# I2CRJ45X32.net
KiCad netlist of a schematic drawn in EAGLE
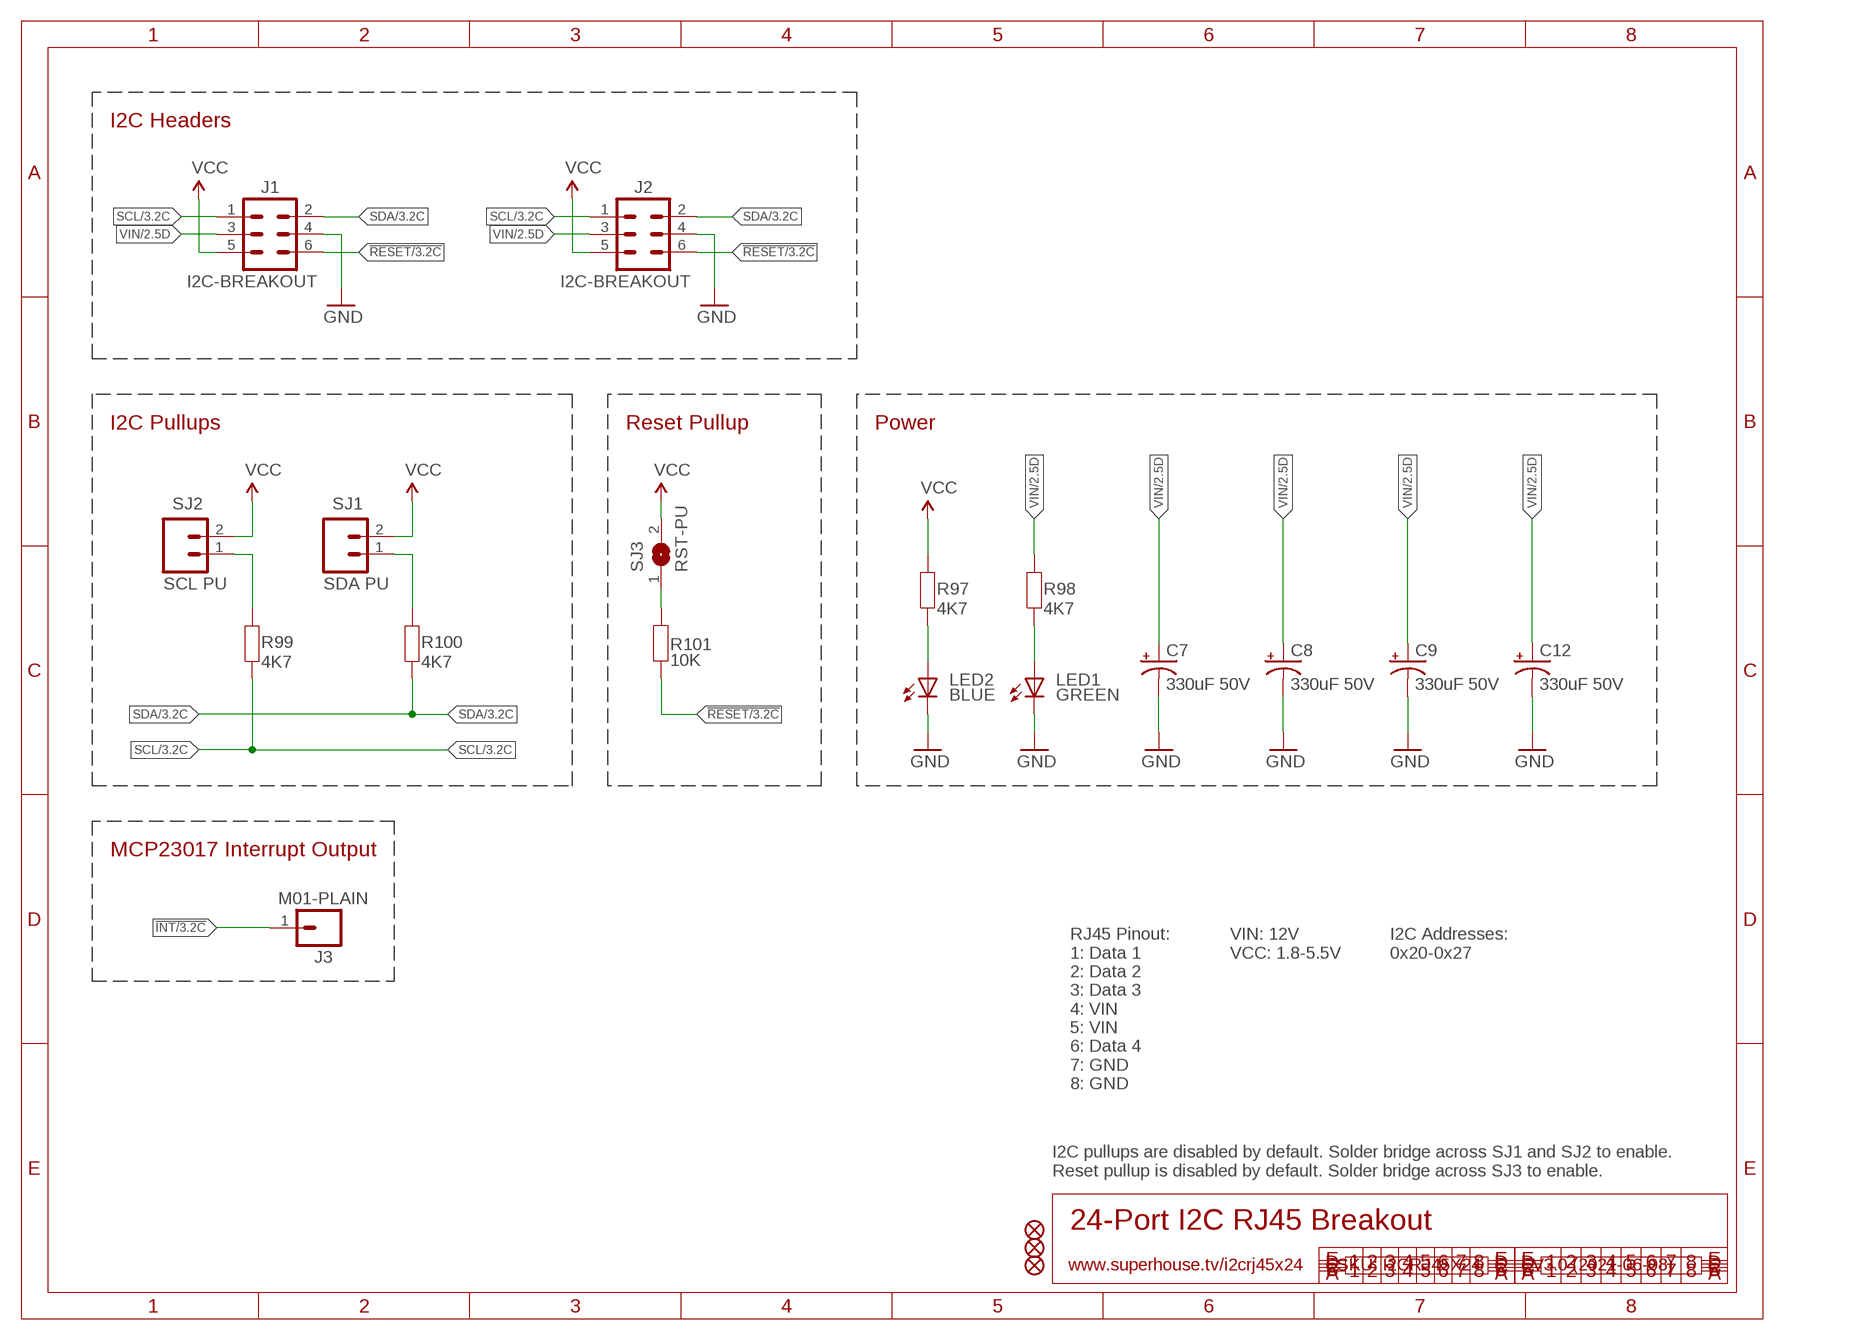
[diagram p0: schematic, sheet 1]
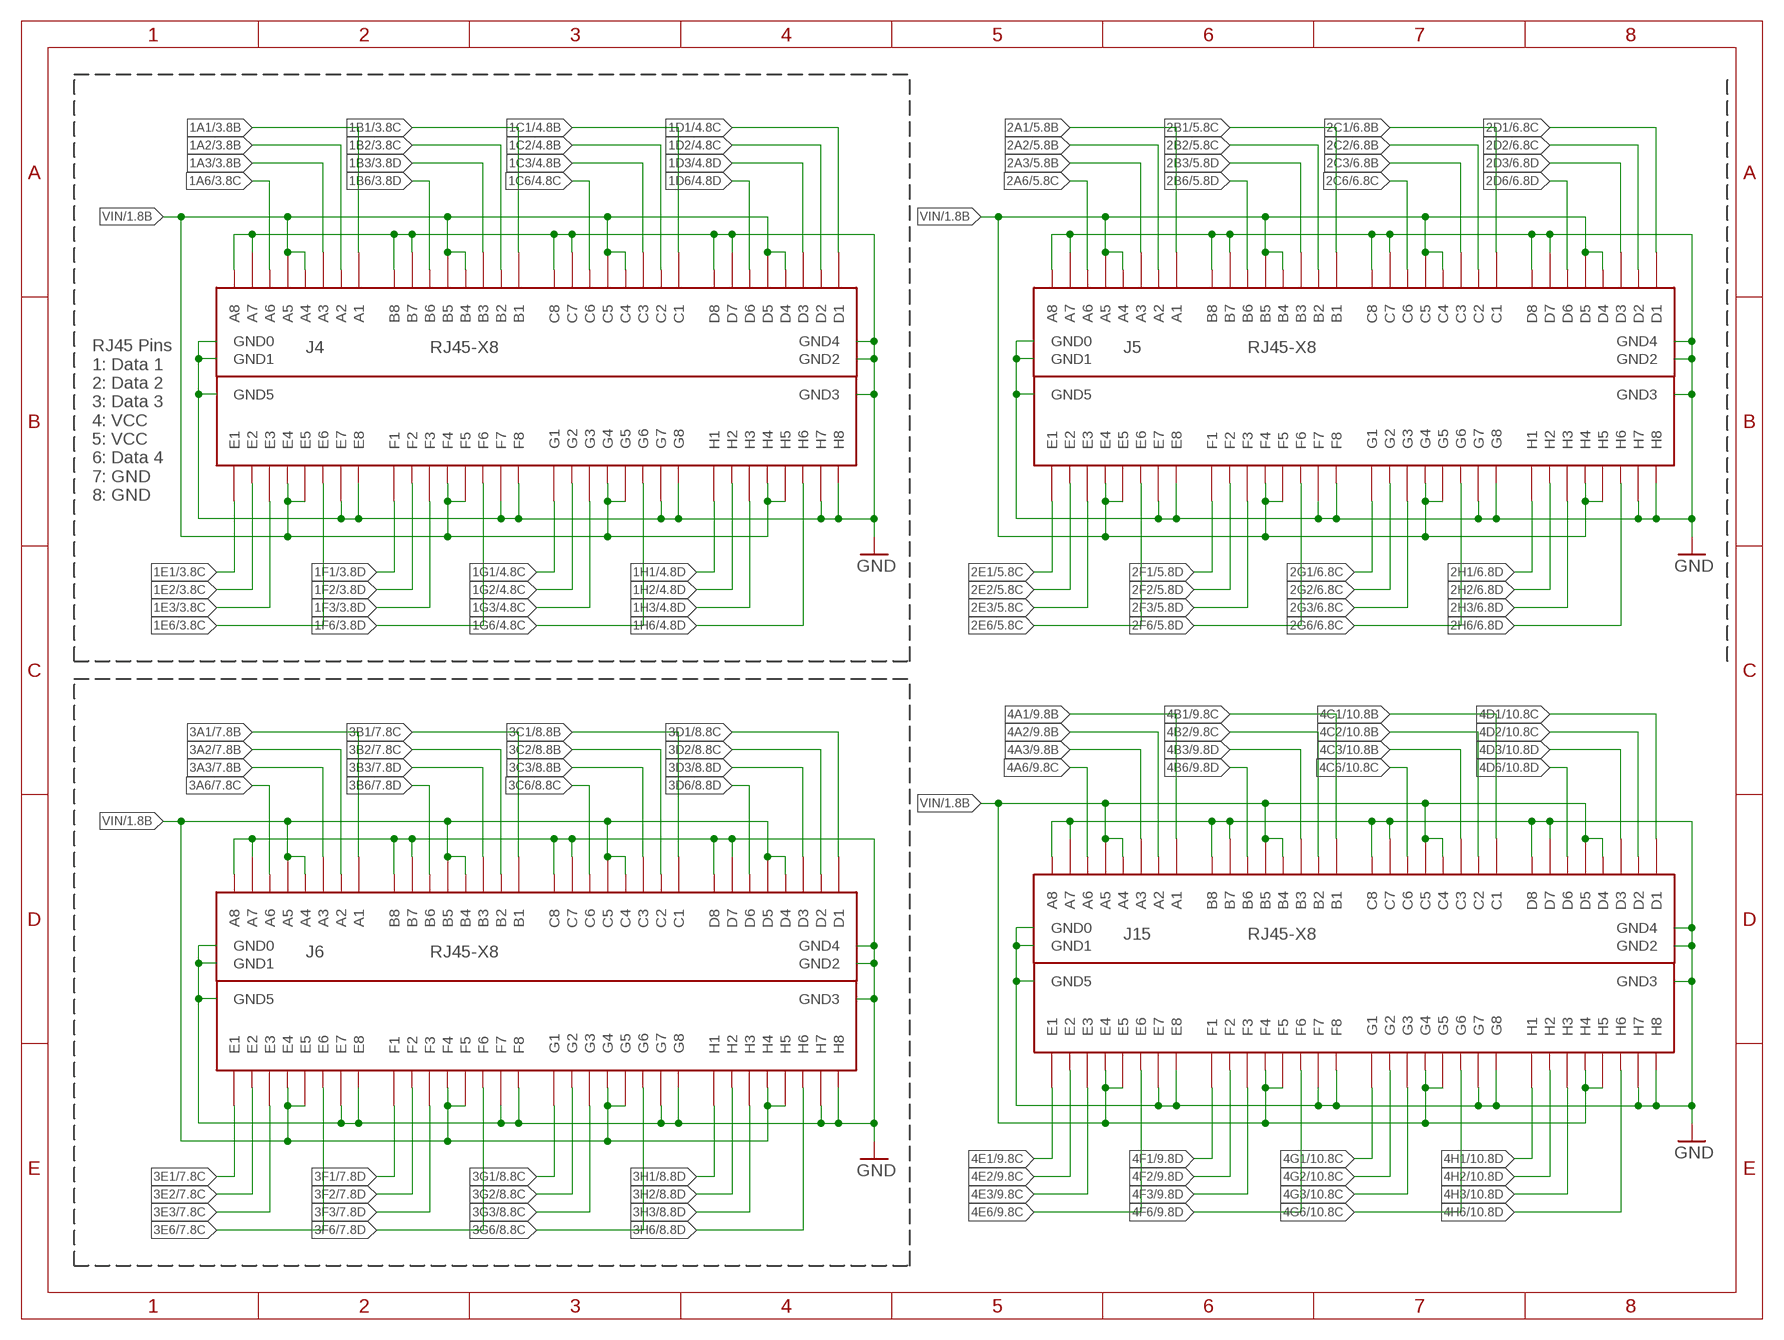
[diagram p1: schematic, sheet 2]
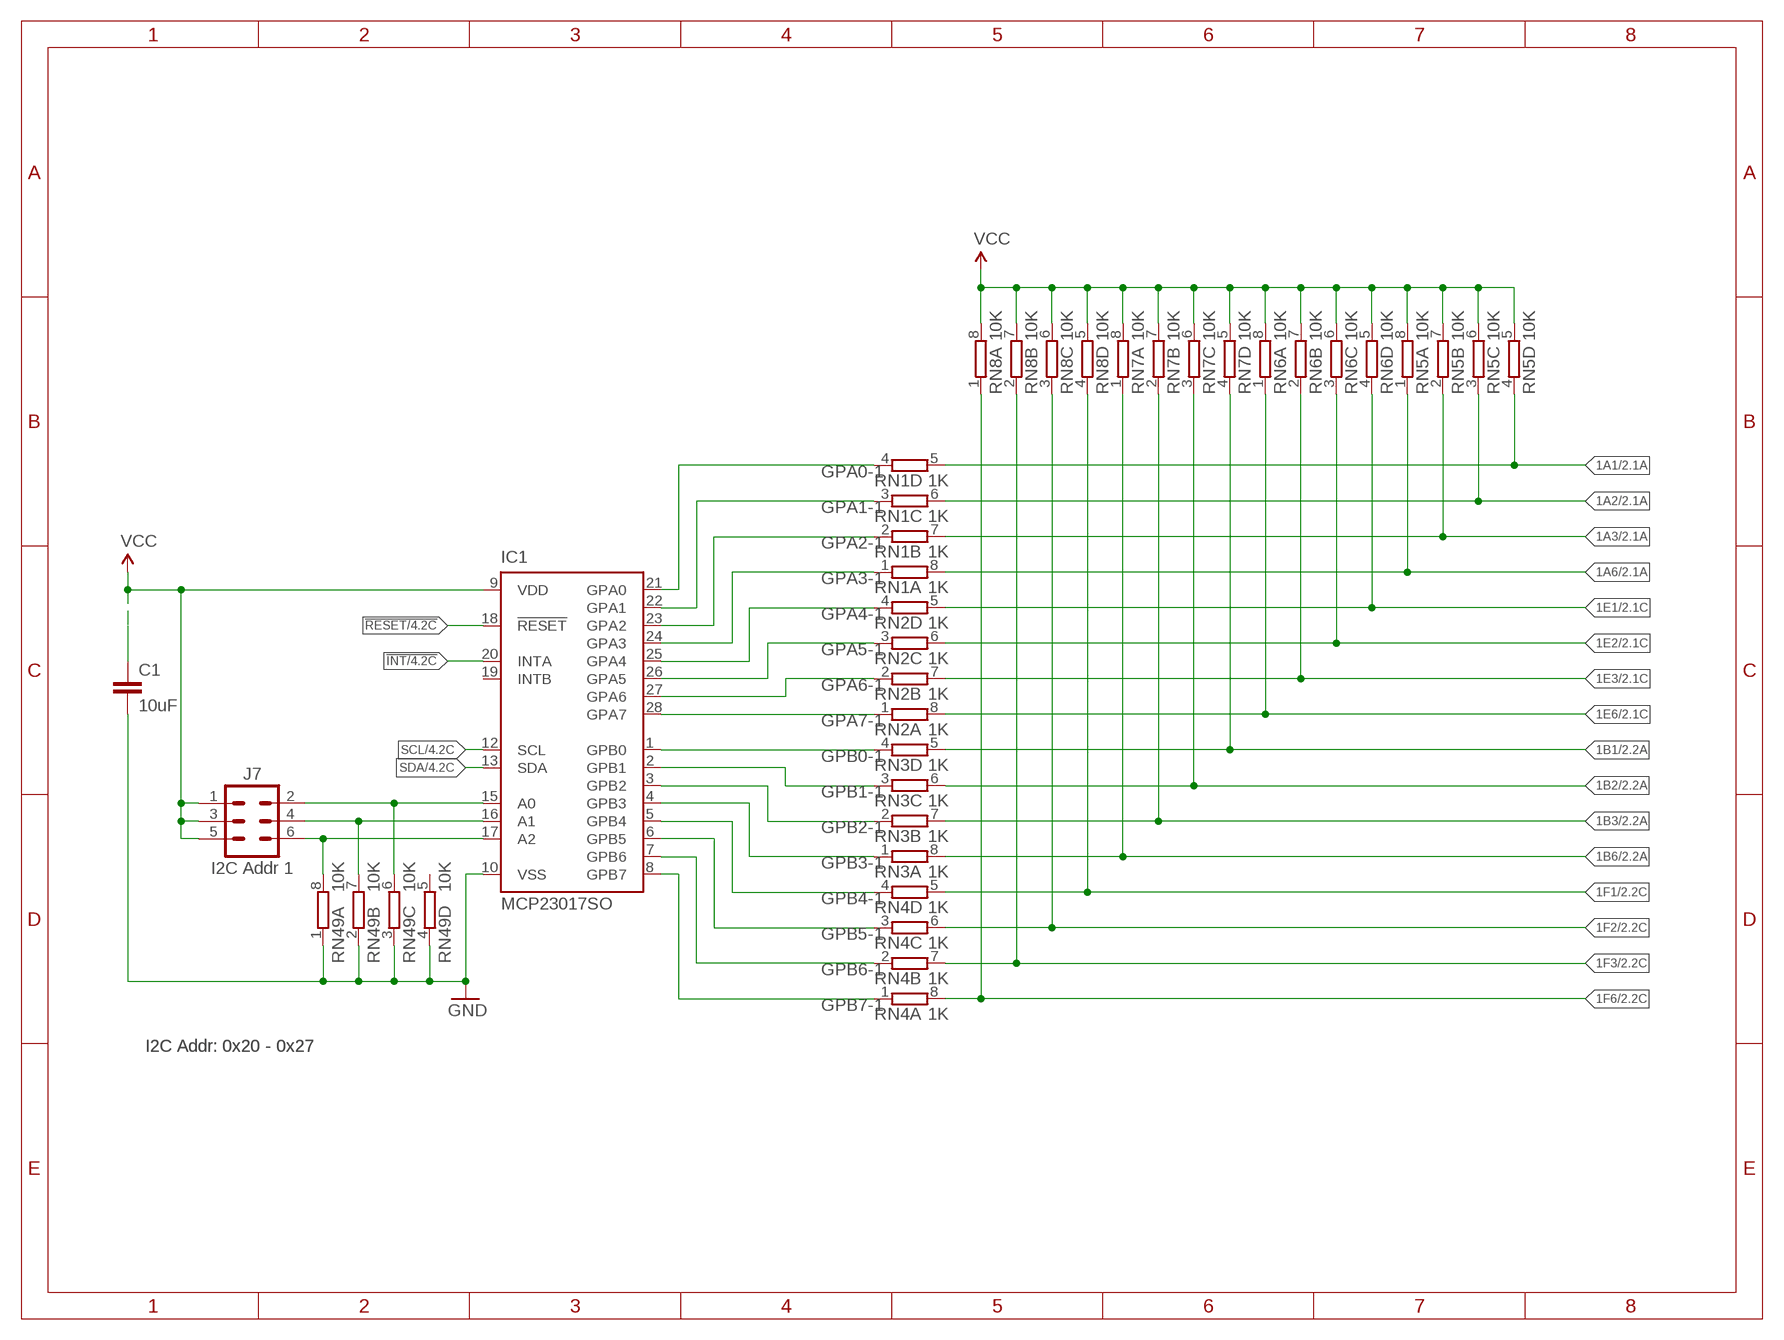
[diagram p2: schematic, sheet 3]
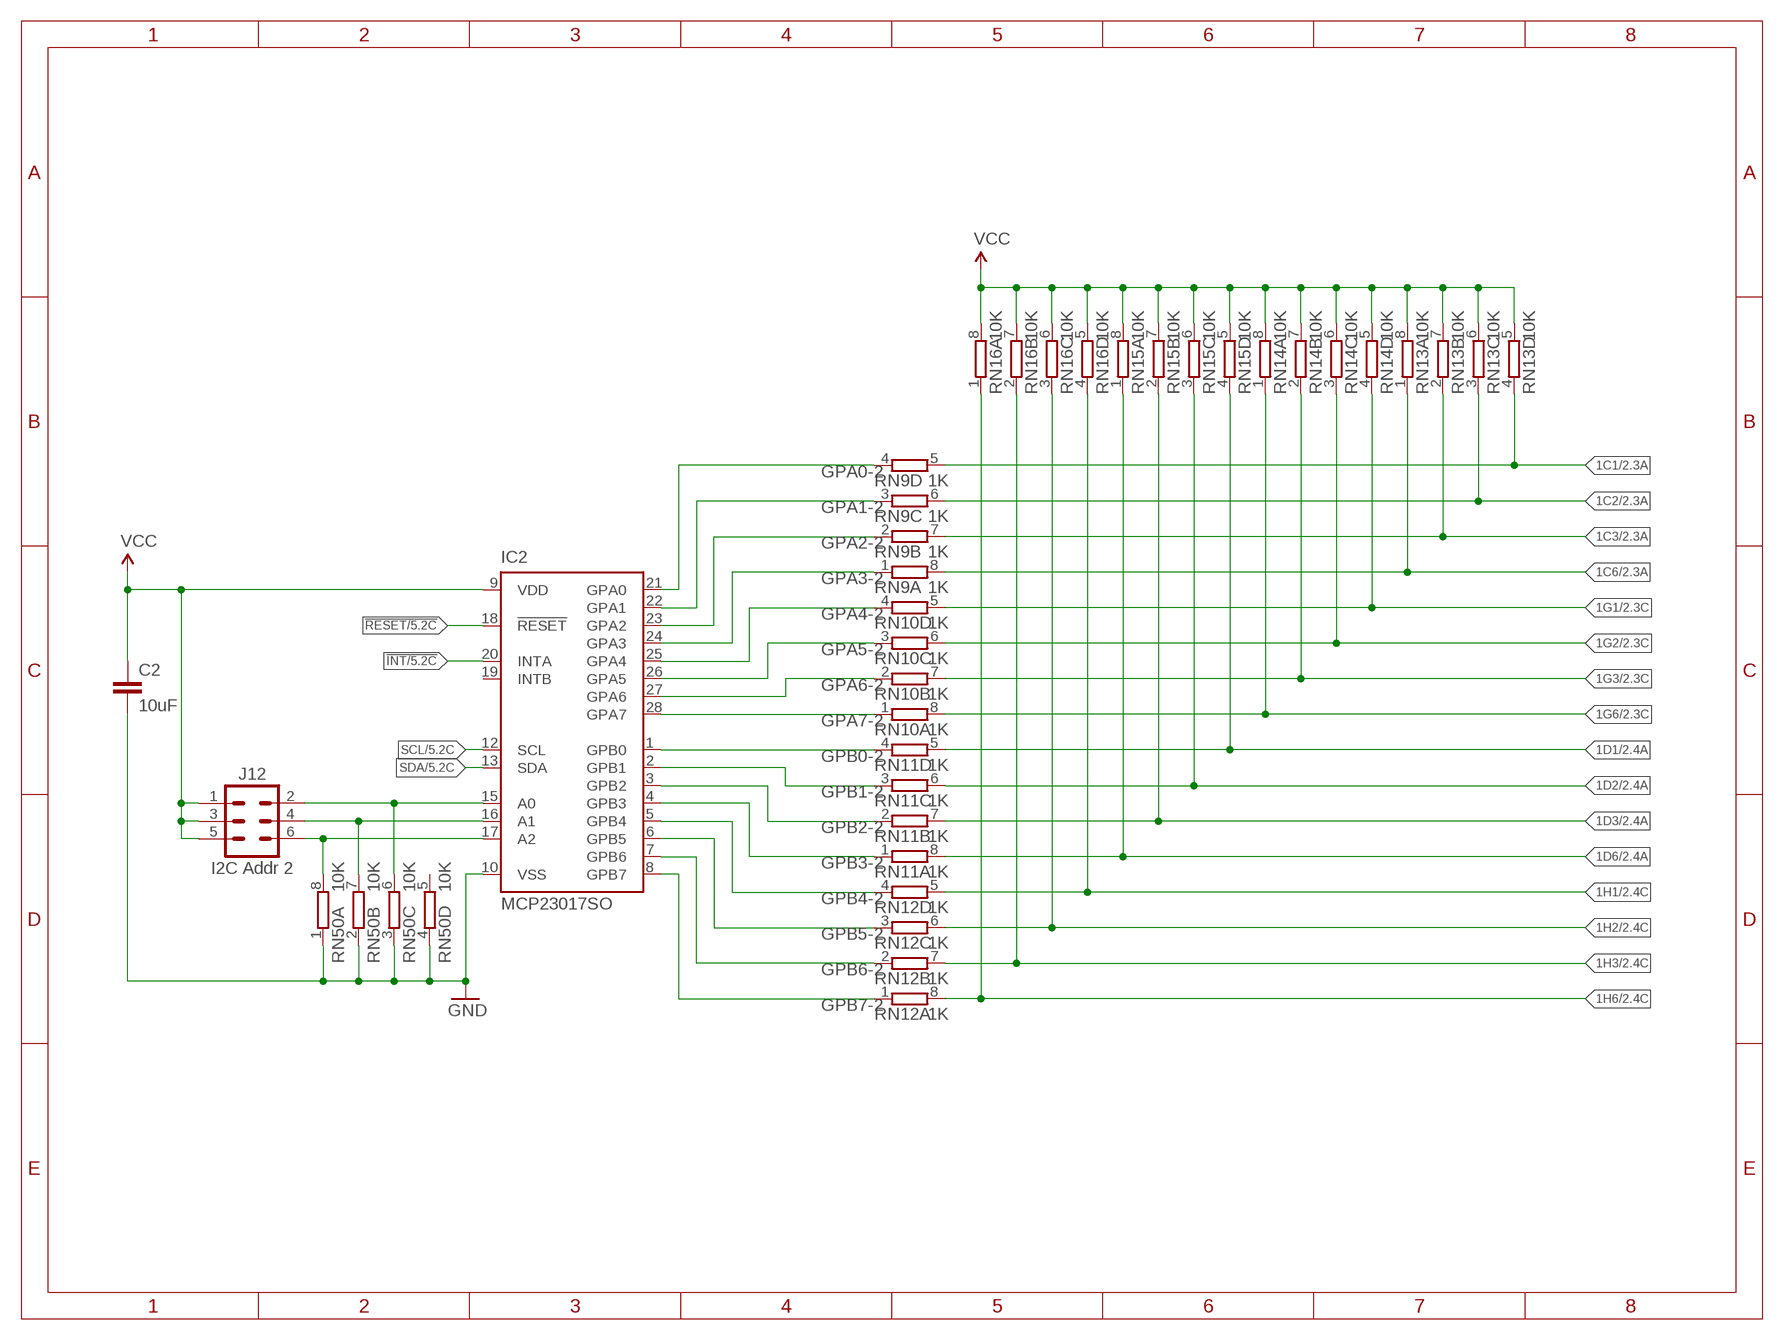
[diagram p3: schematic, sheet 4]
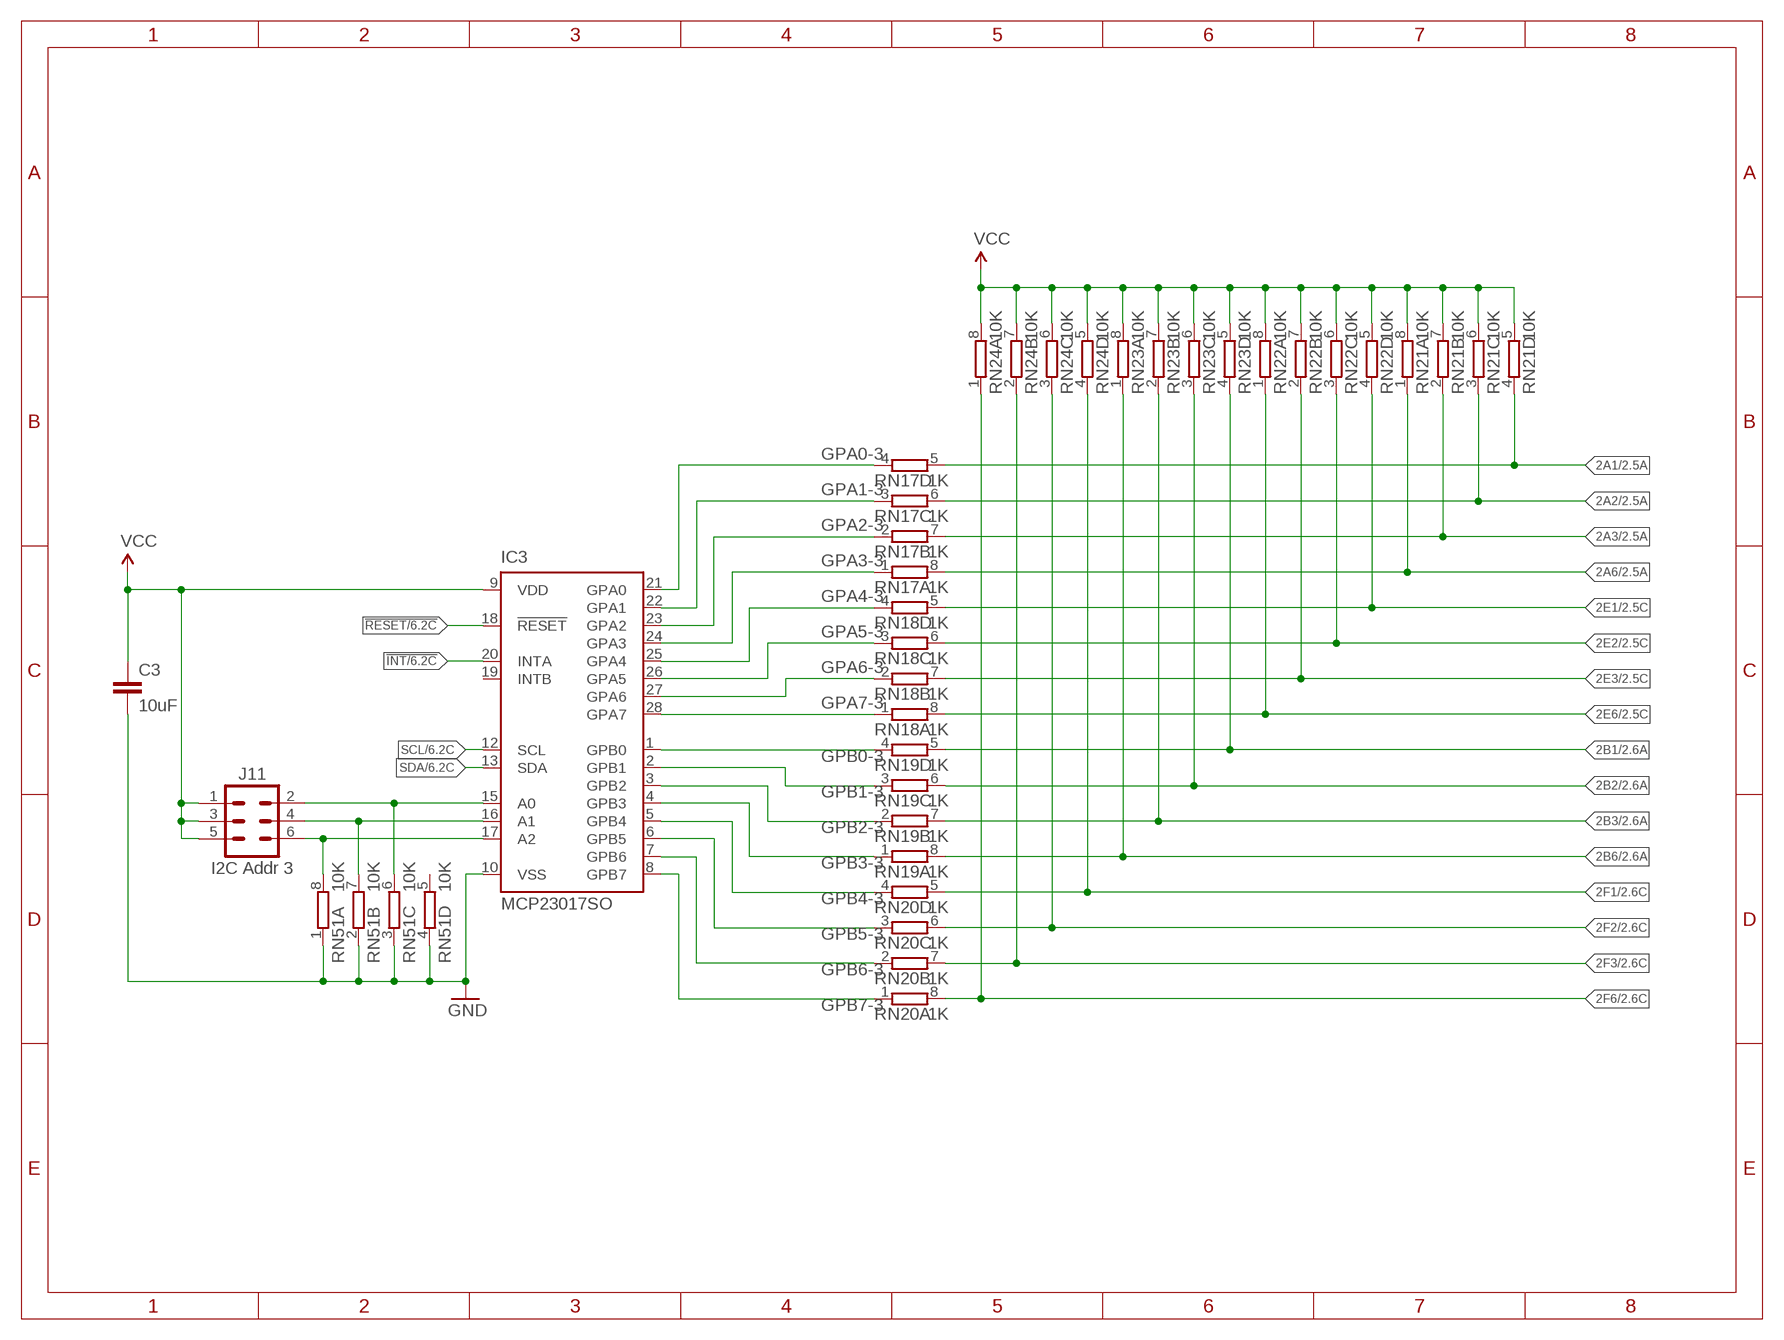
[diagram p4: schematic, sheet 5]
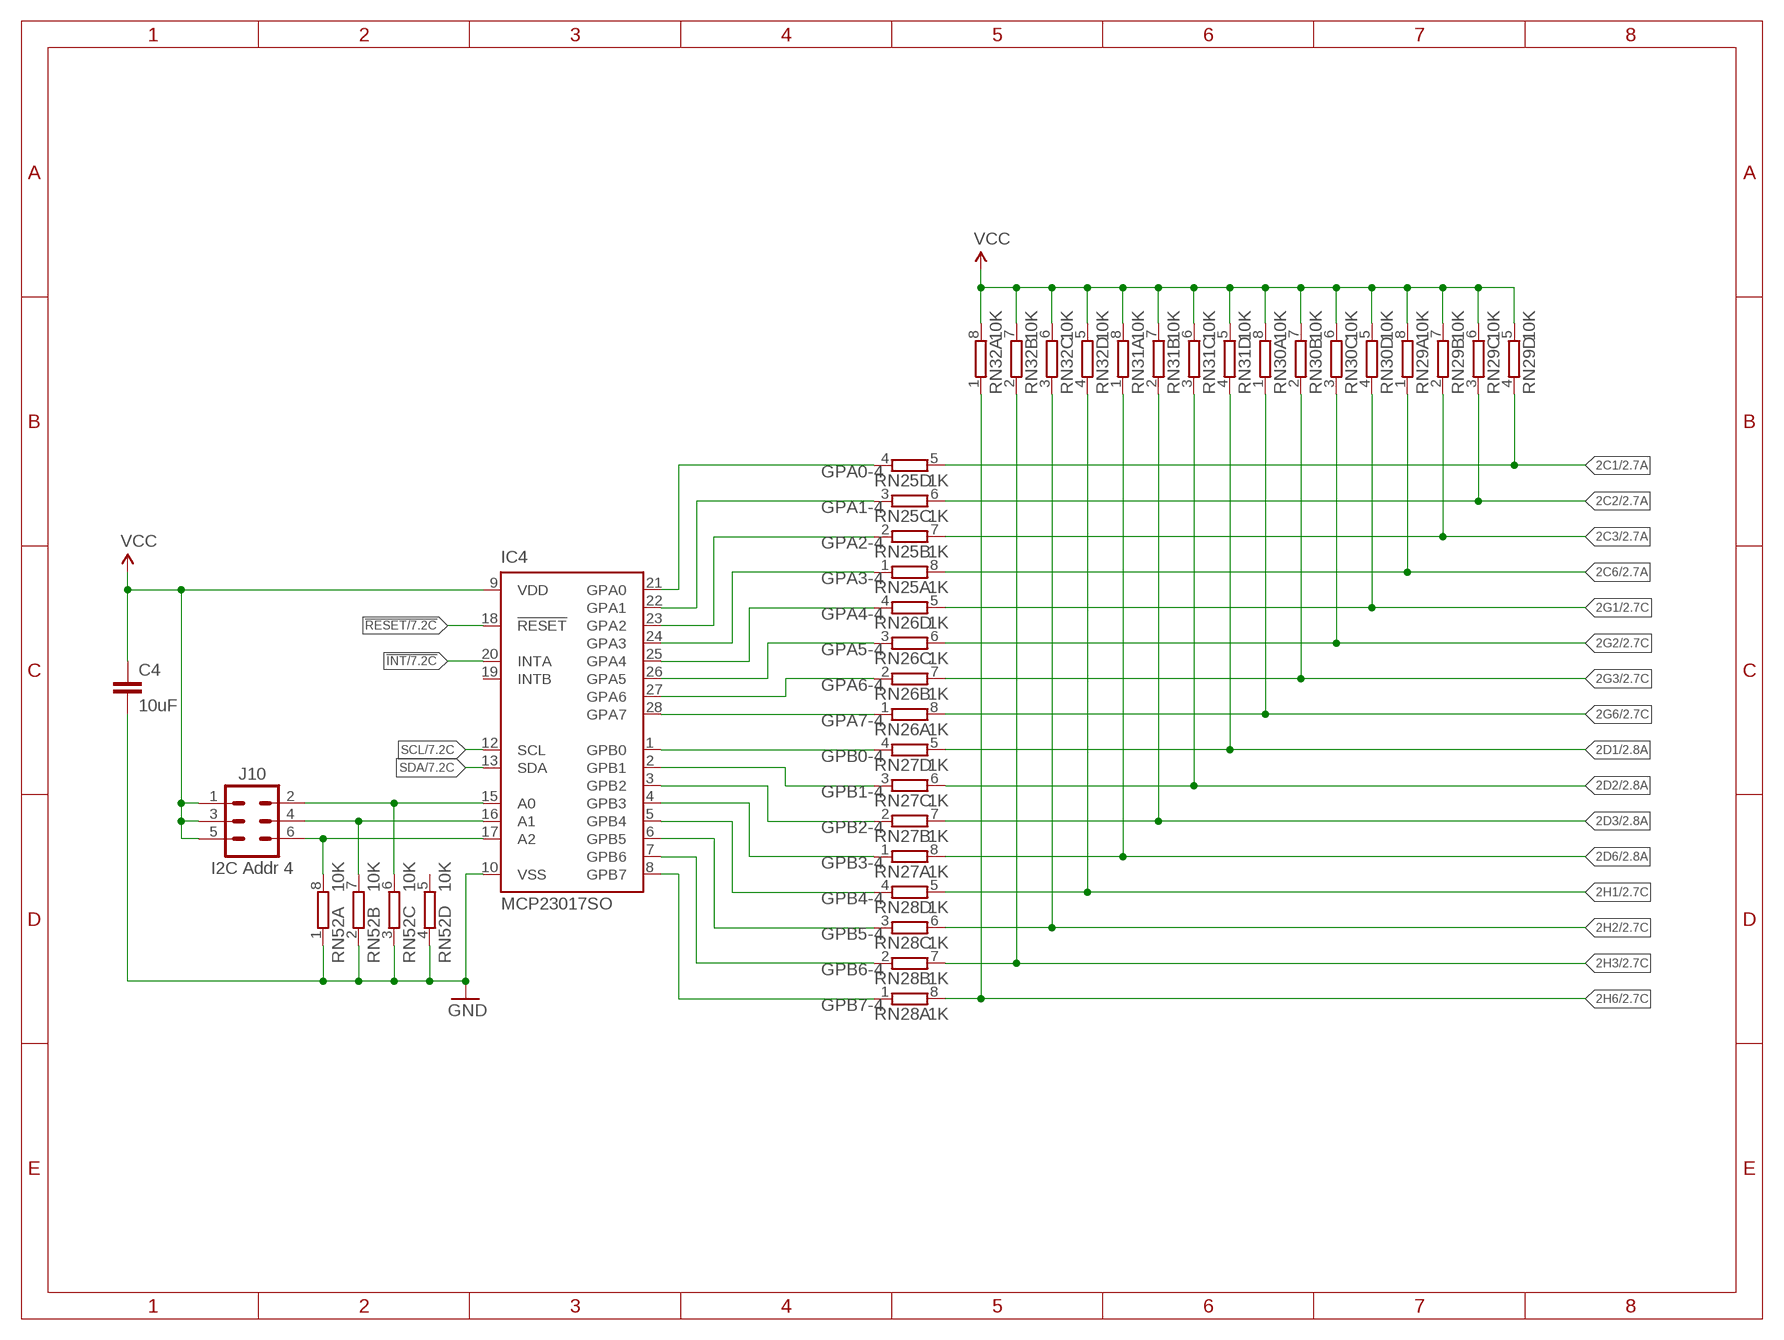
[diagram p5: schematic, sheet 6]
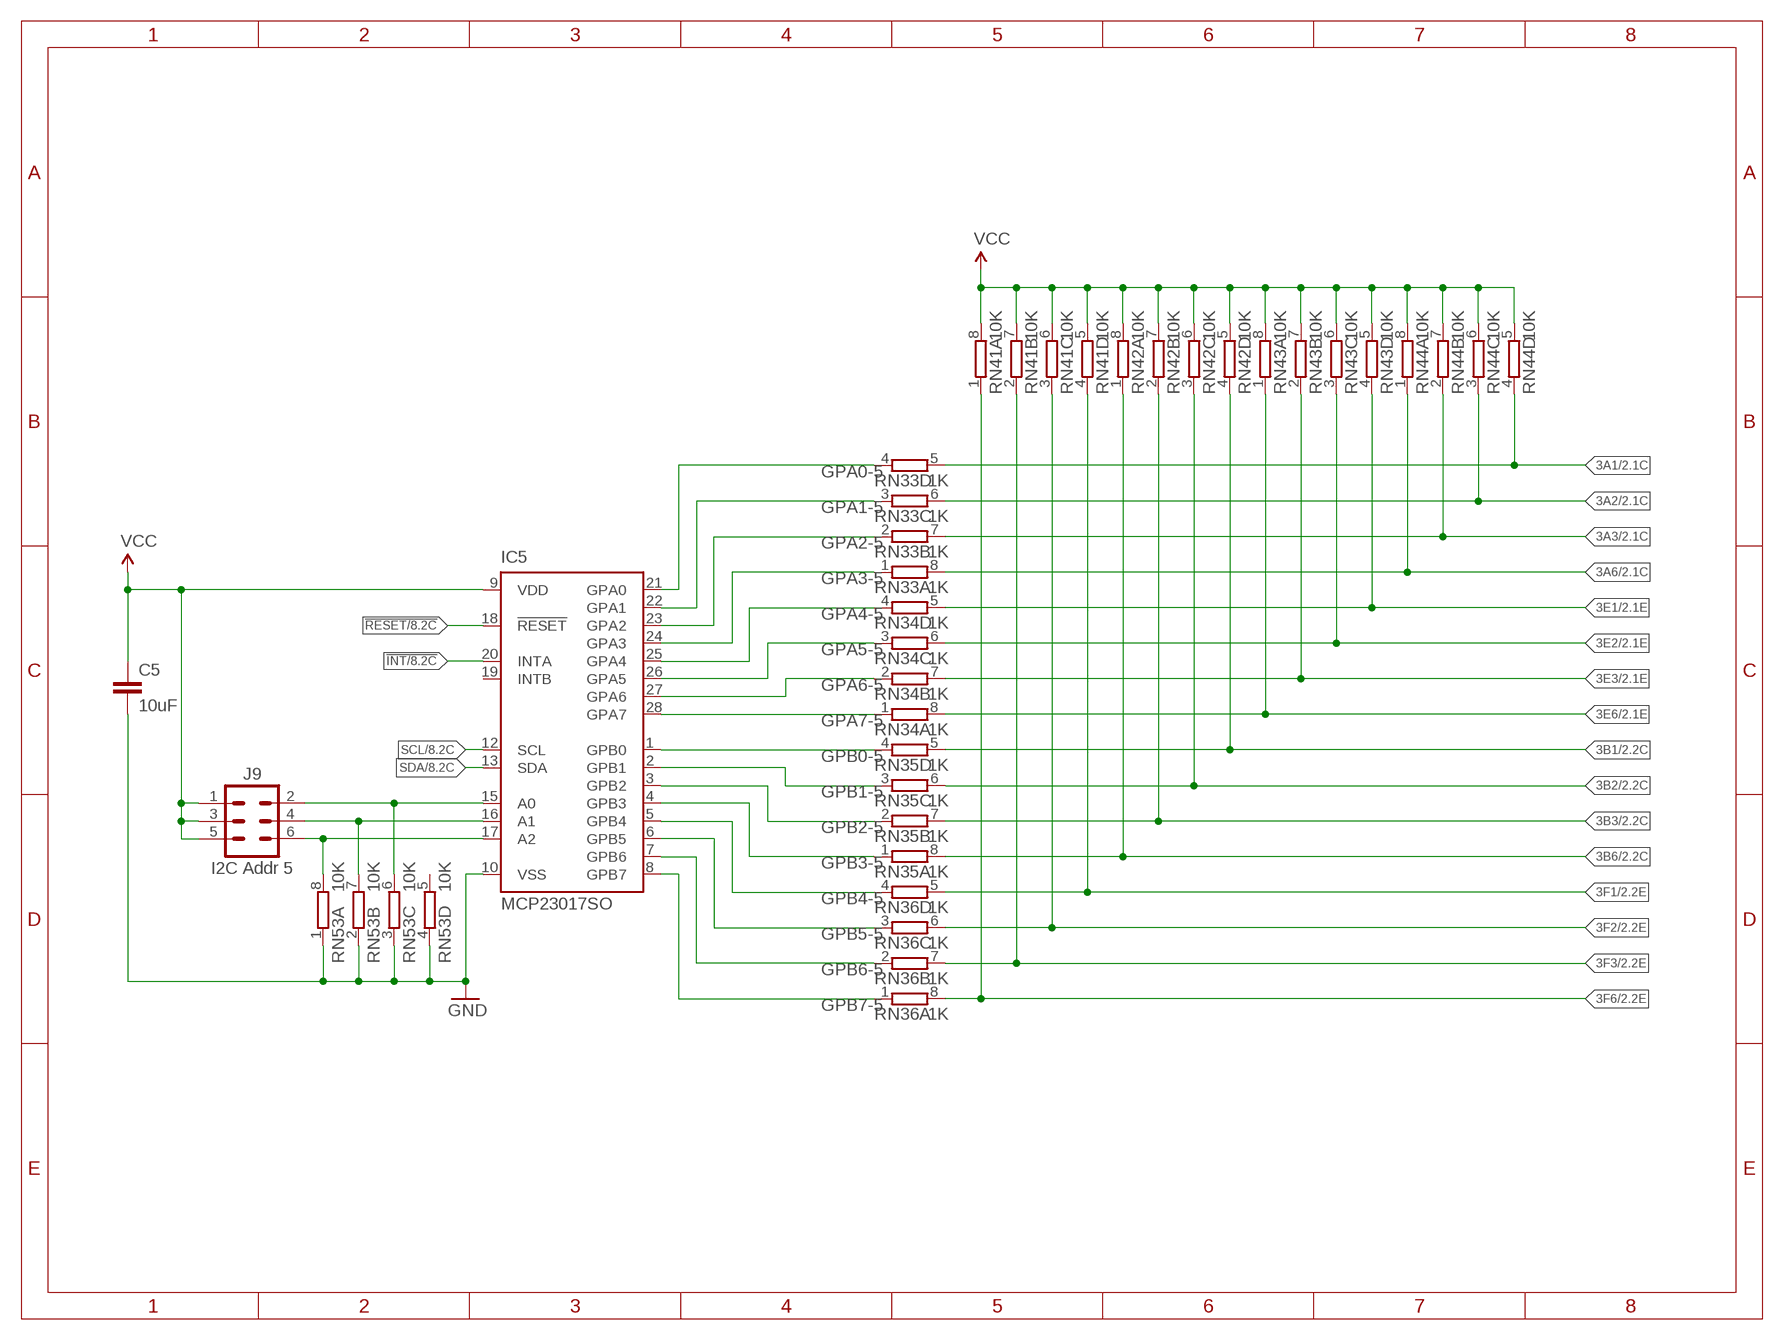
[diagram p6: schematic, sheet 7]
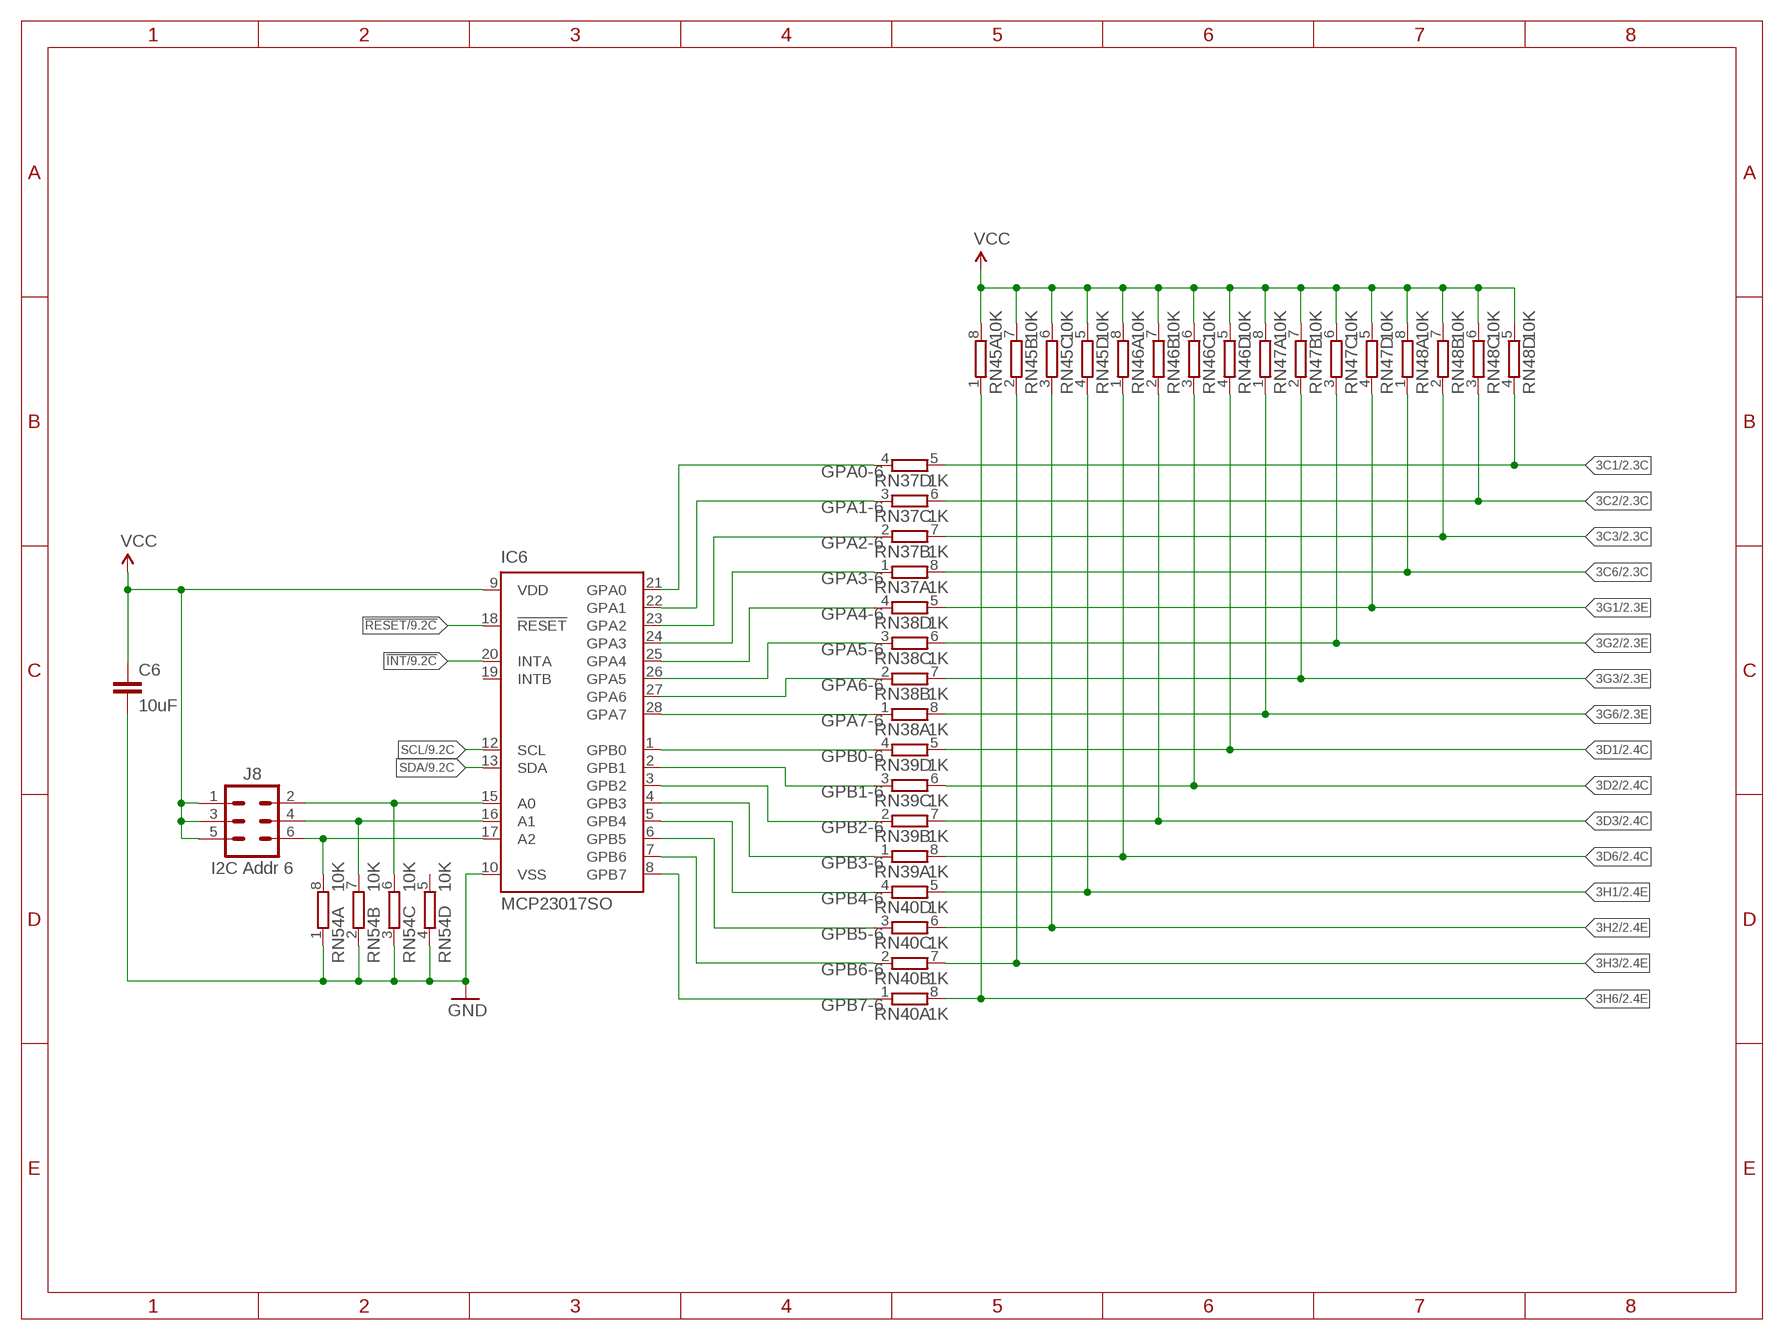
[diagram p7: schematic, sheet 8]
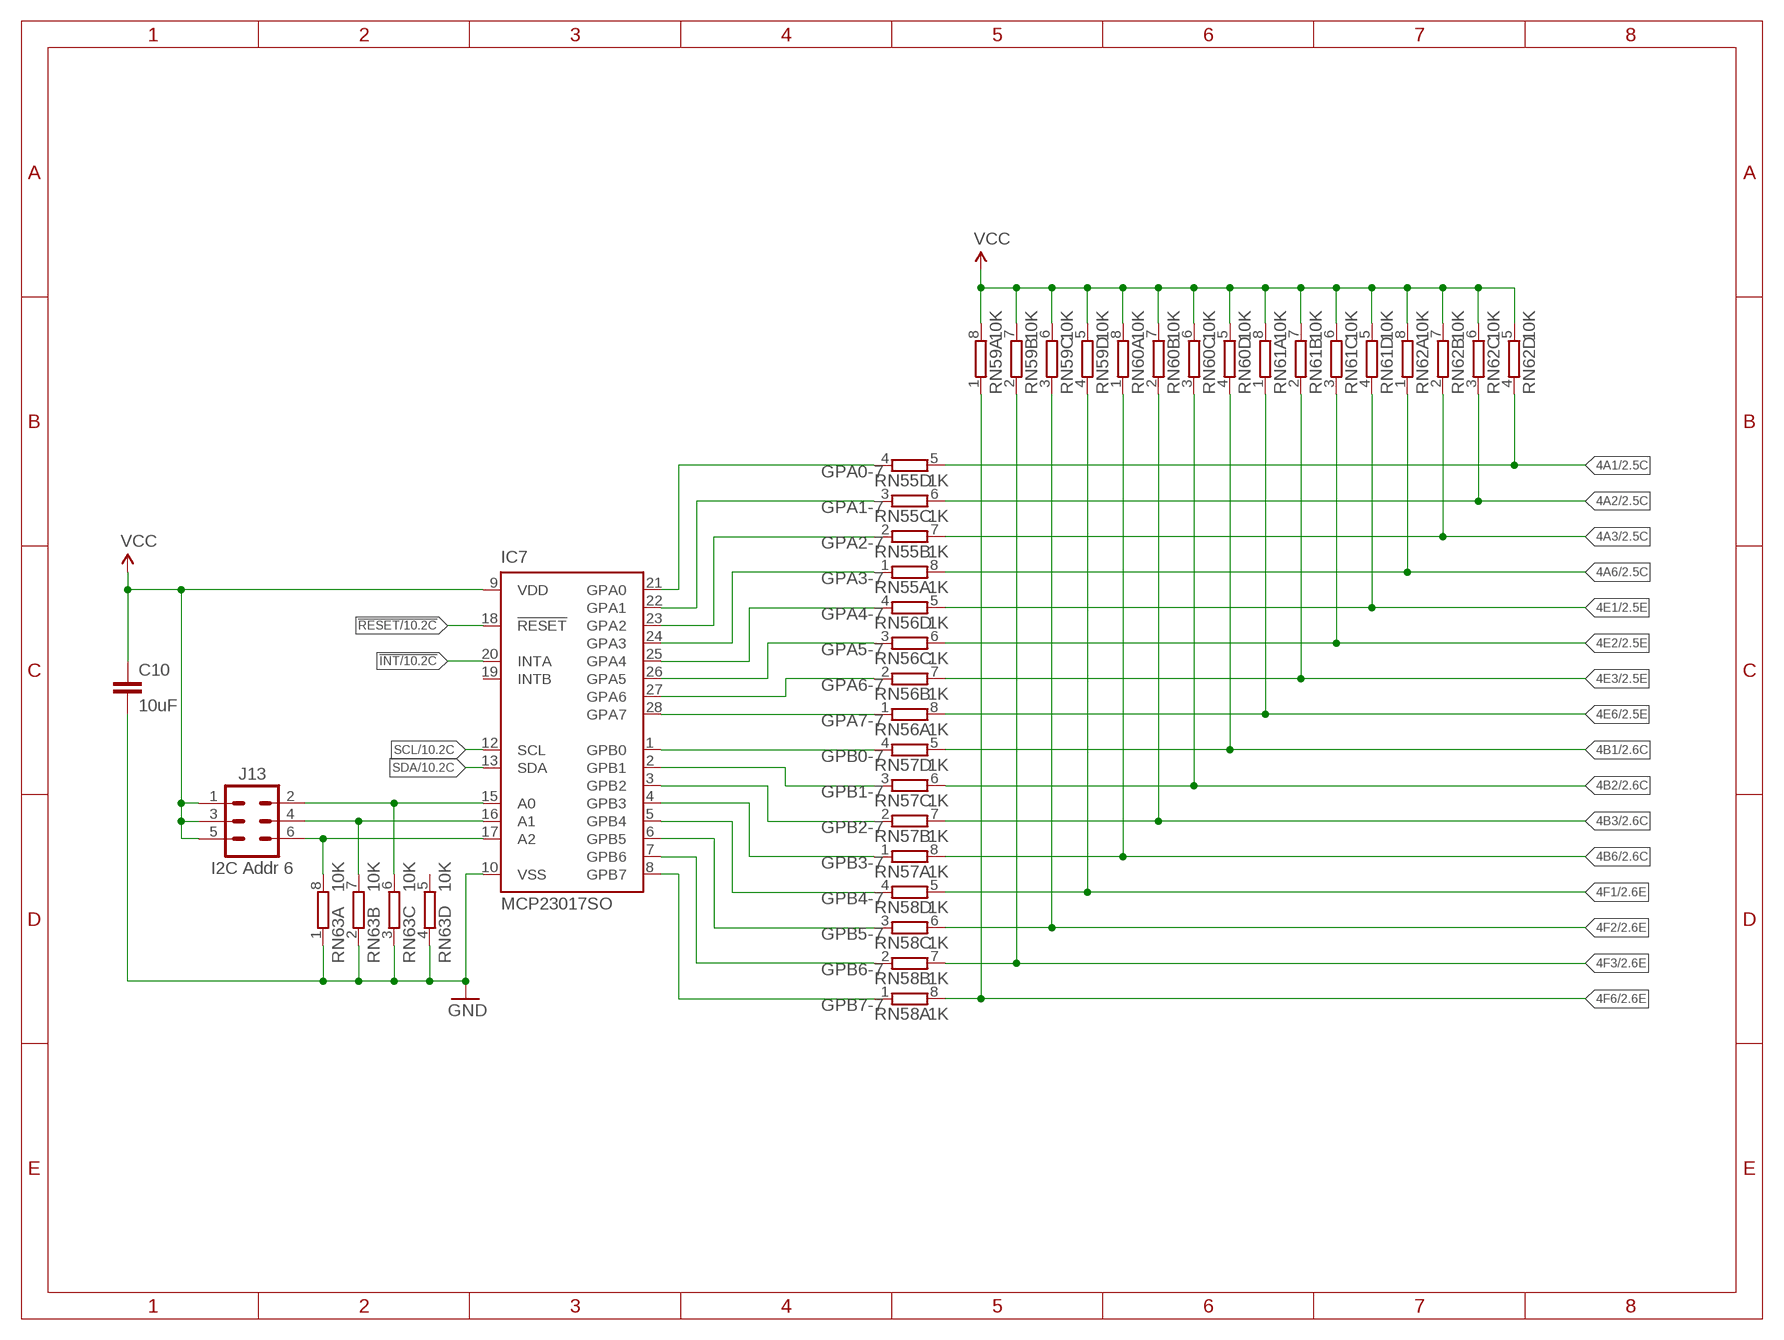
[diagram p8: schematic, sheet 9]
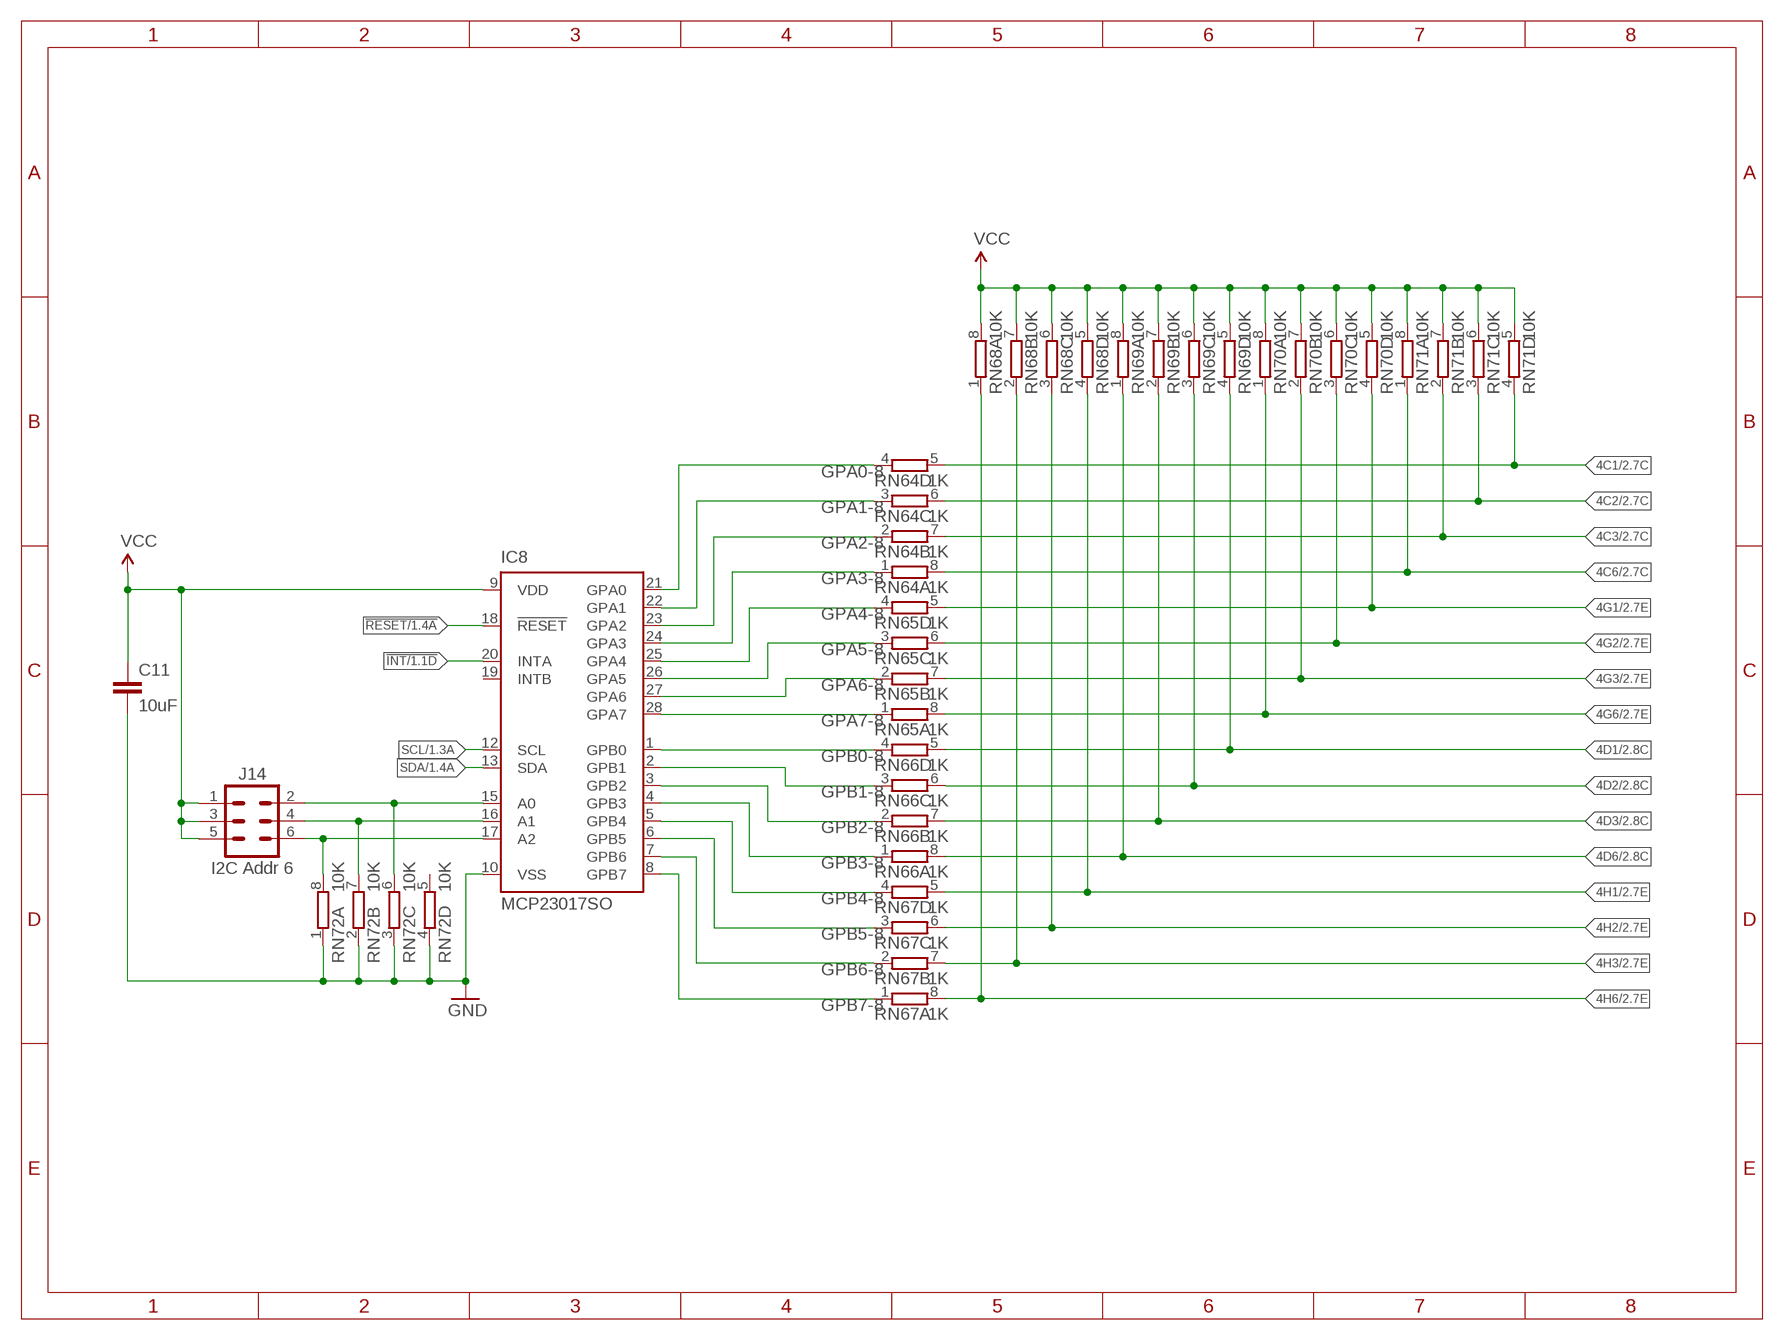
[diagram p9: schematic, sheet 10]

(export (version "E")
  (design (tool "Eeschema 10.0.6"))
  (components
    (comp (ref "J4")
      (value "RJ45-X8")
      (footprint "eagle-import:RJ45-2X4")
      (libsource (lib "eagle-import") (part "RJ45-X8"))
    )
    (comp (ref "J5")
      (value "RJ45-X8")
      (footprint "eagle-import:RJ45-2X4")
      (libsource (lib "eagle-import") (part "RJ45-X8"))
    )
    (comp (ref "J6")
      (value "RJ45-X8")
      (footprint "eagle-import:RJ45-2X4")
      (libsource (lib "eagle-import") (part "RJ45-X8"))
    )
    (comp (ref "J15")
      (value "RJ45-X8")
      (footprint "eagle-import:RJ45-2X4")
      (libsource (lib "eagle-import") (part "RJ45-X8"))
    )
    (comp (ref "C7")
      (value "330uF 50V")
      (footprint "eagle-import:PANASONIC_G")
      (libsource (lib "eagle-import") (part "CAP_POLG"))
    )
    (comp (ref "C8")
      (value "330uF 50V")
      (footprint "eagle-import:PANASONIC_G")
      (libsource (lib "eagle-import") (part "CAP_POLG"))
    )
    (comp (ref "C9")
      (value "330uF 50V")
      (footprint "eagle-import:PANASONIC_G")
      (libsource (lib "eagle-import") (part "CAP_POLG"))
    )
    (comp (ref "C12")
      (value "330uF 50V")
      (footprint "eagle-import:PANASONIC_G")
      (libsource (lib "eagle-import") (part "CAP_POLG"))
    )
    (comp (ref "FID1")
      (value "FIDUCIAL1X2.5")
      (footprint "eagle-import:FIDUCIAL-1X2.5")
      (libsource (lib "eagle-import") (part "FIDUCIAL1X2.5"))
    )
    (comp (ref "FID2")
      (value "FIDUCIAL1X2.5")
      (footprint "eagle-import:FIDUCIAL-1X2.5")
      (libsource (lib "eagle-import") (part "FIDUCIAL1X2.5"))
    )
    (comp (ref "FID3")
      (value "FIDUCIAL1X2.5")
      (footprint "eagle-import:FIDUCIAL-1X2.5")
      (libsource (lib "eagle-import") (part "FIDUCIAL1X2.5"))
    )
    (comp (ref "J1")
      (value "I2C-BREAKOUT")
      (footprint "eagle-import:2X3-2.54-SHROUDED")
      (libsource (lib "eagle-import") (part "M02X3-SHROUDED"))
    )
    (comp (ref "J2")
      (value "I2C-BREAKOUT")
      (footprint "eagle-import:2X3-2.54-SHROUDED")
      (libsource (lib "eagle-import") (part "M02X3-SHROUDED"))
    )
    (comp (ref "J3")
      (value "M01-PLAIN")
      (footprint "eagle-import:1X01")
      (libsource (lib "eagle-import") (part "M01-PLAIN"))
    )
    (comp (ref "LED1")
      (value "GREEN")
      (footprint "eagle-import:LED-0603")
      (libsource (lib "eagle-import") (part "LED0603"))
    )
    (comp (ref "LED2")
      (value "BLUE")
      (footprint "eagle-import:LED-0603")
      (libsource (lib "eagle-import") (part "LED0603"))
    )
    (comp (ref "R97")
      (value "4K7")
      (footprint "eagle-import:R0603")
      (libsource (lib "eagle-import") (part "RESISTOR0603"))
    )
    (comp (ref "R98")
      (value "4K7")
      (footprint "eagle-import:R0603")
      (libsource (lib "eagle-import") (part "RESISTOR0603"))
    )
    (comp (ref "R99")
      (value "4K7")
      (footprint "eagle-import:R0603")
      (libsource (lib "eagle-import") (part "RESISTOR0603"))
    )
    (comp (ref "R100")
      (value "4K7")
      (footprint "eagle-import:R0603")
      (libsource (lib "eagle-import") (part "RESISTOR0603"))
    )
    (comp (ref "R101")
      (value "10K")
      (footprint "eagle-import:R0603")
      (libsource (lib "eagle-import") (part "RESISTOR0603"))
    )
    (comp (ref "SJ1")
      (value "SDA PU")
      (footprint "eagle-import:1X02-P")
      (libsource (lib "eagle-import") (part "M02-PIN"))
    )
    (comp (ref "SJ2")
      (value "SCL PU")
      (footprint "eagle-import:1X02-P")
      (libsource (lib "eagle-import") (part "M02-PIN"))
    )
    (comp (ref "SJ3")
      (value "RST-PU")
      (footprint "eagle-import:SJ")
      (libsource (lib "eagle-import") (part "SJ-NORMAL"))
    )
    (comp (ref "C4")
      (value "10uF")
      (footprint "eagle-import:C0805")
      (libsource (lib "eagle-import") (part "CAP0805"))
    )
    (comp (ref "IC4")
      (value "MCP23017SO")
      (footprint "eagle-import:SO28W")
      (libsource (lib "eagle-import") (part "MCP23017SO"))
    )
    (comp (ref "J10")
      (value "I2C Addr 4")
      (footprint "eagle-import:2X03-P")
      (libsource (lib "eagle-import") (part "M02X3-PIN"))
    )
    (comp (ref "RN25")
      (value "1K")
      (footprint "eagle-import:CAY16")
      (libsource (lib "eagle-import") (part "4R-NCAY16"))
    )
    (comp (ref "RN26")
      (value "1K")
      (footprint "eagle-import:CAY16")
      (libsource (lib "eagle-import") (part "4R-NCAY16"))
    )
    (comp (ref "RN27")
      (value "1K")
      (footprint "eagle-import:CAY16")
      (libsource (lib "eagle-import") (part "4R-NCAY16"))
    )
    (comp (ref "RN28")
      (value "1K")
      (footprint "eagle-import:CAY16")
      (libsource (lib "eagle-import") (part "4R-NCAY16"))
    )
    (comp (ref "RN29")
      (value "10K")
      (footprint "eagle-import:CAY16")
      (libsource (lib "eagle-import") (part "4R-NCAY16"))
    )
    (comp (ref "RN30")
      (value "10K")
      (footprint "eagle-import:CAY16")
      (libsource (lib "eagle-import") (part "4R-NCAY16"))
    )
    (comp (ref "RN31")
      (value "10K")
      (footprint "eagle-import:CAY16")
      (libsource (lib "eagle-import") (part "4R-NCAY16"))
    )
    (comp (ref "RN32")
      (value "10K")
      (footprint "eagle-import:CAY16")
      (libsource (lib "eagle-import") (part "4R-NCAY16"))
    )
    (comp (ref "RN52")
      (value "10K")
      (footprint "eagle-import:CAY16")
      (libsource (lib "eagle-import") (part "4R-NCAY16"))
    )
    (comp (ref "C5")
      (value "10uF")
      (footprint "eagle-import:C0805")
      (libsource (lib "eagle-import") (part "CAP0805"))
    )
    (comp (ref "IC5")
      (value "MCP23017SO")
      (footprint "eagle-import:SO28W")
      (libsource (lib "eagle-import") (part "MCP23017SO"))
    )
    (comp (ref "J9")
      (value "I2C Addr 5")
      (footprint "eagle-import:2X03-P")
      (libsource (lib "eagle-import") (part "M02X3-PIN"))
    )
    (comp (ref "RN33")
      (value "1K")
      (footprint "eagle-import:CAY16")
      (libsource (lib "eagle-import") (part "4R-NCAY16"))
    )
    (comp (ref "RN34")
      (value "1K")
      (footprint "eagle-import:CAY16")
      (libsource (lib "eagle-import") (part "4R-NCAY16"))
    )
    (comp (ref "RN35")
      (value "1K")
      (footprint "eagle-import:CAY16")
      (libsource (lib "eagle-import") (part "4R-NCAY16"))
    )
    (comp (ref "RN36")
      (value "1K")
      (footprint "eagle-import:CAY16")
      (libsource (lib "eagle-import") (part "4R-NCAY16"))
    )
    (comp (ref "RN41")
      (value "10K")
      (footprint "eagle-import:CAY16")
      (libsource (lib "eagle-import") (part "4R-NCAY16"))
    )
    (comp (ref "RN42")
      (value "10K")
      (footprint "eagle-import:CAY16")
      (libsource (lib "eagle-import") (part "4R-NCAY16"))
    )
    (comp (ref "RN43")
      (value "10K")
      (footprint "eagle-import:CAY16")
      (libsource (lib "eagle-import") (part "4R-NCAY16"))
    )
    (comp (ref "RN44")
      (value "10K")
      (footprint "eagle-import:CAY16")
      (libsource (lib "eagle-import") (part "4R-NCAY16"))
    )
    (comp (ref "RN53")
      (value "10K")
      (footprint "eagle-import:CAY16")
      (libsource (lib "eagle-import") (part "4R-NCAY16"))
    )
    (comp (ref "C2")
      (value "10uF")
      (footprint "eagle-import:C0805")
      (libsource (lib "eagle-import") (part "CAP0805"))
    )
    (comp (ref "IC2")
      (value "MCP23017SO")
      (footprint "eagle-import:SO28W")
      (libsource (lib "eagle-import") (part "MCP23017SO"))
    )
    (comp (ref "J12")
      (value "I2C Addr 2")
      (footprint "eagle-import:2X03-P")
      (libsource (lib "eagle-import") (part "M02X3-PIN"))
    )
    (comp (ref "RN9")
      (value "1K")
      (footprint "eagle-import:CAY16")
      (libsource (lib "eagle-import") (part "4R-NCAY16"))
    )
    (comp (ref "RN10")
      (value "1K")
      (footprint "eagle-import:CAY16")
      (libsource (lib "eagle-import") (part "4R-NCAY16"))
    )
    (comp (ref "RN11")
      (value "1K")
      (footprint "eagle-import:CAY16")
      (libsource (lib "eagle-import") (part "4R-NCAY16"))
    )
    (comp (ref "RN12")
      (value "1K")
      (footprint "eagle-import:CAY16")
      (libsource (lib "eagle-import") (part "4R-NCAY16"))
    )
    (comp (ref "RN13")
      (value "10K")
      (footprint "eagle-import:CAY16")
      (libsource (lib "eagle-import") (part "4R-NCAY16"))
    )
    (comp (ref "RN14")
      (value "10K")
      (footprint "eagle-import:CAY16")
      (libsource (lib "eagle-import") (part "4R-NCAY16"))
    )
    (comp (ref "RN15")
      (value "10K")
      (footprint "eagle-import:CAY16")
      (libsource (lib "eagle-import") (part "4R-NCAY16"))
    )
    (comp (ref "RN16")
      (value "10K")
      (footprint "eagle-import:CAY16")
      (libsource (lib "eagle-import") (part "4R-NCAY16"))
    )
    (comp (ref "RN50")
      (value "10K")
      (footprint "eagle-import:CAY16")
      (libsource (lib "eagle-import") (part "4R-NCAY16"))
    )
    (comp (ref "C1")
      (value "10uF")
      (footprint "eagle-import:C0805")
      (libsource (lib "eagle-import") (part "CAP0805"))
    )
    (comp (ref "IC1")
      (value "MCP23017SO")
      (footprint "eagle-import:SO28W")
      (libsource (lib "eagle-import") (part "MCP23017SO"))
    )
    (comp (ref "J7")
      (value "I2C Addr 1")
      (footprint "eagle-import:2X03-P")
      (libsource (lib "eagle-import") (part "M02X3-PIN"))
    )
    (comp (ref "RN1")
      (value "1K")
      (footprint "eagle-import:CAY16")
      (libsource (lib "eagle-import") (part "4R-NCAY16"))
    )
    (comp (ref "RN2")
      (value "1K")
      (footprint "eagle-import:CAY16")
      (libsource (lib "eagle-import") (part "4R-NCAY16"))
    )
    (comp (ref "RN3")
      (value "1K")
      (footprint "eagle-import:CAY16")
      (libsource (lib "eagle-import") (part "4R-NCAY16"))
    )
    (comp (ref "RN4")
      (value "1K")
      (footprint "eagle-import:CAY16")
      (libsource (lib "eagle-import") (part "4R-NCAY16"))
    )
    (comp (ref "RN5")
      (value "10K")
      (footprint "eagle-import:CAY16")
      (libsource (lib "eagle-import") (part "4R-NCAY16"))
    )
    (comp (ref "RN6")
      (value "10K")
      (footprint "eagle-import:CAY16")
      (libsource (lib "eagle-import") (part "4R-NCAY16"))
    )
    (comp (ref "RN7")
      (value "10K")
      (footprint "eagle-import:CAY16")
      (libsource (lib "eagle-import") (part "4R-NCAY16"))
    )
    (comp (ref "RN8")
      (value "10K")
      (footprint "eagle-import:CAY16")
      (libsource (lib "eagle-import") (part "4R-NCAY16"))
    )
    (comp (ref "RN49")
      (value "10K")
      (footprint "eagle-import:CAY16")
      (libsource (lib "eagle-import") (part "4R-NCAY16"))
    )
    (comp (ref "C3")
      (value "10uF")
      (footprint "eagle-import:C0805")
      (libsource (lib "eagle-import") (part "CAP0805"))
    )
    (comp (ref "IC3")
      (value "MCP23017SO")
      (footprint "eagle-import:SO28W")
      (libsource (lib "eagle-import") (part "MCP23017SO"))
    )
    (comp (ref "J11")
      (value "I2C Addr 3")
      (footprint "eagle-import:2X03-P")
      (libsource (lib "eagle-import") (part "M02X3-PIN"))
    )
    (comp (ref "RN17")
      (value "1K")
      (footprint "eagle-import:CAY16")
      (libsource (lib "eagle-import") (part "4R-NCAY16"))
    )
    (comp (ref "RN18")
      (value "1K")
      (footprint "eagle-import:CAY16")
      (libsource (lib "eagle-import") (part "4R-NCAY16"))
    )
    (comp (ref "RN19")
      (value "1K")
      (footprint "eagle-import:CAY16")
      (libsource (lib "eagle-import") (part "4R-NCAY16"))
    )
    (comp (ref "RN20")
      (value "1K")
      (footprint "eagle-import:CAY16")
      (libsource (lib "eagle-import") (part "4R-NCAY16"))
    )
    (comp (ref "RN21")
      (value "10K")
      (footprint "eagle-import:CAY16")
      (libsource (lib "eagle-import") (part "4R-NCAY16"))
    )
    (comp (ref "RN22")
      (value "10K")
      (footprint "eagle-import:CAY16")
      (libsource (lib "eagle-import") (part "4R-NCAY16"))
    )
    (comp (ref "RN23")
      (value "10K")
      (footprint "eagle-import:CAY16")
      (libsource (lib "eagle-import") (part "4R-NCAY16"))
    )
    (comp (ref "RN24")
      (value "10K")
      (footprint "eagle-import:CAY16")
      (libsource (lib "eagle-import") (part "4R-NCAY16"))
    )
    (comp (ref "RN51")
      (value "10K")
      (footprint "eagle-import:CAY16")
      (libsource (lib "eagle-import") (part "4R-NCAY16"))
    )
    (comp (ref "C10")
      (value "10uF")
      (footprint "eagle-import:C0805")
      (libsource (lib "eagle-import") (part "CAP0805"))
    )
    (comp (ref "IC7")
      (value "MCP23017SO")
      (footprint "eagle-import:SO28W")
      (libsource (lib "eagle-import") (part "MCP23017SO"))
    )
    (comp (ref "J13")
      (value "I2C Addr 6")
      (footprint "eagle-import:2X03-P")
      (libsource (lib "eagle-import") (part "M02X3-PIN"))
    )
    (comp (ref "RN55")
      (value "1K")
      (footprint "eagle-import:CAY16")
      (libsource (lib "eagle-import") (part "4R-NCAY16"))
    )
    (comp (ref "RN56")
      (value "1K")
      (footprint "eagle-import:CAY16")
      (libsource (lib "eagle-import") (part "4R-NCAY16"))
    )
    (comp (ref "RN57")
      (value "1K")
      (footprint "eagle-import:CAY16")
      (libsource (lib "eagle-import") (part "4R-NCAY16"))
    )
    (comp (ref "RN58")
      (value "1K")
      (footprint "eagle-import:CAY16")
      (libsource (lib "eagle-import") (part "4R-NCAY16"))
    )
    (comp (ref "RN59")
      (value "10K")
      (footprint "eagle-import:CAY16")
      (libsource (lib "eagle-import") (part "4R-NCAY16"))
    )
    (comp (ref "RN60")
      (value "10K")
      (footprint "eagle-import:CAY16")
      (libsource (lib "eagle-import") (part "4R-NCAY16"))
    )
    (comp (ref "RN61")
      (value "10K")
      (footprint "eagle-import:CAY16")
      (libsource (lib "eagle-import") (part "4R-NCAY16"))
    )
    (comp (ref "RN62")
      (value "10K")
      (footprint "eagle-import:CAY16")
      (libsource (lib "eagle-import") (part "4R-NCAY16"))
    )
    (comp (ref "RN63")
      (value "10K")
      (footprint "eagle-import:CAY16")
      (libsource (lib "eagle-import") (part "4R-NCAY16"))
    )
    (comp (ref "C6")
      (value "10uF")
      (footprint "eagle-import:C0805")
      (libsource (lib "eagle-import") (part "CAP0805"))
    )
    (comp (ref "IC6")
      (value "MCP23017SO")
      (footprint "eagle-import:SO28W")
      (libsource (lib "eagle-import") (part "MCP23017SO"))
    )
    (comp (ref "J8")
      (value "I2C Addr 6")
      (footprint "eagle-import:2X03-P")
      (libsource (lib "eagle-import") (part "M02X3-PIN"))
    )
    (comp (ref "RN37")
      (value "1K")
      (footprint "eagle-import:CAY16")
      (libsource (lib "eagle-import") (part "4R-NCAY16"))
    )
    (comp (ref "RN38")
      (value "1K")
      (footprint "eagle-import:CAY16")
      (libsource (lib "eagle-import") (part "4R-NCAY16"))
    )
    (comp (ref "RN39")
      (value "1K")
      (footprint "eagle-import:CAY16")
      (libsource (lib "eagle-import") (part "4R-NCAY16"))
    )
    (comp (ref "RN40")
      (value "1K")
      (footprint "eagle-import:CAY16")
      (libsource (lib "eagle-import") (part "4R-NCAY16"))
    )
    (comp (ref "RN45")
      (value "10K")
      (footprint "eagle-import:CAY16")
      (libsource (lib "eagle-import") (part "4R-NCAY16"))
    )
    (comp (ref "RN46")
      (value "10K")
      (footprint "eagle-import:CAY16")
      (libsource (lib "eagle-import") (part "4R-NCAY16"))
    )
    (comp (ref "RN47")
      (value "10K")
      (footprint "eagle-import:CAY16")
      (libsource (lib "eagle-import") (part "4R-NCAY16"))
    )
    (comp (ref "RN48")
      (value "10K")
      (footprint "eagle-import:CAY16")
      (libsource (lib "eagle-import") (part "4R-NCAY16"))
    )
    (comp (ref "RN54")
      (value "10K")
      (footprint "eagle-import:CAY16")
      (libsource (lib "eagle-import") (part "4R-NCAY16"))
    )
    (comp (ref "C11")
      (value "10uF")
      (footprint "eagle-import:C0805")
      (libsource (lib "eagle-import") (part "CAP0805"))
    )
    (comp (ref "IC8")
      (value "MCP23017SO")
      (footprint "eagle-import:SO28W")
      (libsource (lib "eagle-import") (part "MCP23017SO"))
    )
    (comp (ref "J14")
      (value "I2C Addr 6")
      (footprint "eagle-import:2X03-P")
      (libsource (lib "eagle-import") (part "M02X3-PIN"))
    )
    (comp (ref "RN64")
      (value "1K")
      (footprint "eagle-import:CAY16")
      (libsource (lib "eagle-import") (part "4R-NCAY16"))
    )
    (comp (ref "RN65")
      (value "1K")
      (footprint "eagle-import:CAY16")
      (libsource (lib "eagle-import") (part "4R-NCAY16"))
    )
    (comp (ref "RN66")
      (value "1K")
      (footprint "eagle-import:CAY16")
      (libsource (lib "eagle-import") (part "4R-NCAY16"))
    )
    (comp (ref "RN67")
      (value "1K")
      (footprint "eagle-import:CAY16")
      (libsource (lib "eagle-import") (part "4R-NCAY16"))
    )
    (comp (ref "RN68")
      (value "10K")
      (footprint "eagle-import:CAY16")
      (libsource (lib "eagle-import") (part "4R-NCAY16"))
    )
    (comp (ref "RN69")
      (value "10K")
      (footprint "eagle-import:CAY16")
      (libsource (lib "eagle-import") (part "4R-NCAY16"))
    )
    (comp (ref "RN70")
      (value "10K")
      (footprint "eagle-import:CAY16")
      (libsource (lib "eagle-import") (part "4R-NCAY16"))
    )
    (comp (ref "RN71")
      (value "10K")
      (footprint "eagle-import:CAY16")
      (libsource (lib "eagle-import") (part "4R-NCAY16"))
    )
    (comp (ref "RN72")
      (value "10K")
      (footprint "eagle-import:CAY16")
      (libsource (lib "eagle-import") (part "4R-NCAY16"))
    )
  )
  (nets
    (net (code "1") (name "1A1") (class "Default")
      (node (ref "J4") (pin "A1") (pinfunction "A1_A1") (pintype "bidirectional"))
      (node (ref "RN1") (pin "5") (pinfunction "2_5") (pintype "passive"))
      (node (ref "RN5") (pin "4") (pinfunction "1_4") (pintype "passive"))
    )
    (net (code "2") (name "1A2") (class "Default")
      (node (ref "J4") (pin "A2") (pinfunction "A2_A2") (pintype "bidirectional"))
      (node (ref "RN1") (pin "6") (pinfunction "2_6") (pintype "passive"))
      (node (ref "RN5") (pin "3") (pinfunction "1_3") (pintype "passive"))
    )
    (net (code "3") (name "1A3") (class "Default")
      (node (ref "J4") (pin "A3") (pinfunction "A3_A3") (pintype "bidirectional"))
      (node (ref "RN1") (pin "7") (pinfunction "2_7") (pintype "passive"))
      (node (ref "RN5") (pin "2") (pinfunction "1_2") (pintype "passive"))
    )
    (net (code "4") (name "1A6") (class "Default")
      (node (ref "J4") (pin "A6") (pinfunction "A6_A6") (pintype "bidirectional"))
      (node (ref "RN1") (pin "8") (pinfunction "2_8") (pintype "passive"))
      (node (ref "RN5") (pin "1") (pinfunction "1_1") (pintype "passive"))
    )
    (net (code "5") (name "1B1") (class "Default")
      (node (ref "J4") (pin "B1") (pinfunction "B1_B1") (pintype "bidirectional"))
      (node (ref "RN3") (pin "5") (pinfunction "2_5") (pintype "passive"))
      (node (ref "RN7") (pin "4") (pinfunction "1_4") (pintype "passive"))
    )
    (net (code "6") (name "1B2") (class "Default")
      (node (ref "J4") (pin "B2") (pinfunction "B2_B2") (pintype "bidirectional"))
      (node (ref "RN3") (pin "6") (pinfunction "2_6") (pintype "passive"))
      (node (ref "RN7") (pin "3") (pinfunction "1_3") (pintype "passive"))
    )
    (net (code "7") (name "1B3") (class "Default")
      (node (ref "J4") (pin "B3") (pinfunction "B3_B3") (pintype "bidirectional"))
      (node (ref "RN3") (pin "7") (pinfunction "2_7") (pintype "passive"))
      (node (ref "RN7") (pin "2") (pinfunction "1_2") (pintype "passive"))
    )
    (net (code "8") (name "1B6") (class "Default")
      (node (ref "J4") (pin "B6") (pinfunction "B6_B6") (pintype "bidirectional"))
      (node (ref "RN3") (pin "8") (pinfunction "2_8") (pintype "passive"))
      (node (ref "RN7") (pin "1") (pinfunction "1_1") (pintype "passive"))
    )
    (net (code "9") (name "1C1") (class "Default")
      (node (ref "J4") (pin "C1") (pinfunction "C1_C1") (pintype "bidirectional"))
      (node (ref "RN13") (pin "4") (pinfunction "1_4") (pintype "passive"))
      (node (ref "RN9") (pin "5") (pinfunction "2_5") (pintype "passive"))
    )
    (net (code "10") (name "1C2") (class "Default")
      (node (ref "J4") (pin "C2") (pinfunction "C2_C2") (pintype "bidirectional"))
      (node (ref "RN13") (pin "3") (pinfunction "1_3") (pintype "passive"))
      (node (ref "RN9") (pin "6") (pinfunction "2_6") (pintype "passive"))
    )
    (net (code "11") (name "1C3") (class "Default")
      (node (ref "J4") (pin "C3") (pinfunction "C3_C3") (pintype "bidirectional"))
      (node (ref "RN13") (pin "2") (pinfunction "1_2") (pintype "passive"))
      (node (ref "RN9") (pin "7") (pinfunction "2_7") (pintype "passive"))
    )
    (net (code "12") (name "1C6") (class "Default")
      (node (ref "J4") (pin "C6") (pinfunction "C6_C6") (pintype "bidirectional"))
      (node (ref "RN13") (pin "1") (pinfunction "1_1") (pintype "passive"))
      (node (ref "RN9") (pin "8") (pinfunction "2_8") (pintype "passive"))
    )
    (net (code "13") (name "1D1") (class "Default")
      (node (ref "J4") (pin "D1") (pinfunction "D1_D1") (pintype "bidirectional"))
      (node (ref "RN11") (pin "5") (pinfunction "2_5") (pintype "passive"))
      (node (ref "RN15") (pin "4") (pinfunction "1_4") (pintype "passive"))
    )
    (net (code "14") (name "1D2") (class "Default")
      (node (ref "J4") (pin "D2") (pinfunction "D2_D2") (pintype "bidirectional"))
      (node (ref "RN11") (pin "6") (pinfunction "2_6") (pintype "passive"))
      (node (ref "RN15") (pin "3") (pinfunction "1_3") (pintype "passive"))
    )
    (net (code "15") (name "1D3") (class "Default")
      (node (ref "J4") (pin "D3") (pinfunction "D3_D3") (pintype "bidirectional"))
      (node (ref "RN11") (pin "7") (pinfunction "2_7") (pintype "passive"))
      (node (ref "RN15") (pin "2") (pinfunction "1_2") (pintype "passive"))
    )
    (net (code "16") (name "1D6") (class "Default")
      (node (ref "J4") (pin "D6") (pinfunction "D6_D6") (pintype "bidirectional"))
      (node (ref "RN11") (pin "8") (pinfunction "2_8") (pintype "passive"))
      (node (ref "RN15") (pin "1") (pinfunction "1_1") (pintype "passive"))
    )
    (net (code "17") (name "1E1") (class "Default")
      (node (ref "J4") (pin "E1") (pinfunction "E1_E1") (pintype "bidirectional"))
      (node (ref "RN2") (pin "5") (pinfunction "2_5") (pintype "passive"))
      (node (ref "RN6") (pin "4") (pinfunction "1_4") (pintype "passive"))
    )
    (net (code "18") (name "1E2") (class "Default")
      (node (ref "J4") (pin "E2") (pinfunction "E2_E2") (pintype "bidirectional"))
      (node (ref "RN2") (pin "6") (pinfunction "2_6") (pintype "passive"))
      (node (ref "RN6") (pin "3") (pinfunction "1_3") (pintype "passive"))
    )
    (net (code "19") (name "1E3") (class "Default")
      (node (ref "J4") (pin "E3") (pinfunction "E3_E3") (pintype "bidirectional"))
      (node (ref "RN2") (pin "7") (pinfunction "2_7") (pintype "passive"))
      (node (ref "RN6") (pin "2") (pinfunction "1_2") (pintype "passive"))
    )
    (net (code "20") (name "1E6") (class "Default")
      (node (ref "J4") (pin "E6") (pinfunction "E6_E6") (pintype "bidirectional"))
      (node (ref "RN2") (pin "8") (pinfunction "2_8") (pintype "passive"))
      (node (ref "RN6") (pin "1") (pinfunction "1_1") (pintype "passive"))
    )
    (net (code "21") (name "1F1") (class "Default")
      (node (ref "J4") (pin "F1") (pinfunction "F1_F1") (pintype "bidirectional"))
      (node (ref "RN4") (pin "5") (pinfunction "2_5") (pintype "passive"))
      (node (ref "RN8") (pin "4") (pinfunction "1_4") (pintype "passive"))
    )
    (net (code "22") (name "1F2") (class "Default")
      (node (ref "J4") (pin "F2") (pinfunction "F2_F2") (pintype "bidirectional"))
      (node (ref "RN4") (pin "6") (pinfunction "2_6") (pintype "passive"))
      (node (ref "RN8") (pin "3") (pinfunction "1_3") (pintype "passive"))
    )
    (net (code "23") (name "1F3") (class "Default")
      (node (ref "J4") (pin "F3") (pinfunction "F3_F3") (pintype "bidirectional"))
      (node (ref "RN4") (pin "7") (pinfunction "2_7") (pintype "passive"))
      (node (ref "RN8") (pin "2") (pinfunction "1_2") (pintype "passive"))
    )
    (net (code "24") (name "1F6") (class "Default")
      (node (ref "J4") (pin "F6") (pinfunction "F6_F6") (pintype "bidirectional"))
      (node (ref "RN4") (pin "8") (pinfunction "2_8") (pintype "passive"))
      (node (ref "RN8") (pin "1") (pinfunction "1_1") (pintype "passive"))
    )
    (net (code "25") (name "1G1") (class "Default")
      (node (ref "J4") (pin "G1") (pinfunction "G1_G1") (pintype "bidirectional"))
      (node (ref "RN10") (pin "5") (pinfunction "2_5") (pintype "passive"))
      (node (ref "RN14") (pin "4") (pinfunction "1_4") (pintype "passive"))
    )
    (net (code "26") (name "1G2") (class "Default")
      (node (ref "J4") (pin "G2") (pinfunction "G2_G2") (pintype "bidirectional"))
      (node (ref "RN10") (pin "6") (pinfunction "2_6") (pintype "passive"))
      (node (ref "RN14") (pin "3") (pinfunction "1_3") (pintype "passive"))
    )
    (net (code "27") (name "1G3") (class "Default")
      (node (ref "J4") (pin "G3") (pinfunction "G3_G3") (pintype "bidirectional"))
      (node (ref "RN10") (pin "7") (pinfunction "2_7") (pintype "passive"))
      (node (ref "RN14") (pin "2") (pinfunction "1_2") (pintype "passive"))
    )
    (net (code "28") (name "1G6") (class "Default")
      (node (ref "J4") (pin "G6") (pinfunction "G6_G6") (pintype "bidirectional"))
      (node (ref "RN10") (pin "8") (pinfunction "2_8") (pintype "passive"))
      (node (ref "RN14") (pin "1") (pinfunction "1_1") (pintype "passive"))
    )
    (net (code "29") (name "1H1") (class "Default")
      (node (ref "J4") (pin "H1") (pinfunction "H1_H1") (pintype "bidirectional"))
      (node (ref "RN12") (pin "5") (pinfunction "2_5") (pintype "passive"))
      (node (ref "RN16") (pin "4") (pinfunction "1_4") (pintype "passive"))
    )
    (net (code "30") (name "1H2") (class "Default")
      (node (ref "J4") (pin "H2") (pinfunction "H2_H2") (pintype "bidirectional"))
      (node (ref "RN12") (pin "6") (pinfunction "2_6") (pintype "passive"))
      (node (ref "RN16") (pin "3") (pinfunction "1_3") (pintype "passive"))
    )
    (net (code "31") (name "1H3") (class "Default")
      (node (ref "J4") (pin "H3") (pinfunction "H3_H3") (pintype "bidirectional"))
      (node (ref "RN12") (pin "7") (pinfunction "2_7") (pintype "passive"))
      (node (ref "RN16") (pin "2") (pinfunction "1_2") (pintype "passive"))
    )
    (net (code "32") (name "1H6") (class "Default")
      (node (ref "J4") (pin "H6") (pinfunction "H6_H6") (pintype "bidirectional"))
      (node (ref "RN12") (pin "8") (pinfunction "2_8") (pintype "passive"))
      (node (ref "RN16") (pin "1") (pinfunction "1_1") (pintype "passive"))
    )
    (net (code "33") (name "2A1") (class "Default")
      (node (ref "J5") (pin "A1") (pinfunction "A1_A1") (pintype "bidirectional"))
      (node (ref "RN17") (pin "5") (pinfunction "2_5") (pintype "passive"))
      (node (ref "RN21") (pin "4") (pinfunction "1_4") (pintype "passive"))
    )
    (net (code "34") (name "2A2") (class "Default")
      (node (ref "J5") (pin "A2") (pinfunction "A2_A2") (pintype "bidirectional"))
      (node (ref "RN17") (pin "6") (pinfunction "2_6") (pintype "passive"))
      (node (ref "RN21") (pin "3") (pinfunction "1_3") (pintype "passive"))
    )
    (net (code "35") (name "2A3") (class "Default")
      (node (ref "J5") (pin "A3") (pinfunction "A3_A3") (pintype "bidirectional"))
      (node (ref "RN17") (pin "7") (pinfunction "2_7") (pintype "passive"))
      (node (ref "RN21") (pin "2") (pinfunction "1_2") (pintype "passive"))
    )
    (net (code "36") (name "2A6") (class "Default")
      (node (ref "J5") (pin "A6") (pinfunction "A6_A6") (pintype "bidirectional"))
      (node (ref "RN17") (pin "8") (pinfunction "2_8") (pintype "passive"))
      (node (ref "RN21") (pin "1") (pinfunction "1_1") (pintype "passive"))
    )
    (net (code "37") (name "2B1") (class "Default")
      (node (ref "J5") (pin "B1") (pinfunction "B1_B1") (pintype "bidirectional"))
      (node (ref "RN19") (pin "5") (pinfunction "2_5") (pintype "passive"))
      (node (ref "RN23") (pin "4") (pinfunction "1_4") (pintype "passive"))
    )
    (net (code "38") (name "2B2") (class "Default")
      (node (ref "J5") (pin "B2") (pinfunction "B2_B2") (pintype "bidirectional"))
      (node (ref "RN19") (pin "6") (pinfunction "2_6") (pintype "passive"))
      (node (ref "RN23") (pin "3") (pinfunction "1_3") (pintype "passive"))
    )
    (net (code "39") (name "2B3") (class "Default")
      (node (ref "J5") (pin "B3") (pinfunction "B3_B3") (pintype "bidirectional"))
      (node (ref "RN19") (pin "7") (pinfunction "2_7") (pintype "passive"))
      (node (ref "RN23") (pin "2") (pinfunction "1_2") (pintype "passive"))
    )
    (net (code "40") (name "2B6") (class "Default")
      (node (ref "J5") (pin "B6") (pinfunction "B6_B6") (pintype "bidirectional"))
      (node (ref "RN19") (pin "8") (pinfunction "2_8") (pintype "passive"))
      (node (ref "RN23") (pin "1") (pinfunction "1_1") (pintype "passive"))
    )
    (net (code "41") (name "2C1") (class "Default")
      (node (ref "J5") (pin "C1") (pinfunction "C1_C1") (pintype "bidirectional"))
      (node (ref "RN25") (pin "5") (pinfunction "2_5") (pintype "passive"))
      (node (ref "RN29") (pin "4") (pinfunction "1_4") (pintype "passive"))
    )
    (net (code "42") (name "2C2") (class "Default")
      (node (ref "J5") (pin "C2") (pinfunction "C2_C2") (pintype "bidirectional"))
      (node (ref "RN25") (pin "6") (pinfunction "2_6") (pintype "passive"))
      (node (ref "RN29") (pin "3") (pinfunction "1_3") (pintype "passive"))
    )
    (net (code "43") (name "2C3") (class "Default")
      (node (ref "J5") (pin "C3") (pinfunction "C3_C3") (pintype "bidirectional"))
      (node (ref "RN25") (pin "7") (pinfunction "2_7") (pintype "passive"))
      (node (ref "RN29") (pin "2") (pinfunction "1_2") (pintype "passive"))
    )
    (net (code "44") (name "2C6") (class "Default")
      (node (ref "J5") (pin "C6") (pinfunction "C6_C6") (pintype "bidirectional"))
      (node (ref "RN25") (pin "8") (pinfunction "2_8") (pintype "passive"))
      (node (ref "RN29") (pin "1") (pinfunction "1_1") (pintype "passive"))
    )
    (net (code "45") (name "2D1") (class "Default")
      (node (ref "J5") (pin "D1") (pinfunction "D1_D1") (pintype "bidirectional"))
      (node (ref "RN27") (pin "5") (pinfunction "2_5") (pintype "passive"))
      (node (ref "RN31") (pin "4") (pinfunction "1_4") (pintype "passive"))
    )
    (net (code "46") (name "2D2") (class "Default")
      (node (ref "J5") (pin "D2") (pinfunction "D2_D2") (pintype "bidirectional"))
      (node (ref "RN27") (pin "6") (pinfunction "2_6") (pintype "passive"))
      (node (ref "RN31") (pin "3") (pinfunction "1_3") (pintype "passive"))
    )
    (net (code "47") (name "2D3") (class "Default")
      (node (ref "J5") (pin "D3") (pinfunction "D3_D3") (pintype "bidirectional"))
      (node (ref "RN27") (pin "7") (pinfunction "2_7") (pintype "passive"))
      (node (ref "RN31") (pin "2") (pinfunction "1_2") (pintype "passive"))
    )
    (net (code "48") (name "2D6") (class "Default")
      (node (ref "J5") (pin "D6") (pinfunction "D6_D6") (pintype "bidirectional"))
      (node (ref "RN27") (pin "8") (pinfunction "2_8") (pintype "passive"))
      (node (ref "RN31") (pin "1") (pinfunction "1_1") (pintype "passive"))
    )
    (net (code "49") (name "2E1") (class "Default")
      (node (ref "J5") (pin "E1") (pinfunction "E1_E1") (pintype "bidirectional"))
      (node (ref "RN18") (pin "5") (pinfunction "2_5") (pintype "passive"))
      (node (ref "RN22") (pin "4") (pinfunction "1_4") (pintype "passive"))
    )
    (net (code "50") (name "2E2") (class "Default")
      (node (ref "J5") (pin "E2") (pinfunction "E2_E2") (pintype "bidirectional"))
      (node (ref "RN18") (pin "6") (pinfunction "2_6") (pintype "passive"))
      (node (ref "RN22") (pin "3") (pinfunction "1_3") (pintype "passive"))
    )
    (net (code "51") (name "2E3") (class "Default")
      (node (ref "J5") (pin "E3") (pinfunction "E3_E3") (pintype "bidirectional"))
      (node (ref "RN18") (pin "7") (pinfunction "2_7") (pintype "passive"))
      (node (ref "RN22") (pin "2") (pinfunction "1_2") (pintype "passive"))
    )
    (net (code "52") (name "2E6") (class "Default")
      (node (ref "J5") (pin "E6") (pinfunction "E6_E6") (pintype "bidirectional"))
      (node (ref "RN18") (pin "8") (pinfunction "2_8") (pintype "passive"))
      (node (ref "RN22") (pin "1") (pinfunction "1_1") (pintype "passive"))
    )
    (net (code "53") (name "2F1") (class "Default")
      (node (ref "J5") (pin "F1") (pinfunction "F1_F1") (pintype "bidirectional"))
      (node (ref "RN20") (pin "5") (pinfunction "2_5") (pintype "passive"))
      (node (ref "RN24") (pin "4") (pinfunction "1_4") (pintype "passive"))
    )
    (net (code "54") (name "2F2") (class "Default")
      (node (ref "J5") (pin "F2") (pinfunction "F2_F2") (pintype "bidirectional"))
      (node (ref "RN20") (pin "6") (pinfunction "2_6") (pintype "passive"))
      (node (ref "RN24") (pin "3") (pinfunction "1_3") (pintype "passive"))
    )
    (net (code "55") (name "2F3") (class "Default")
      (node (ref "J5") (pin "F3") (pinfunction "F3_F3") (pintype "bidirectional"))
      (node (ref "RN20") (pin "7") (pinfunction "2_7") (pintype "passive"))
      (node (ref "RN24") (pin "2") (pinfunction "1_2") (pintype "passive"))
    )
    (net (code "56") (name "2F6") (class "Default")
      (node (ref "J5") (pin "F6") (pinfunction "F6_F6") (pintype "bidirectional"))
      (node (ref "RN20") (pin "8") (pinfunction "2_8") (pintype "passive"))
      (node (ref "RN24") (pin "1") (pinfunction "1_1") (pintype "passive"))
    )
    (net (code "57") (name "2G1") (class "Default")
      (node (ref "J5") (pin "G1") (pinfunction "G1_G1") (pintype "bidirectional"))
      (node (ref "RN26") (pin "5") (pinfunction "2_5") (pintype "passive"))
      (node (ref "RN30") (pin "4") (pinfunction "1_4") (pintype "passive"))
    )
    (net (code "58") (name "2G2") (class "Default")
      (node (ref "J5") (pin "G2") (pinfunction "G2_G2") (pintype "bidirectional"))
      (node (ref "RN26") (pin "6") (pinfunction "2_6") (pintype "passive"))
      (node (ref "RN30") (pin "3") (pinfunction "1_3") (pintype "passive"))
    )
    (net (code "59") (name "2G3") (class "Default")
      (node (ref "J5") (pin "G3") (pinfunction "G3_G3") (pintype "bidirectional"))
      (node (ref "RN26") (pin "7") (pinfunction "2_7") (pintype "passive"))
      (node (ref "RN30") (pin "2") (pinfunction "1_2") (pintype "passive"))
    )
    (net (code "60") (name "2G6") (class "Default")
      (node (ref "J5") (pin "G6") (pinfunction "G6_G6") (pintype "bidirectional"))
      (node (ref "RN26") (pin "8") (pinfunction "2_8") (pintype "passive"))
      (node (ref "RN30") (pin "1") (pinfunction "1_1") (pintype "passive"))
    )
    (net (code "61") (name "2H1") (class "Default")
      (node (ref "J5") (pin "H1") (pinfunction "H1_H1") (pintype "bidirectional"))
      (node (ref "RN28") (pin "5") (pinfunction "2_5") (pintype "passive"))
      (node (ref "RN32") (pin "4") (pinfunction "1_4") (pintype "passive"))
    )
    (net (code "62") (name "2H2") (class "Default")
      (node (ref "J5") (pin "H2") (pinfunction "H2_H2") (pintype "bidirectional"))
      (node (ref "RN28") (pin "6") (pinfunction "2_6") (pintype "passive"))
      (node (ref "RN32") (pin "3") (pinfunction "1_3") (pintype "passive"))
    )
    (net (code "63") (name "2H3") (class "Default")
      (node (ref "J5") (pin "H3") (pinfunction "H3_H3") (pintype "bidirectional"))
      (node (ref "RN28") (pin "7") (pinfunction "2_7") (pintype "passive"))
      (node (ref "RN32") (pin "2") (pinfunction "1_2") (pintype "passive"))
    )
    (net (code "64") (name "2H6") (class "Default")
      (node (ref "J5") (pin "H6") (pinfunction "H6_H6") (pintype "bidirectional"))
      (node (ref "RN28") (pin "8") (pinfunction "2_8") (pintype "passive"))
      (node (ref "RN32") (pin "1") (pinfunction "1_1") (pintype "passive"))
    )
    (net (code "65") (name "3A1") (class "Default")
      (node (ref "J6") (pin "A1") (pinfunction "A1_A1") (pintype "bidirectional"))
      (node (ref "RN33") (pin "5") (pinfunction "2_5") (pintype "passive"))
      (node (ref "RN44") (pin "4") (pinfunction "1_4") (pintype "passive"))
    )
    (net (code "66") (name "3A2") (class "Default")
      (node (ref "J6") (pin "A2") (pinfunction "A2_A2") (pintype "bidirectional"))
      (node (ref "RN33") (pin "6") (pinfunction "2_6") (pintype "passive"))
      (node (ref "RN44") (pin "3") (pinfunction "1_3") (pintype "passive"))
    )
    (net (code "67") (name "3A3") (class "Default")
      (node (ref "J6") (pin "A3") (pinfunction "A3_A3") (pintype "bidirectional"))
      (node (ref "RN33") (pin "7") (pinfunction "2_7") (pintype "passive"))
      (node (ref "RN44") (pin "2") (pinfunction "1_2") (pintype "passive"))
    )
    (net (code "68") (name "3A6") (class "Default")
      (node (ref "J6") (pin "A6") (pinfunction "A6_A6") (pintype "bidirectional"))
      (node (ref "RN33") (pin "8") (pinfunction "2_8") (pintype "passive"))
      (node (ref "RN44") (pin "1") (pinfunction "1_1") (pintype "passive"))
    )
    (net (code "69") (name "3B1") (class "Default")
      (node (ref "J6") (pin "B1") (pinfunction "B1_B1") (pintype "bidirectional"))
      (node (ref "RN35") (pin "5") (pinfunction "2_5") (pintype "passive"))
      (node (ref "RN42") (pin "4") (pinfunction "1_4") (pintype "passive"))
    )
    (net (code "70") (name "3B2") (class "Default")
      (node (ref "J6") (pin "B2") (pinfunction "B2_B2") (pintype "bidirectional"))
      (node (ref "RN35") (pin "6") (pinfunction "2_6") (pintype "passive"))
      (node (ref "RN42") (pin "3") (pinfunction "1_3") (pintype "passive"))
    )
    (net (code "71") (name "3B3") (class "Default")
      (node (ref "J6") (pin "B3") (pinfunction "B3_B3") (pintype "bidirectional"))
      (node (ref "RN35") (pin "7") (pinfunction "2_7") (pintype "passive"))
      (node (ref "RN42") (pin "2") (pinfunction "1_2") (pintype "passive"))
    )
    (net (code "72") (name "3B6") (class "Default")
      (node (ref "J6") (pin "B6") (pinfunction "B6_B6") (pintype "bidirectional"))
      (node (ref "RN35") (pin "8") (pinfunction "2_8") (pintype "passive"))
      (node (ref "RN42") (pin "1") (pinfunction "1_1") (pintype "passive"))
    )
    (net (code "73") (name "3C1") (class "Default")
      (node (ref "J6") (pin "C1") (pinfunction "C1_C1") (pintype "bidirectional"))
      (node (ref "RN37") (pin "5") (pinfunction "2_5") (pintype "passive"))
      (node (ref "RN48") (pin "4") (pinfunction "1_4") (pintype "passive"))
    )
    (net (code "74") (name "3C2") (class "Default")
      (node (ref "J6") (pin "C2") (pinfunction "C2_C2") (pintype "bidirectional"))
      (node (ref "RN37") (pin "6") (pinfunction "2_6") (pintype "passive"))
      (node (ref "RN48") (pin "3") (pinfunction "1_3") (pintype "passive"))
    )
    (net (code "75") (name "3C3") (class "Default")
      (node (ref "J6") (pin "C3") (pinfunction "C3_C3") (pintype "bidirectional"))
      (node (ref "RN37") (pin "7") (pinfunction "2_7") (pintype "passive"))
      (node (ref "RN48") (pin "2") (pinfunction "1_2") (pintype "passive"))
    )
    (net (code "76") (name "3C6") (class "Default")
      (node (ref "J6") (pin "C6") (pinfunction "C6_C6") (pintype "bidirectional"))
      (node (ref "RN37") (pin "8") (pinfunction "2_8") (pintype "passive"))
      (node (ref "RN48") (pin "1") (pinfunction "1_1") (pintype "passive"))
    )
    (net (code "77") (name "3D1") (class "Default")
      (node (ref "J6") (pin "D1") (pinfunction "D1_D1") (pintype "bidirectional"))
      (node (ref "RN39") (pin "5") (pinfunction "2_5") (pintype "passive"))
      (node (ref "RN46") (pin "4") (pinfunction "1_4") (pintype "passive"))
    )
    (net (code "78") (name "3D2") (class "Default")
      (node (ref "J6") (pin "D2") (pinfunction "D2_D2") (pintype "bidirectional"))
      (node (ref "RN39") (pin "6") (pinfunction "2_6") (pintype "passive"))
      (node (ref "RN46") (pin "3") (pinfunction "1_3") (pintype "passive"))
    )
    (net (code "79") (name "3D3") (class "Default")
      (node (ref "J6") (pin "D3") (pinfunction "D3_D3") (pintype "bidirectional"))
      (node (ref "RN39") (pin "7") (pinfunction "2_7") (pintype "passive"))
      (node (ref "RN46") (pin "2") (pinfunction "1_2") (pintype "passive"))
    )
    (net (code "80") (name "3D6") (class "Default")
      (node (ref "J6") (pin "D6") (pinfunction "D6_D6") (pintype "bidirectional"))
      (node (ref "RN39") (pin "8") (pinfunction "2_8") (pintype "passive"))
      (node (ref "RN46") (pin "1") (pinfunction "1_1") (pintype "passive"))
    )
    (net (code "81") (name "3E1") (class "Default")
      (node (ref "J6") (pin "E1") (pinfunction "E1_E1") (pintype "bidirectional"))
      (node (ref "RN34") (pin "5") (pinfunction "2_5") (pintype "passive"))
      (node (ref "RN43") (pin "4") (pinfunction "1_4") (pintype "passive"))
    )
    (net (code "82") (name "3E2") (class "Default")
      (node (ref "J6") (pin "E2") (pinfunction "E2_E2") (pintype "bidirectional"))
      (node (ref "RN34") (pin "6") (pinfunction "2_6") (pintype "passive"))
      (node (ref "RN43") (pin "3") (pinfunction "1_3") (pintype "passive"))
    )
    (net (code "83") (name "3E3") (class "Default")
      (node (ref "J6") (pin "E3") (pinfunction "E3_E3") (pintype "bidirectional"))
      (node (ref "RN34") (pin "7") (pinfunction "2_7") (pintype "passive"))
      (node (ref "RN43") (pin "2") (pinfunction "1_2") (pintype "passive"))
    )
    (net (code "84") (name "3E6") (class "Default")
      (node (ref "J6") (pin "E6") (pinfunction "E6_E6") (pintype "bidirectional"))
      (node (ref "RN34") (pin "8") (pinfunction "2_8") (pintype "passive"))
      (node (ref "RN43") (pin "1") (pinfunction "1_1") (pintype "passive"))
    )
    (net (code "85") (name "3F1") (class "Default")
      (node (ref "J6") (pin "F1") (pinfunction "F1_F1") (pintype "bidirectional"))
      (node (ref "RN36") (pin "5") (pinfunction "2_5") (pintype "passive"))
      (node (ref "RN41") (pin "4") (pinfunction "1_4") (pintype "passive"))
    )
    (net (code "86") (name "3F2") (class "Default")
      (node (ref "J6") (pin "F2") (pinfunction "F2_F2") (pintype "bidirectional"))
      (node (ref "RN36") (pin "6") (pinfunction "2_6") (pintype "passive"))
      (node (ref "RN41") (pin "3") (pinfunction "1_3") (pintype "passive"))
    )
    (net (code "87") (name "3F3") (class "Default")
      (node (ref "J6") (pin "F3") (pinfunction "F3_F3") (pintype "bidirectional"))
      (node (ref "RN36") (pin "7") (pinfunction "2_7") (pintype "passive"))
      (node (ref "RN41") (pin "2") (pinfunction "1_2") (pintype "passive"))
    )
    (net (code "88") (name "3F6") (class "Default")
      (node (ref "J6") (pin "F6") (pinfunction "F6_F6") (pintype "bidirectional"))
      (node (ref "RN36") (pin "8") (pinfunction "2_8") (pintype "passive"))
      (node (ref "RN41") (pin "1") (pinfunction "1_1") (pintype "passive"))
    )
    (net (code "89") (name "3G1") (class "Default")
      (node (ref "J6") (pin "G1") (pinfunction "G1_G1") (pintype "bidirectional"))
      (node (ref "RN38") (pin "5") (pinfunction "2_5") (pintype "passive"))
      (node (ref "RN47") (pin "4") (pinfunction "1_4") (pintype "passive"))
    )
    (net (code "90") (name "3G2") (class "Default")
      (node (ref "J6") (pin "G2") (pinfunction "G2_G2") (pintype "bidirectional"))
      (node (ref "RN38") (pin "6") (pinfunction "2_6") (pintype "passive"))
      (node (ref "RN47") (pin "3") (pinfunction "1_3") (pintype "passive"))
    )
    (net (code "91") (name "3G3") (class "Default")
      (node (ref "J6") (pin "G3") (pinfunction "G3_G3") (pintype "bidirectional"))
      (node (ref "RN38") (pin "7") (pinfunction "2_7") (pintype "passive"))
      (node (ref "RN47") (pin "2") (pinfunction "1_2") (pintype "passive"))
    )
    (net (code "92") (name "3G6") (class "Default")
      (node (ref "J6") (pin "G6") (pinfunction "G6_G6") (pintype "bidirectional"))
      (node (ref "RN38") (pin "8") (pinfunction "2_8") (pintype "passive"))
      (node (ref "RN47") (pin "1") (pinfunction "1_1") (pintype "passive"))
    )
    (net (code "93") (name "3H1") (class "Default")
      (node (ref "J6") (pin "H1") (pinfunction "H1_H1") (pintype "bidirectional"))
      (node (ref "RN40") (pin "5") (pinfunction "2_5") (pintype "passive"))
      (node (ref "RN45") (pin "4") (pinfunction "1_4") (pintype "passive"))
    )
    (net (code "94") (name "3H2") (class "Default")
      (node (ref "J6") (pin "H2") (pinfunction "H2_H2") (pintype "bidirectional"))
      (node (ref "RN40") (pin "6") (pinfunction "2_6") (pintype "passive"))
      (node (ref "RN45") (pin "3") (pinfunction "1_3") (pintype "passive"))
    )
    (net (code "95") (name "3H3") (class "Default")
      (node (ref "J6") (pin "H3") (pinfunction "H3_H3") (pintype "bidirectional"))
      (node (ref "RN40") (pin "7") (pinfunction "2_7") (pintype "passive"))
      (node (ref "RN45") (pin "2") (pinfunction "1_2") (pintype "passive"))
    )
    (net (code "96") (name "3H6") (class "Default")
      (node (ref "J6") (pin "H6") (pinfunction "H6_H6") (pintype "bidirectional"))
      (node (ref "RN40") (pin "8") (pinfunction "2_8") (pintype "passive"))
      (node (ref "RN45") (pin "1") (pinfunction "1_1") (pintype "passive"))
    )
    (net (code "97") (name "4A1") (class "Default")
      (node (ref "J15") (pin "A1") (pinfunction "A1_A1") (pintype "bidirectional"))
      (node (ref "RN55") (pin "5") (pinfunction "2_5") (pintype "passive"))
      (node (ref "RN62") (pin "4") (pinfunction "1_4") (pintype "passive"))
    )
    (net (code "98") (name "4A2") (class "Default")
      (node (ref "J15") (pin "A2") (pinfunction "A2_A2") (pintype "bidirectional"))
      (node (ref "RN55") (pin "6") (pinfunction "2_6") (pintype "passive"))
      (node (ref "RN62") (pin "3") (pinfunction "1_3") (pintype "passive"))
    )
    (net (code "99") (name "4A3") (class "Default")
      (node (ref "J15") (pin "A3") (pinfunction "A3_A3") (pintype "bidirectional"))
      (node (ref "RN55") (pin "7") (pinfunction "2_7") (pintype "passive"))
      (node (ref "RN62") (pin "2") (pinfunction "1_2") (pintype "passive"))
    )
    (net (code "100") (name "4A6") (class "Default")
      (node (ref "J15") (pin "A6") (pinfunction "A6_A6") (pintype "bidirectional"))
      (node (ref "RN55") (pin "8") (pinfunction "2_8") (pintype "passive"))
      (node (ref "RN62") (pin "1") (pinfunction "1_1") (pintype "passive"))
    )
    (net (code "101") (name "4B1") (class "Default")
      (node (ref "J15") (pin "B1") (pinfunction "B1_B1") (pintype "bidirectional"))
      (node (ref "RN57") (pin "5") (pinfunction "2_5") (pintype "passive"))
      (node (ref "RN60") (pin "4") (pinfunction "1_4") (pintype "passive"))
    )
    (net (code "102") (name "4B2") (class "Default")
      (node (ref "J15") (pin "B2") (pinfunction "B2_B2") (pintype "bidirectional"))
      (node (ref "RN57") (pin "6") (pinfunction "2_6") (pintype "passive"))
      (node (ref "RN60") (pin "3") (pinfunction "1_3") (pintype "passive"))
    )
    (net (code "103") (name "4B3") (class "Default")
      (node (ref "J15") (pin "B3") (pinfunction "B3_B3") (pintype "bidirectional"))
      (node (ref "RN57") (pin "7") (pinfunction "2_7") (pintype "passive"))
      (node (ref "RN60") (pin "2") (pinfunction "1_2") (pintype "passive"))
    )
    (net (code "104") (name "4B6") (class "Default")
      (node (ref "J15") (pin "B6") (pinfunction "B6_B6") (pintype "bidirectional"))
      (node (ref "RN57") (pin "8") (pinfunction "2_8") (pintype "passive"))
      (node (ref "RN60") (pin "1") (pinfunction "1_1") (pintype "passive"))
    )
    (net (code "105") (name "4C1") (class "Default")
      (node (ref "J15") (pin "C1") (pinfunction "C1_C1") (pintype "bidirectional"))
      (node (ref "RN64") (pin "5") (pinfunction "2_5") (pintype "passive"))
      (node (ref "RN71") (pin "4") (pinfunction "1_4") (pintype "passive"))
    )
    (net (code "106") (name "4C2") (class "Default")
      (node (ref "J15") (pin "C2") (pinfunction "C2_C2") (pintype "bidirectional"))
      (node (ref "RN64") (pin "6") (pinfunction "2_6") (pintype "passive"))
      (node (ref "RN71") (pin "3") (pinfunction "1_3") (pintype "passive"))
    )
    (net (code "107") (name "4C3") (class "Default")
      (node (ref "J15") (pin "C3") (pinfunction "C3_C3") (pintype "bidirectional"))
      (node (ref "RN64") (pin "7") (pinfunction "2_7") (pintype "passive"))
      (node (ref "RN71") (pin "2") (pinfunction "1_2") (pintype "passive"))
    )
    (net (code "108") (name "4C6") (class "Default")
      (node (ref "J15") (pin "C6") (pinfunction "C6_C6") (pintype "bidirectional"))
      (node (ref "RN64") (pin "8") (pinfunction "2_8") (pintype "passive"))
      (node (ref "RN71") (pin "1") (pinfunction "1_1") (pintype "passive"))
    )
    (net (code "109") (name "4D1") (class "Default")
      (node (ref "J15") (pin "D1") (pinfunction "D1_D1") (pintype "bidirectional"))
      (node (ref "RN66") (pin "5") (pinfunction "2_5") (pintype "passive"))
      (node (ref "RN69") (pin "4") (pinfunction "1_4") (pintype "passive"))
    )
    (net (code "110") (name "4D2") (class "Default")
      (node (ref "J15") (pin "D2") (pinfunction "D2_D2") (pintype "bidirectional"))
      (node (ref "RN66") (pin "6") (pinfunction "2_6") (pintype "passive"))
      (node (ref "RN69") (pin "3") (pinfunction "1_3") (pintype "passive"))
    )
    (net (code "111") (name "4D3") (class "Default")
      (node (ref "J15") (pin "D3") (pinfunction "D3_D3") (pintype "bidirectional"))
      (node (ref "RN66") (pin "7") (pinfunction "2_7") (pintype "passive"))
      (node (ref "RN69") (pin "2") (pinfunction "1_2") (pintype "passive"))
    )
    (net (code "112") (name "4D6") (class "Default")
      (node (ref "J15") (pin "D6") (pinfunction "D6_D6") (pintype "bidirectional"))
      (node (ref "RN66") (pin "8") (pinfunction "2_8") (pintype "passive"))
      (node (ref "RN69") (pin "1") (pinfunction "1_1") (pintype "passive"))
    )
    (net (code "113") (name "4E1") (class "Default")
      (node (ref "J15") (pin "E1") (pinfunction "E1_E1") (pintype "bidirectional"))
      (node (ref "RN56") (pin "5") (pinfunction "2_5") (pintype "passive"))
      (node (ref "RN61") (pin "4") (pinfunction "1_4") (pintype "passive"))
    )
    (net (code "114") (name "4E2") (class "Default")
      (node (ref "J15") (pin "E2") (pinfunction "E2_E2") (pintype "bidirectional"))
      (node (ref "RN56") (pin "6") (pinfunction "2_6") (pintype "passive"))
      (node (ref "RN61") (pin "3") (pinfunction "1_3") (pintype "passive"))
    )
    (net (code "115") (name "4E3") (class "Default")
      (node (ref "J15") (pin "E3") (pinfunction "E3_E3") (pintype "bidirectional"))
      (node (ref "RN56") (pin "7") (pinfunction "2_7") (pintype "passive"))
      (node (ref "RN61") (pin "2") (pinfunction "1_2") (pintype "passive"))
    )
    (net (code "116") (name "4E6") (class "Default")
      (node (ref "J15") (pin "E6") (pinfunction "E6_E6") (pintype "bidirectional"))
      (node (ref "RN56") (pin "8") (pinfunction "2_8") (pintype "passive"))
      (node (ref "RN61") (pin "1") (pinfunction "1_1") (pintype "passive"))
    )
    (net (code "117") (name "4F1") (class "Default")
      (node (ref "J15") (pin "F1") (pinfunction "F1_F1") (pintype "bidirectional"))
      (node (ref "RN58") (pin "5") (pinfunction "2_5") (pintype "passive"))
      (node (ref "RN59") (pin "4") (pinfunction "1_4") (pintype "passive"))
    )
    (net (code "118") (name "4F2") (class "Default")
      (node (ref "J15") (pin "F2") (pinfunction "F2_F2") (pintype "bidirectional"))
      (node (ref "RN58") (pin "6") (pinfunction "2_6") (pintype "passive"))
      (node (ref "RN59") (pin "3") (pinfunction "1_3") (pintype "passive"))
    )
    (net (code "119") (name "4F3") (class "Default")
      (node (ref "J15") (pin "F3") (pinfunction "F3_F3") (pintype "bidirectional"))
      (node (ref "RN58") (pin "7") (pinfunction "2_7") (pintype "passive"))
      (node (ref "RN59") (pin "2") (pinfunction "1_2") (pintype "passive"))
    )
    (net (code "120") (name "4F6") (class "Default")
      (node (ref "J15") (pin "F6") (pinfunction "F6_F6") (pintype "bidirectional"))
      (node (ref "RN58") (pin "8") (pinfunction "2_8") (pintype "passive"))
      (node (ref "RN59") (pin "1") (pinfunction "1_1") (pintype "passive"))
    )
    (net (code "121") (name "4G1") (class "Default")
      (node (ref "J15") (pin "G1") (pinfunction "G1_G1") (pintype "bidirectional"))
      (node (ref "RN65") (pin "5") (pinfunction "2_5") (pintype "passive"))
      (node (ref "RN70") (pin "4") (pinfunction "1_4") (pintype "passive"))
    )
    (net (code "122") (name "4G2") (class "Default")
      (node (ref "J15") (pin "G2") (pinfunction "G2_G2") (pintype "bidirectional"))
      (node (ref "RN65") (pin "6") (pinfunction "2_6") (pintype "passive"))
      (node (ref "RN70") (pin "3") (pinfunction "1_3") (pintype "passive"))
    )
    (net (code "123") (name "4G3") (class "Default")
      (node (ref "J15") (pin "G3") (pinfunction "G3_G3") (pintype "bidirectional"))
      (node (ref "RN65") (pin "7") (pinfunction "2_7") (pintype "passive"))
      (node (ref "RN70") (pin "2") (pinfunction "1_2") (pintype "passive"))
    )
    (net (code "124") (name "4G6") (class "Default")
      (node (ref "J15") (pin "G6") (pinfunction "G6_G6") (pintype "bidirectional"))
      (node (ref "RN65") (pin "8") (pinfunction "2_8") (pintype "passive"))
      (node (ref "RN70") (pin "1") (pinfunction "1_1") (pintype "passive"))
    )
    (net (code "125") (name "4H1") (class "Default")
      (node (ref "J15") (pin "H1") (pinfunction "H1_H1") (pintype "bidirectional"))
      (node (ref "RN67") (pin "5") (pinfunction "2_5") (pintype "passive"))
      (node (ref "RN68") (pin "4") (pinfunction "1_4") (pintype "passive"))
    )
    (net (code "126") (name "4H2") (class "Default")
      (node (ref "J15") (pin "H2") (pinfunction "H2_H2") (pintype "bidirectional"))
      (node (ref "RN67") (pin "6") (pinfunction "2_6") (pintype "passive"))
      (node (ref "RN68") (pin "3") (pinfunction "1_3") (pintype "passive"))
    )
    (net (code "127") (name "4H3") (class "Default")
      (node (ref "J15") (pin "H3") (pinfunction "H3_H3") (pintype "bidirectional"))
      (node (ref "RN67") (pin "7") (pinfunction "2_7") (pintype "passive"))
      (node (ref "RN68") (pin "2") (pinfunction "1_2") (pintype "passive"))
    )
    (net (code "128") (name "4H6") (class "Default")
      (node (ref "J15") (pin "H6") (pinfunction "H6_H6") (pintype "bidirectional"))
      (node (ref "RN67") (pin "8") (pinfunction "2_8") (pintype "passive"))
      (node (ref "RN68") (pin "1") (pinfunction "1_1") (pintype "passive"))
    )
    (net (code "129") (name "GND") (class "Default")
      (node (ref "C1") (pin "2") (pinfunction "2_2") (pintype "passive"))
      (node (ref "C10") (pin "2") (pinfunction "2_2") (pintype "passive"))
      (node (ref "C11") (pin "2") (pinfunction "2_2") (pintype "passive"))
      (node (ref "C12") (pin "-") (pinfunction "-_-") (pintype "passive"))
      (node (ref "C2") (pin "2") (pinfunction "2_2") (pintype "passive"))
      (node (ref "C3") (pin "2") (pinfunction "2_2") (pintype "passive"))
      (node (ref "C4") (pin "2") (pinfunction "2_2") (pintype "passive"))
      (node (ref "C5") (pin "2") (pinfunction "2_2") (pintype "passive"))
      (node (ref "C6") (pin "2") (pinfunction "2_2") (pintype "passive"))
      (node (ref "C7") (pin "-") (pinfunction "-_-") (pintype "passive"))
      (node (ref "C8") (pin "-") (pinfunction "-_-") (pintype "passive"))
      (node (ref "C9") (pin "-") (pinfunction "-_-") (pintype "passive"))
      (node (ref "IC1") (pin "10") (pinfunction "VSS_10") (pintype "power_in"))
      (node (ref "IC2") (pin "10") (pinfunction "VSS_10") (pintype "power_in"))
      (node (ref "IC3") (pin "10") (pinfunction "VSS_10") (pintype "power_in"))
      (node (ref "IC4") (pin "10") (pinfunction "VSS_10") (pintype "power_in"))
      (node (ref "IC5") (pin "10") (pinfunction "VSS_10") (pintype "power_in"))
      (node (ref "IC6") (pin "10") (pinfunction "VSS_10") (pintype "power_in"))
      (node (ref "IC7") (pin "10") (pinfunction "VSS_10") (pintype "power_in"))
      (node (ref "IC8") (pin "10") (pinfunction "VSS_10") (pintype "power_in"))
      (node (ref "J1") (pin "4") (pinfunction "4_4") (pintype "passive"))
      (node (ref "J15") (pin "A7") (pinfunction "A7_A7") (pintype "bidirectional"))
      (node (ref "J15") (pin "A8") (pinfunction "A8_A8") (pintype "bidirectional"))
      (node (ref "J15") (pin "B7") (pinfunction "B7_B7") (pintype "bidirectional"))
      (node (ref "J15") (pin "B8") (pinfunction "B8_B8") (pintype "bidirectional"))
      (node (ref "J15") (pin "C7") (pinfunction "C7_C7") (pintype "bidirectional"))
      (node (ref "J15") (pin "C8") (pinfunction "C8_C8") (pintype "bidirectional"))
      (node (ref "J15") (pin "D7") (pinfunction "D7_D7") (pintype "bidirectional"))
      (node (ref "J15") (pin "D8") (pinfunction "D8_D8") (pintype "bidirectional"))
      (node (ref "J15") (pin "E7") (pinfunction "E7_E7") (pintype "bidirectional"))
      (node (ref "J15") (pin "E8") (pinfunction "E8_E8") (pintype "bidirectional"))
      (node (ref "J15") (pin "F7") (pinfunction "F7_F7") (pintype "bidirectional"))
      (node (ref "J15") (pin "F8") (pinfunction "F8_F8") (pintype "bidirectional"))
      (node (ref "J15") (pin "G7") (pinfunction "G7_G7") (pintype "bidirectional"))
      (node (ref "J15") (pin "G8") (pinfunction "G8_G8") (pintype "bidirectional"))
      (node (ref "J15") (pin "GND0") (pinfunction "GND0_GND0") (pintype "power_in"))
      (node (ref "J15") (pin "GND1") (pinfunction "GND1_GND1") (pintype "power_in"))
      (node (ref "J15") (pin "GND2") (pinfunction "GND2_GND2") (pintype "power_in"))
      (node (ref "J15") (pin "GND3") (pinfunction "GND3_GND3") (pintype "power_in"))
      (node (ref "J15") (pin "GND4") (pinfunction "GND4_GND4") (pintype "power_in"))
      (node (ref "J15") (pin "GND5") (pinfunction "GND5_GND5") (pintype "power_in"))
      (node (ref "J15") (pin "H7") (pinfunction "H7_H7") (pintype "bidirectional"))
      (node (ref "J15") (pin "H8") (pinfunction "H8_H8") (pintype "bidirectional"))
      (node (ref "J2") (pin "4") (pinfunction "4_4") (pintype "passive"))
      (node (ref "J4") (pin "A7") (pinfunction "A7_A7") (pintype "bidirectional"))
      (node (ref "J4") (pin "A8") (pinfunction "A8_A8") (pintype "bidirectional"))
      (node (ref "J4") (pin "B7") (pinfunction "B7_B7") (pintype "bidirectional"))
      (node (ref "J4") (pin "B8") (pinfunction "B8_B8") (pintype "bidirectional"))
      (node (ref "J4") (pin "C7") (pinfunction "C7_C7") (pintype "bidirectional"))
      (node (ref "J4") (pin "C8") (pinfunction "C8_C8") (pintype "bidirectional"))
      (node (ref "J4") (pin "D7") (pinfunction "D7_D7") (pintype "bidirectional"))
      (node (ref "J4") (pin "D8") (pinfunction "D8_D8") (pintype "bidirectional"))
      (node (ref "J4") (pin "E7") (pinfunction "E7_E7") (pintype "bidirectional"))
      (node (ref "J4") (pin "E8") (pinfunction "E8_E8") (pintype "bidirectional"))
      (node (ref "J4") (pin "F7") (pinfunction "F7_F7") (pintype "bidirectional"))
      (node (ref "J4") (pin "F8") (pinfunction "F8_F8") (pintype "bidirectional"))
      (node (ref "J4") (pin "G7") (pinfunction "G7_G7") (pintype "bidirectional"))
      (node (ref "J4") (pin "G8") (pinfunction "G8_G8") (pintype "bidirectional"))
      (node (ref "J4") (pin "GND0") (pinfunction "GND0_GND0") (pintype "power_in"))
      (node (ref "J4") (pin "GND1") (pinfunction "GND1_GND1") (pintype "power_in"))
      (node (ref "J4") (pin "GND2") (pinfunction "GND2_GND2") (pintype "power_in"))
      (node (ref "J4") (pin "GND3") (pinfunction "GND3_GND3") (pintype "power_in"))
      (node (ref "J4") (pin "GND4") (pinfunction "GND4_GND4") (pintype "power_in"))
      (node (ref "J4") (pin "GND5") (pinfunction "GND5_GND5") (pintype "power_in"))
      (node (ref "J4") (pin "H7") (pinfunction "H7_H7") (pintype "bidirectional"))
      (node (ref "J4") (pin "H8") (pinfunction "H8_H8") (pintype "bidirectional"))
      (node (ref "J5") (pin "A7") (pinfunction "A7_A7") (pintype "bidirectional"))
      (node (ref "J5") (pin "A8") (pinfunction "A8_A8") (pintype "bidirectional"))
      (node (ref "J5") (pin "B7") (pinfunction "B7_B7") (pintype "bidirectional"))
      (node (ref "J5") (pin "B8") (pinfunction "B8_B8") (pintype "bidirectional"))
      (node (ref "J5") (pin "C7") (pinfunction "C7_C7") (pintype "bidirectional"))
      (node (ref "J5") (pin "C8") (pinfunction "C8_C8") (pintype "bidirectional"))
      (node (ref "J5") (pin "D7") (pinfunction "D7_D7") (pintype "bidirectional"))
      (node (ref "J5") (pin "D8") (pinfunction "D8_D8") (pintype "bidirectional"))
      (node (ref "J5") (pin "E7") (pinfunction "E7_E7") (pintype "bidirectional"))
      (node (ref "J5") (pin "E8") (pinfunction "E8_E8") (pintype "bidirectional"))
      (node (ref "J5") (pin "F7") (pinfunction "F7_F7") (pintype "bidirectional"))
      (node (ref "J5") (pin "F8") (pinfunction "F8_F8") (pintype "bidirectional"))
      (node (ref "J5") (pin "G7") (pinfunction "G7_G7") (pintype "bidirectional"))
      (node (ref "J5") (pin "G8") (pinfunction "G8_G8") (pintype "bidirectional"))
      (node (ref "J5") (pin "GND0") (pinfunction "GND0_GND0") (pintype "power_in"))
      (node (ref "J5") (pin "GND1") (pinfunction "GND1_GND1") (pintype "power_in"))
      (node (ref "J5") (pin "GND2") (pinfunction "GND2_GND2") (pintype "power_in"))
      (node (ref "J5") (pin "GND3") (pinfunction "GND3_GND3") (pintype "power_in"))
      (node (ref "J5") (pin "GND4") (pinfunction "GND4_GND4") (pintype "power_in"))
      (node (ref "J5") (pin "GND5") (pinfunction "GND5_GND5") (pintype "power_in"))
      (node (ref "J5") (pin "H7") (pinfunction "H7_H7") (pintype "bidirectional"))
      (node (ref "J5") (pin "H8") (pinfunction "H8_H8") (pintype "bidirectional"))
      (node (ref "J6") (pin "A7") (pinfunction "A7_A7") (pintype "bidirectional"))
      (node (ref "J6") (pin "A8") (pinfunction "A8_A8") (pintype "bidirectional"))
      (node (ref "J6") (pin "B7") (pinfunction "B7_B7") (pintype "bidirectional"))
      (node (ref "J6") (pin "B8") (pinfunction "B8_B8") (pintype "bidirectional"))
      (node (ref "J6") (pin "C7") (pinfunction "C7_C7") (pintype "bidirectional"))
      (node (ref "J6") (pin "C8") (pinfunction "C8_C8") (pintype "bidirectional"))
      (node (ref "J6") (pin "D7") (pinfunction "D7_D7") (pintype "bidirectional"))
      (node (ref "J6") (pin "D8") (pinfunction "D8_D8") (pintype "bidirectional"))
      (node (ref "J6") (pin "E7") (pinfunction "E7_E7") (pintype "bidirectional"))
      (node (ref "J6") (pin "E8") (pinfunction "E8_E8") (pintype "bidirectional"))
      (node (ref "J6") (pin "F7") (pinfunction "F7_F7") (pintype "bidirectional"))
      (node (ref "J6") (pin "F8") (pinfunction "F8_F8") (pintype "bidirectional"))
      (node (ref "J6") (pin "G7") (pinfunction "G7_G7") (pintype "bidirectional"))
      (node (ref "J6") (pin "G8") (pinfunction "G8_G8") (pintype "bidirectional"))
      (node (ref "J6") (pin "GND0") (pinfunction "GND0_GND0") (pintype "power_in"))
      (node (ref "J6") (pin "GND1") (pinfunction "GND1_GND1") (pintype "power_in"))
      (node (ref "J6") (pin "GND2") (pinfunction "GND2_GND2") (pintype "power_in"))
      (node (ref "J6") (pin "GND3") (pinfunction "GND3_GND3") (pintype "power_in"))
      (node (ref "J6") (pin "GND4") (pinfunction "GND4_GND4") (pintype "power_in"))
      (node (ref "J6") (pin "GND5") (pinfunction "GND5_GND5") (pintype "power_in"))
      (node (ref "J6") (pin "H7") (pinfunction "H7_H7") (pintype "bidirectional"))
      (node (ref "J6") (pin "H8") (pinfunction "H8_H8") (pintype "bidirectional"))
      (node (ref "LED1") (pin "C") (pinfunction "C_C") (pintype "passive"))
      (node (ref "LED2") (pin "C") (pinfunction "C_C") (pintype "passive"))
      (node (ref "RN49") (pin "1") (pinfunction "1_1") (pintype "passive"))
      (node (ref "RN49") (pin "2") (pinfunction "1_2") (pintype "passive"))
      (node (ref "RN49") (pin "3") (pinfunction "1_3") (pintype "passive"))
      (node (ref "RN49") (pin "4") (pinfunction "1_4") (pintype "passive"))
      (node (ref "RN50") (pin "1") (pinfunction "1_1") (pintype "passive"))
      (node (ref "RN50") (pin "2") (pinfunction "1_2") (pintype "passive"))
      (node (ref "RN50") (pin "3") (pinfunction "1_3") (pintype "passive"))
      (node (ref "RN50") (pin "4") (pinfunction "1_4") (pintype "passive"))
      (node (ref "RN51") (pin "1") (pinfunction "1_1") (pintype "passive"))
      (node (ref "RN51") (pin "2") (pinfunction "1_2") (pintype "passive"))
      (node (ref "RN51") (pin "3") (pinfunction "1_3") (pintype "passive"))
      (node (ref "RN51") (pin "4") (pinfunction "1_4") (pintype "passive"))
      (node (ref "RN52") (pin "1") (pinfunction "1_1") (pintype "passive"))
      (node (ref "RN52") (pin "2") (pinfunction "1_2") (pintype "passive"))
      (node (ref "RN52") (pin "3") (pinfunction "1_3") (pintype "passive"))
      (node (ref "RN52") (pin "4") (pinfunction "1_4") (pintype "passive"))
      (node (ref "RN53") (pin "1") (pinfunction "1_1") (pintype "passive"))
      (node (ref "RN53") (pin "2") (pinfunction "1_2") (pintype "passive"))
      (node (ref "RN53") (pin "3") (pinfunction "1_3") (pintype "passive"))
      (node (ref "RN53") (pin "4") (pinfunction "1_4") (pintype "passive"))
      (node (ref "RN54") (pin "1") (pinfunction "1_1") (pintype "passive"))
      (node (ref "RN54") (pin "2") (pinfunction "1_2") (pintype "passive"))
      (node (ref "RN54") (pin "3") (pinfunction "1_3") (pintype "passive"))
      (node (ref "RN54") (pin "4") (pinfunction "1_4") (pintype "passive"))
      (node (ref "RN63") (pin "1") (pinfunction "1_1") (pintype "passive"))
      (node (ref "RN63") (pin "2") (pinfunction "1_2") (pintype "passive"))
      (node (ref "RN63") (pin "3") (pinfunction "1_3") (pintype "passive"))
      (node (ref "RN63") (pin "4") (pinfunction "1_4") (pintype "passive"))
      (node (ref "RN72") (pin "1") (pinfunction "1_1") (pintype "passive"))
      (node (ref "RN72") (pin "2") (pinfunction "1_2") (pintype "passive"))
      (node (ref "RN72") (pin "3") (pinfunction "1_3") (pintype "passive"))
      (node (ref "RN72") (pin "4") (pinfunction "1_4") (pintype "passive"))
    )
    (net (code "130") (name "GPA0-1") (class "Default")
      (node (ref "IC1") (pin "21") (pinfunction "GPA0_21") (pintype "bidirectional"))
      (node (ref "RN1") (pin "4") (pinfunction "1_4") (pintype "passive"))
    )
    (net (code "131") (name "GPA0-2") (class "Default")
      (node (ref "IC2") (pin "21") (pinfunction "GPA0_21") (pintype "bidirectional"))
      (node (ref "RN9") (pin "4") (pinfunction "1_4") (pintype "passive"))
    )
    (net (code "132") (name "GPA0-3") (class "Default")
      (node (ref "IC3") (pin "21") (pinfunction "GPA0_21") (pintype "bidirectional"))
      (node (ref "RN17") (pin "4") (pinfunction "1_4") (pintype "passive"))
    )
    (net (code "133") (name "GPA0-4") (class "Default")
      (node (ref "IC4") (pin "21") (pinfunction "GPA0_21") (pintype "bidirectional"))
      (node (ref "RN25") (pin "4") (pinfunction "1_4") (pintype "passive"))
    )
    (net (code "134") (name "GPA0-5") (class "Default")
      (node (ref "IC5") (pin "21") (pinfunction "GPA0_21") (pintype "bidirectional"))
      (node (ref "RN33") (pin "4") (pinfunction "1_4") (pintype "passive"))
    )
    (net (code "135") (name "GPA0-6") (class "Default")
      (node (ref "IC6") (pin "21") (pinfunction "GPA0_21") (pintype "bidirectional"))
      (node (ref "RN37") (pin "4") (pinfunction "1_4") (pintype "passive"))
    )
    (net (code "136") (name "GPA0-7") (class "Default")
      (node (ref "IC7") (pin "21") (pinfunction "GPA0_21") (pintype "bidirectional"))
      (node (ref "RN55") (pin "4") (pinfunction "1_4") (pintype "passive"))
    )
    (net (code "137") (name "GPA0-8") (class "Default")
      (node (ref "IC8") (pin "21") (pinfunction "GPA0_21") (pintype "bidirectional"))
      (node (ref "RN64") (pin "4") (pinfunction "1_4") (pintype "passive"))
    )
    (net (code "138") (name "GPA1-1") (class "Default")
      (node (ref "IC1") (pin "22") (pinfunction "GPA1_22") (pintype "bidirectional"))
      (node (ref "RN1") (pin "3") (pinfunction "1_3") (pintype "passive"))
    )
    (net (code "139") (name "GPA1-2") (class "Default")
      (node (ref "IC2") (pin "22") (pinfunction "GPA1_22") (pintype "bidirectional"))
      (node (ref "RN9") (pin "3") (pinfunction "1_3") (pintype "passive"))
    )
    (net (code "140") (name "GPA1-3") (class "Default")
      (node (ref "IC3") (pin "22") (pinfunction "GPA1_22") (pintype "bidirectional"))
      (node (ref "RN17") (pin "3") (pinfunction "1_3") (pintype "passive"))
    )
    (net (code "141") (name "GPA1-4") (class "Default")
      (node (ref "IC4") (pin "22") (pinfunction "GPA1_22") (pintype "bidirectional"))
      (node (ref "RN25") (pin "3") (pinfunction "1_3") (pintype "passive"))
    )
    (net (code "142") (name "GPA1-5") (class "Default")
      (node (ref "IC5") (pin "22") (pinfunction "GPA1_22") (pintype "bidirectional"))
      (node (ref "RN33") (pin "3") (pinfunction "1_3") (pintype "passive"))
    )
    (net (code "143") (name "GPA1-6") (class "Default")
      (node (ref "IC6") (pin "22") (pinfunction "GPA1_22") (pintype "bidirectional"))
      (node (ref "RN37") (pin "3") (pinfunction "1_3") (pintype "passive"))
    )
    (net (code "144") (name "GPA1-7") (class "Default")
      (node (ref "IC7") (pin "22") (pinfunction "GPA1_22") (pintype "bidirectional"))
      (node (ref "RN55") (pin "3") (pinfunction "1_3") (pintype "passive"))
    )
    (net (code "145") (name "GPA1-8") (class "Default")
      (node (ref "IC8") (pin "22") (pinfunction "GPA1_22") (pintype "bidirectional"))
      (node (ref "RN64") (pin "3") (pinfunction "1_3") (pintype "passive"))
    )
    (net (code "146") (name "GPA2-1") (class "Default")
      (node (ref "IC1") (pin "23") (pinfunction "GPA2_23") (pintype "bidirectional"))
      (node (ref "RN1") (pin "2") (pinfunction "1_2") (pintype "passive"))
    )
    (net (code "147") (name "GPA2-2") (class "Default")
      (node (ref "IC2") (pin "23") (pinfunction "GPA2_23") (pintype "bidirectional"))
      (node (ref "RN9") (pin "2") (pinfunction "1_2") (pintype "passive"))
    )
    (net (code "148") (name "GPA2-3") (class "Default")
      (node (ref "IC3") (pin "23") (pinfunction "GPA2_23") (pintype "bidirectional"))
      (node (ref "RN17") (pin "2") (pinfunction "1_2") (pintype "passive"))
    )
    (net (code "149") (name "GPA2-4") (class "Default")
      (node (ref "IC4") (pin "23") (pinfunction "GPA2_23") (pintype "bidirectional"))
      (node (ref "RN25") (pin "2") (pinfunction "1_2") (pintype "passive"))
    )
    (net (code "150") (name "GPA2-5") (class "Default")
      (node (ref "IC5") (pin "23") (pinfunction "GPA2_23") (pintype "bidirectional"))
      (node (ref "RN33") (pin "2") (pinfunction "1_2") (pintype "passive"))
    )
    (net (code "151") (name "GPA2-6") (class "Default")
      (node (ref "IC6") (pin "23") (pinfunction "GPA2_23") (pintype "bidirectional"))
      (node (ref "RN37") (pin "2") (pinfunction "1_2") (pintype "passive"))
    )
    (net (code "152") (name "GPA2-7") (class "Default")
      (node (ref "IC7") (pin "23") (pinfunction "GPA2_23") (pintype "bidirectional"))
      (node (ref "RN55") (pin "2") (pinfunction "1_2") (pintype "passive"))
    )
    (net (code "153") (name "GPA2-8") (class "Default")
      (node (ref "IC8") (pin "23") (pinfunction "GPA2_23") (pintype "bidirectional"))
      (node (ref "RN64") (pin "2") (pinfunction "1_2") (pintype "passive"))
    )
    (net (code "154") (name "GPA3-1") (class "Default")
      (node (ref "IC1") (pin "24") (pinfunction "GPA3_24") (pintype "bidirectional"))
      (node (ref "RN1") (pin "1") (pinfunction "1_1") (pintype "passive"))
    )
    (net (code "155") (name "GPA3-2") (class "Default")
      (node (ref "IC2") (pin "24") (pinfunction "GPA3_24") (pintype "bidirectional"))
      (node (ref "RN9") (pin "1") (pinfunction "1_1") (pintype "passive"))
    )
    (net (code "156") (name "GPA3-3") (class "Default")
      (node (ref "IC3") (pin "24") (pinfunction "GPA3_24") (pintype "bidirectional"))
      (node (ref "RN17") (pin "1") (pinfunction "1_1") (pintype "passive"))
    )
    (net (code "157") (name "GPA3-4") (class "Default")
      (node (ref "IC4") (pin "24") (pinfunction "GPA3_24") (pintype "bidirectional"))
      (node (ref "RN25") (pin "1") (pinfunction "1_1") (pintype "passive"))
    )
    (net (code "158") (name "GPA3-5") (class "Default")
      (node (ref "IC5") (pin "24") (pinfunction "GPA3_24") (pintype "bidirectional"))
      (node (ref "RN33") (pin "1") (pinfunction "1_1") (pintype "passive"))
    )
    (net (code "159") (name "GPA3-6") (class "Default")
      (node (ref "IC6") (pin "24") (pinfunction "GPA3_24") (pintype "bidirectional"))
      (node (ref "RN37") (pin "1") (pinfunction "1_1") (pintype "passive"))
    )
    (net (code "160") (name "GPA3-7") (class "Default")
      (node (ref "IC7") (pin "24") (pinfunction "GPA3_24") (pintype "bidirectional"))
      (node (ref "RN55") (pin "1") (pinfunction "1_1") (pintype "passive"))
    )
    (net (code "161") (name "GPA3-8") (class "Default")
      (node (ref "IC8") (pin "24") (pinfunction "GPA3_24") (pintype "bidirectional"))
      (node (ref "RN64") (pin "1") (pinfunction "1_1") (pintype "passive"))
    )
    (net (code "162") (name "GPA4-1") (class "Default")
      (node (ref "IC1") (pin "25") (pinfunction "GPA4_25") (pintype "bidirectional"))
      (node (ref "RN2") (pin "4") (pinfunction "1_4") (pintype "passive"))
    )
    (net (code "163") (name "GPA4-2") (class "Default")
      (node (ref "IC2") (pin "25") (pinfunction "GPA4_25") (pintype "bidirectional"))
      (node (ref "RN10") (pin "4") (pinfunction "1_4") (pintype "passive"))
    )
    (net (code "164") (name "GPA4-3") (class "Default")
      (node (ref "IC3") (pin "25") (pinfunction "GPA4_25") (pintype "bidirectional"))
      (node (ref "RN18") (pin "4") (pinfunction "1_4") (pintype "passive"))
    )
    (net (code "165") (name "GPA4-4") (class "Default")
      (node (ref "IC4") (pin "25") (pinfunction "GPA4_25") (pintype "bidirectional"))
      (node (ref "RN26") (pin "4") (pinfunction "1_4") (pintype "passive"))
    )
    (net (code "166") (name "GPA4-5") (class "Default")
      (node (ref "IC5") (pin "25") (pinfunction "GPA4_25") (pintype "bidirectional"))
      (node (ref "RN34") (pin "4") (pinfunction "1_4") (pintype "passive"))
    )
    (net (code "167") (name "GPA4-6") (class "Default")
      (node (ref "IC6") (pin "25") (pinfunction "GPA4_25") (pintype "bidirectional"))
      (node (ref "RN38") (pin "4") (pinfunction "1_4") (pintype "passive"))
    )
    (net (code "168") (name "GPA4-7") (class "Default")
      (node (ref "IC7") (pin "25") (pinfunction "GPA4_25") (pintype "bidirectional"))
      (node (ref "RN56") (pin "4") (pinfunction "1_4") (pintype "passive"))
    )
    (net (code "169") (name "GPA4-8") (class "Default")
      (node (ref "IC8") (pin "25") (pinfunction "GPA4_25") (pintype "bidirectional"))
      (node (ref "RN65") (pin "4") (pinfunction "1_4") (pintype "passive"))
    )
    (net (code "170") (name "GPA5-1") (class "Default")
      (node (ref "IC1") (pin "26") (pinfunction "GPA5_26") (pintype "bidirectional"))
      (node (ref "RN2") (pin "3") (pinfunction "1_3") (pintype "passive"))
    )
    (net (code "171") (name "GPA5-2") (class "Default")
      (node (ref "IC2") (pin "26") (pinfunction "GPA5_26") (pintype "bidirectional"))
      (node (ref "RN10") (pin "3") (pinfunction "1_3") (pintype "passive"))
    )
    (net (code "172") (name "GPA5-3") (class "Default")
      (node (ref "IC3") (pin "26") (pinfunction "GPA5_26") (pintype "bidirectional"))
      (node (ref "RN18") (pin "3") (pinfunction "1_3") (pintype "passive"))
    )
    (net (code "173") (name "GPA5-4") (class "Default")
      (node (ref "IC4") (pin "26") (pinfunction "GPA5_26") (pintype "bidirectional"))
      (node (ref "RN26") (pin "3") (pinfunction "1_3") (pintype "passive"))
    )
    (net (code "174") (name "GPA5-5") (class "Default")
      (node (ref "IC5") (pin "26") (pinfunction "GPA5_26") (pintype "bidirectional"))
      (node (ref "RN34") (pin "3") (pinfunction "1_3") (pintype "passive"))
    )
    (net (code "175") (name "GPA5-6") (class "Default")
      (node (ref "IC6") (pin "26") (pinfunction "GPA5_26") (pintype "bidirectional"))
      (node (ref "RN38") (pin "3") (pinfunction "1_3") (pintype "passive"))
    )
    (net (code "176") (name "GPA5-7") (class "Default")
      (node (ref "IC7") (pin "26") (pinfunction "GPA5_26") (pintype "bidirectional"))
      (node (ref "RN56") (pin "3") (pinfunction "1_3") (pintype "passive"))
    )
    (net (code "177") (name "GPA5-8") (class "Default")
      (node (ref "IC8") (pin "26") (pinfunction "GPA5_26") (pintype "bidirectional"))
      (node (ref "RN65") (pin "3") (pinfunction "1_3") (pintype "passive"))
    )
    (net (code "178") (name "GPA6-1") (class "Default")
      (node (ref "IC1") (pin "27") (pinfunction "GPA6_27") (pintype "bidirectional"))
      (node (ref "RN2") (pin "2") (pinfunction "1_2") (pintype "passive"))
    )
    (net (code "179") (name "GPA6-2") (class "Default")
      (node (ref "IC2") (pin "27") (pinfunction "GPA6_27") (pintype "bidirectional"))
      (node (ref "RN10") (pin "2") (pinfunction "1_2") (pintype "passive"))
    )
    (net (code "180") (name "GPA6-3") (class "Default")
      (node (ref "IC3") (pin "27") (pinfunction "GPA6_27") (pintype "bidirectional"))
      (node (ref "RN18") (pin "2") (pinfunction "1_2") (pintype "passive"))
    )
    (net (code "181") (name "GPA6-4") (class "Default")
      (node (ref "IC4") (pin "27") (pinfunction "GPA6_27") (pintype "bidirectional"))
      (node (ref "RN26") (pin "2") (pinfunction "1_2") (pintype "passive"))
    )
    (net (code "182") (name "GPA6-5") (class "Default")
      (node (ref "IC5") (pin "27") (pinfunction "GPA6_27") (pintype "bidirectional"))
      (node (ref "RN34") (pin "2") (pinfunction "1_2") (pintype "passive"))
    )
    (net (code "183") (name "GPA6-6") (class "Default")
      (node (ref "IC6") (pin "27") (pinfunction "GPA6_27") (pintype "bidirectional"))
      (node (ref "RN38") (pin "2") (pinfunction "1_2") (pintype "passive"))
    )
    (net (code "184") (name "GPA6-7") (class "Default")
      (node (ref "IC7") (pin "27") (pinfunction "GPA6_27") (pintype "bidirectional"))
      (node (ref "RN56") (pin "2") (pinfunction "1_2") (pintype "passive"))
    )
    (net (code "185") (name "GPA6-8") (class "Default")
      (node (ref "IC8") (pin "27") (pinfunction "GPA6_27") (pintype "bidirectional"))
      (node (ref "RN65") (pin "2") (pinfunction "1_2") (pintype "passive"))
    )
    (net (code "186") (name "GPA7-1") (class "Default")
      (node (ref "IC1") (pin "28") (pinfunction "GPA7_28") (pintype "bidirectional"))
      (node (ref "RN2") (pin "1") (pinfunction "1_1") (pintype "passive"))
    )
    (net (code "187") (name "GPA7-2") (class "Default")
      (node (ref "IC2") (pin "28") (pinfunction "GPA7_28") (pintype "bidirectional"))
      (node (ref "RN10") (pin "1") (pinfunction "1_1") (pintype "passive"))
    )
    (net (code "188") (name "GPA7-3") (class "Default")
      (node (ref "IC3") (pin "28") (pinfunction "GPA7_28") (pintype "bidirectional"))
      (node (ref "RN18") (pin "1") (pinfunction "1_1") (pintype "passive"))
    )
    (net (code "189") (name "GPA7-4") (class "Default")
      (node (ref "IC4") (pin "28") (pinfunction "GPA7_28") (pintype "bidirectional"))
      (node (ref "RN26") (pin "1") (pinfunction "1_1") (pintype "passive"))
    )
    (net (code "190") (name "GPA7-5") (class "Default")
      (node (ref "IC5") (pin "28") (pinfunction "GPA7_28") (pintype "bidirectional"))
      (node (ref "RN34") (pin "1") (pinfunction "1_1") (pintype "passive"))
    )
    (net (code "191") (name "GPA7-6") (class "Default")
      (node (ref "IC6") (pin "28") (pinfunction "GPA7_28") (pintype "bidirectional"))
      (node (ref "RN38") (pin "1") (pinfunction "1_1") (pintype "passive"))
    )
    (net (code "192") (name "GPA7-7") (class "Default")
      (node (ref "IC7") (pin "28") (pinfunction "GPA7_28") (pintype "bidirectional"))
      (node (ref "RN56") (pin "1") (pinfunction "1_1") (pintype "passive"))
    )
    (net (code "193") (name "GPA7-8") (class "Default")
      (node (ref "IC8") (pin "28") (pinfunction "GPA7_28") (pintype "bidirectional"))
      (node (ref "RN65") (pin "1") (pinfunction "1_1") (pintype "passive"))
    )
    (net (code "194") (name "GPB0-1") (class "Default")
      (node (ref "IC1") (pin "1") (pinfunction "GPB0_1") (pintype "bidirectional"))
      (node (ref "RN3") (pin "4") (pinfunction "1_4") (pintype "passive"))
    )
    (net (code "195") (name "GPB0-2") (class "Default")
      (node (ref "IC2") (pin "1") (pinfunction "GPB0_1") (pintype "bidirectional"))
      (node (ref "RN11") (pin "4") (pinfunction "1_4") (pintype "passive"))
    )
    (net (code "196") (name "GPB0-3") (class "Default")
      (node (ref "IC3") (pin "1") (pinfunction "GPB0_1") (pintype "bidirectional"))
      (node (ref "RN19") (pin "4") (pinfunction "1_4") (pintype "passive"))
    )
    (net (code "197") (name "GPB0-4") (class "Default")
      (node (ref "IC4") (pin "1") (pinfunction "GPB0_1") (pintype "bidirectional"))
      (node (ref "RN27") (pin "4") (pinfunction "1_4") (pintype "passive"))
    )
    (net (code "198") (name "GPB0-5") (class "Default")
      (node (ref "IC5") (pin "1") (pinfunction "GPB0_1") (pintype "bidirectional"))
      (node (ref "RN35") (pin "4") (pinfunction "1_4") (pintype "passive"))
    )
    (net (code "199") (name "GPB0-6") (class "Default")
      (node (ref "IC6") (pin "1") (pinfunction "GPB0_1") (pintype "bidirectional"))
      (node (ref "RN39") (pin "4") (pinfunction "1_4") (pintype "passive"))
    )
    (net (code "200") (name "GPB0-7") (class "Default")
      (node (ref "IC7") (pin "1") (pinfunction "GPB0_1") (pintype "bidirectional"))
      (node (ref "RN57") (pin "4") (pinfunction "1_4") (pintype "passive"))
    )
    (net (code "201") (name "GPB0-8") (class "Default")
      (node (ref "IC8") (pin "1") (pinfunction "GPB0_1") (pintype "bidirectional"))
      (node (ref "RN66") (pin "4") (pinfunction "1_4") (pintype "passive"))
    )
    (net (code "202") (name "GPB1-1") (class "Default")
      (node (ref "IC1") (pin "2") (pinfunction "GPB1_2") (pintype "bidirectional"))
      (node (ref "RN3") (pin "3") (pinfunction "1_3") (pintype "passive"))
    )
    (net (code "203") (name "GPB1-2") (class "Default")
      (node (ref "IC2") (pin "2") (pinfunction "GPB1_2") (pintype "bidirectional"))
      (node (ref "RN11") (pin "3") (pinfunction "1_3") (pintype "passive"))
    )
    (net (code "204") (name "GPB1-3") (class "Default")
      (node (ref "IC3") (pin "2") (pinfunction "GPB1_2") (pintype "bidirectional"))
      (node (ref "RN19") (pin "3") (pinfunction "1_3") (pintype "passive"))
    )
    (net (code "205") (name "GPB1-4") (class "Default")
      (node (ref "IC4") (pin "2") (pinfunction "GPB1_2") (pintype "bidirectional"))
      (node (ref "RN27") (pin "3") (pinfunction "1_3") (pintype "passive"))
    )
    (net (code "206") (name "GPB1-5") (class "Default")
      (node (ref "IC5") (pin "2") (pinfunction "GPB1_2") (pintype "bidirectional"))
      (node (ref "RN35") (pin "3") (pinfunction "1_3") (pintype "passive"))
    )
    (net (code "207") (name "GPB1-6") (class "Default")
      (node (ref "IC6") (pin "2") (pinfunction "GPB1_2") (pintype "bidirectional"))
      (node (ref "RN39") (pin "3") (pinfunction "1_3") (pintype "passive"))
    )
    (net (code "208") (name "GPB1-7") (class "Default")
      (node (ref "IC7") (pin "2") (pinfunction "GPB1_2") (pintype "bidirectional"))
      (node (ref "RN57") (pin "3") (pinfunction "1_3") (pintype "passive"))
    )
    (net (code "209") (name "GPB1-8") (class "Default")
      (node (ref "IC8") (pin "2") (pinfunction "GPB1_2") (pintype "bidirectional"))
      (node (ref "RN66") (pin "3") (pinfunction "1_3") (pintype "passive"))
    )
    (net (code "210") (name "GPB2-1") (class "Default")
      (node (ref "IC1") (pin "3") (pinfunction "GPB2_3") (pintype "bidirectional"))
      (node (ref "RN3") (pin "2") (pinfunction "1_2") (pintype "passive"))
    )
    (net (code "211") (name "GPB2-2") (class "Default")
      (node (ref "IC2") (pin "3") (pinfunction "GPB2_3") (pintype "bidirectional"))
      (node (ref "RN11") (pin "2") (pinfunction "1_2") (pintype "passive"))
    )
    (net (code "212") (name "GPB2-3") (class "Default")
      (node (ref "IC3") (pin "3") (pinfunction "GPB2_3") (pintype "bidirectional"))
      (node (ref "RN19") (pin "2") (pinfunction "1_2") (pintype "passive"))
    )
    (net (code "213") (name "GPB2-4") (class "Default")
      (node (ref "IC4") (pin "3") (pinfunction "GPB2_3") (pintype "bidirectional"))
      (node (ref "RN27") (pin "2") (pinfunction "1_2") (pintype "passive"))
    )
    (net (code "214") (name "GPB2-5") (class "Default")
      (node (ref "IC5") (pin "3") (pinfunction "GPB2_3") (pintype "bidirectional"))
      (node (ref "RN35") (pin "2") (pinfunction "1_2") (pintype "passive"))
    )
    (net (code "215") (name "GPB2-6") (class "Default")
      (node (ref "IC6") (pin "3") (pinfunction "GPB2_3") (pintype "bidirectional"))
      (node (ref "RN39") (pin "2") (pinfunction "1_2") (pintype "passive"))
    )
    (net (code "216") (name "GPB2-7") (class "Default")
      (node (ref "IC7") (pin "3") (pinfunction "GPB2_3") (pintype "bidirectional"))
      (node (ref "RN57") (pin "2") (pinfunction "1_2") (pintype "passive"))
    )
    (net (code "217") (name "GPB2-8") (class "Default")
      (node (ref "IC8") (pin "3") (pinfunction "GPB2_3") (pintype "bidirectional"))
      (node (ref "RN66") (pin "2") (pinfunction "1_2") (pintype "passive"))
    )
    (net (code "218") (name "GPB3-1") (class "Default")
      (node (ref "IC1") (pin "4") (pinfunction "GPB3_4") (pintype "bidirectional"))
      (node (ref "RN3") (pin "1") (pinfunction "1_1") (pintype "passive"))
    )
    (net (code "219") (name "GPB3-2") (class "Default")
      (node (ref "IC2") (pin "4") (pinfunction "GPB3_4") (pintype "bidirectional"))
      (node (ref "RN11") (pin "1") (pinfunction "1_1") (pintype "passive"))
    )
    (net (code "220") (name "GPB3-3") (class "Default")
      (node (ref "IC3") (pin "4") (pinfunction "GPB3_4") (pintype "bidirectional"))
      (node (ref "RN19") (pin "1") (pinfunction "1_1") (pintype "passive"))
    )
    (net (code "221") (name "GPB3-4") (class "Default")
      (node (ref "IC4") (pin "4") (pinfunction "GPB3_4") (pintype "bidirectional"))
      (node (ref "RN27") (pin "1") (pinfunction "1_1") (pintype "passive"))
    )
    (net (code "222") (name "GPB3-5") (class "Default")
      (node (ref "IC5") (pin "4") (pinfunction "GPB3_4") (pintype "bidirectional"))
      (node (ref "RN35") (pin "1") (pinfunction "1_1") (pintype "passive"))
    )
    (net (code "223") (name "GPB3-6") (class "Default")
      (node (ref "IC6") (pin "4") (pinfunction "GPB3_4") (pintype "bidirectional"))
      (node (ref "RN39") (pin "1") (pinfunction "1_1") (pintype "passive"))
    )
    (net (code "224") (name "GPB3-7") (class "Default")
      (node (ref "IC7") (pin "4") (pinfunction "GPB3_4") (pintype "bidirectional"))
      (node (ref "RN57") (pin "1") (pinfunction "1_1") (pintype "passive"))
    )
    (net (code "225") (name "GPB3-8") (class "Default")
      (node (ref "IC8") (pin "4") (pinfunction "GPB3_4") (pintype "bidirectional"))
      (node (ref "RN66") (pin "1") (pinfunction "1_1") (pintype "passive"))
    )
    (net (code "226") (name "GPB4-1") (class "Default")
      (node (ref "IC1") (pin "5") (pinfunction "GPB4_5") (pintype "bidirectional"))
      (node (ref "RN4") (pin "4") (pinfunction "1_4") (pintype "passive"))
    )
    (net (code "227") (name "GPB4-2") (class "Default")
      (node (ref "IC2") (pin "5") (pinfunction "GPB4_5") (pintype "bidirectional"))
      (node (ref "RN12") (pin "4") (pinfunction "1_4") (pintype "passive"))
    )
    (net (code "228") (name "GPB4-3") (class "Default")
      (node (ref "IC3") (pin "5") (pinfunction "GPB4_5") (pintype "bidirectional"))
      (node (ref "RN20") (pin "4") (pinfunction "1_4") (pintype "passive"))
    )
    (net (code "229") (name "GPB4-4") (class "Default")
      (node (ref "IC4") (pin "5") (pinfunction "GPB4_5") (pintype "bidirectional"))
      (node (ref "RN28") (pin "4") (pinfunction "1_4") (pintype "passive"))
    )
    (net (code "230") (name "GPB4-5") (class "Default")
      (node (ref "IC5") (pin "5") (pinfunction "GPB4_5") (pintype "bidirectional"))
      (node (ref "RN36") (pin "4") (pinfunction "1_4") (pintype "passive"))
    )
    (net (code "231") (name "GPB4-6") (class "Default")
      (node (ref "IC6") (pin "5") (pinfunction "GPB4_5") (pintype "bidirectional"))
      (node (ref "RN40") (pin "4") (pinfunction "1_4") (pintype "passive"))
    )
    (net (code "232") (name "GPB4-7") (class "Default")
      (node (ref "IC7") (pin "5") (pinfunction "GPB4_5") (pintype "bidirectional"))
      (node (ref "RN58") (pin "4") (pinfunction "1_4") (pintype "passive"))
    )
    (net (code "233") (name "GPB4-8") (class "Default")
      (node (ref "IC8") (pin "5") (pinfunction "GPB4_5") (pintype "bidirectional"))
      (node (ref "RN67") (pin "4") (pinfunction "1_4") (pintype "passive"))
    )
    (net (code "234") (name "GPB5-1") (class "Default")
      (node (ref "IC1") (pin "6") (pinfunction "GPB5_6") (pintype "bidirectional"))
      (node (ref "RN4") (pin "3") (pinfunction "1_3") (pintype "passive"))
    )
    (net (code "235") (name "GPB5-2") (class "Default")
      (node (ref "IC2") (pin "6") (pinfunction "GPB5_6") (pintype "bidirectional"))
      (node (ref "RN12") (pin "3") (pinfunction "1_3") (pintype "passive"))
    )
    (net (code "236") (name "GPB5-3") (class "Default")
      (node (ref "IC3") (pin "6") (pinfunction "GPB5_6") (pintype "bidirectional"))
      (node (ref "RN20") (pin "3") (pinfunction "1_3") (pintype "passive"))
    )
    (net (code "237") (name "GPB5-4") (class "Default")
      (node (ref "IC4") (pin "6") (pinfunction "GPB5_6") (pintype "bidirectional"))
      (node (ref "RN28") (pin "3") (pinfunction "1_3") (pintype "passive"))
    )
    (net (code "238") (name "GPB5-5") (class "Default")
      (node (ref "IC5") (pin "6") (pinfunction "GPB5_6") (pintype "bidirectional"))
      (node (ref "RN36") (pin "3") (pinfunction "1_3") (pintype "passive"))
    )
    (net (code "239") (name "GPB5-6") (class "Default")
      (node (ref "IC6") (pin "6") (pinfunction "GPB5_6") (pintype "bidirectional"))
      (node (ref "RN40") (pin "3") (pinfunction "1_3") (pintype "passive"))
    )
    (net (code "240") (name "GPB5-7") (class "Default")
      (node (ref "IC7") (pin "6") (pinfunction "GPB5_6") (pintype "bidirectional"))
      (node (ref "RN58") (pin "3") (pinfunction "1_3") (pintype "passive"))
    )
    (net (code "241") (name "GPB5-8") (class "Default")
      (node (ref "IC8") (pin "6") (pinfunction "GPB5_6") (pintype "bidirectional"))
      (node (ref "RN67") (pin "3") (pinfunction "1_3") (pintype "passive"))
    )
    (net (code "242") (name "GPB6-1") (class "Default")
      (node (ref "IC1") (pin "7") (pinfunction "GPB6_7") (pintype "bidirectional"))
      (node (ref "RN4") (pin "2") (pinfunction "1_2") (pintype "passive"))
    )
    (net (code "243") (name "GPB6-2") (class "Default")
      (node (ref "IC2") (pin "7") (pinfunction "GPB6_7") (pintype "bidirectional"))
      (node (ref "RN12") (pin "2") (pinfunction "1_2") (pintype "passive"))
    )
    (net (code "244") (name "GPB6-3") (class "Default")
      (node (ref "IC3") (pin "7") (pinfunction "GPB6_7") (pintype "bidirectional"))
      (node (ref "RN20") (pin "2") (pinfunction "1_2") (pintype "passive"))
    )
    (net (code "245") (name "GPB6-4") (class "Default")
      (node (ref "IC4") (pin "7") (pinfunction "GPB6_7") (pintype "bidirectional"))
      (node (ref "RN28") (pin "2") (pinfunction "1_2") (pintype "passive"))
    )
    (net (code "246") (name "GPB6-5") (class "Default")
      (node (ref "IC5") (pin "7") (pinfunction "GPB6_7") (pintype "bidirectional"))
      (node (ref "RN36") (pin "2") (pinfunction "1_2") (pintype "passive"))
    )
    (net (code "247") (name "GPB6-6") (class "Default")
      (node (ref "IC6") (pin "7") (pinfunction "GPB6_7") (pintype "bidirectional"))
      (node (ref "RN40") (pin "2") (pinfunction "1_2") (pintype "passive"))
    )
    (net (code "248") (name "GPB6-7") (class "Default")
      (node (ref "IC7") (pin "7") (pinfunction "GPB6_7") (pintype "bidirectional"))
      (node (ref "RN58") (pin "2") (pinfunction "1_2") (pintype "passive"))
    )
    (net (code "249") (name "GPB6-8") (class "Default")
      (node (ref "IC8") (pin "7") (pinfunction "GPB6_7") (pintype "bidirectional"))
      (node (ref "RN67") (pin "2") (pinfunction "1_2") (pintype "passive"))
    )
    (net (code "250") (name "GPB7-1") (class "Default")
      (node (ref "IC1") (pin "8") (pinfunction "GPB7_8") (pintype "bidirectional"))
      (node (ref "RN4") (pin "1") (pinfunction "1_1") (pintype "passive"))
    )
    (net (code "251") (name "GPB7-2") (class "Default")
      (node (ref "IC2") (pin "8") (pinfunction "GPB7_8") (pintype "bidirectional"))
      (node (ref "RN12") (pin "1") (pinfunction "1_1") (pintype "passive"))
    )
    (net (code "252") (name "GPB7-3") (class "Default")
      (node (ref "IC3") (pin "8") (pinfunction "GPB7_8") (pintype "bidirectional"))
      (node (ref "RN20") (pin "1") (pinfunction "1_1") (pintype "passive"))
    )
    (net (code "253") (name "GPB7-4") (class "Default")
      (node (ref "IC4") (pin "8") (pinfunction "GPB7_8") (pintype "bidirectional"))
      (node (ref "RN28") (pin "1") (pinfunction "1_1") (pintype "passive"))
    )
    (net (code "254") (name "GPB7-5") (class "Default")
      (node (ref "IC5") (pin "8") (pinfunction "GPB7_8") (pintype "bidirectional"))
      (node (ref "RN36") (pin "1") (pinfunction "1_1") (pintype "passive"))
    )
    (net (code "255") (name "GPB7-6") (class "Default")
      (node (ref "IC6") (pin "8") (pinfunction "GPB7_8") (pintype "bidirectional"))
      (node (ref "RN40") (pin "1") (pinfunction "1_1") (pintype "passive"))
    )
    (net (code "256") (name "GPB7-7") (class "Default")
      (node (ref "IC7") (pin "8") (pinfunction "GPB7_8") (pintype "bidirectional"))
      (node (ref "RN58") (pin "1") (pinfunction "1_1") (pintype "passive"))
    )
    (net (code "257") (name "GPB7-8") (class "Default")
      (node (ref "IC8") (pin "8") (pinfunction "GPB7_8") (pintype "bidirectional"))
      (node (ref "RN67") (pin "1") (pinfunction "1_1") (pintype "passive"))
    )
    (net (code "258") (name "Net-(IC1-A0)") (class "Default")
      (node (ref "IC1") (pin "15") (pinfunction "A0_15") (pintype "input"))
      (node (ref "J7") (pin "2") (pinfunction "2_2") (pintype "passive"))
      (node (ref "RN49") (pin "6") (pinfunction "2_6") (pintype "passive"))
    )
    (net (code "259") (name "Net-(IC1-A1)") (class "Default")
      (node (ref "IC1") (pin "16") (pinfunction "A1_16") (pintype "input"))
      (node (ref "J7") (pin "4") (pinfunction "4_4") (pintype "passive"))
      (node (ref "RN49") (pin "7") (pinfunction "2_7") (pintype "passive"))
    )
    (net (code "260") (name "Net-(IC1-A2)") (class "Default")
      (node (ref "IC1") (pin "17") (pinfunction "A2_17") (pintype "input"))
      (node (ref "J7") (pin "6") (pinfunction "6_6") (pintype "passive"))
      (node (ref "RN49") (pin "8") (pinfunction "2_8") (pintype "passive"))
    )
    (net (code "261") (name "Net-(IC2-A0)") (class "Default")
      (node (ref "IC2") (pin "15") (pinfunction "A0_15") (pintype "input"))
      (node (ref "J12") (pin "2") (pinfunction "2_2") (pintype "passive"))
      (node (ref "RN50") (pin "6") (pinfunction "2_6") (pintype "passive"))
    )
    (net (code "262") (name "Net-(IC2-A1)") (class "Default")
      (node (ref "IC2") (pin "16") (pinfunction "A1_16") (pintype "input"))
      (node (ref "J12") (pin "4") (pinfunction "4_4") (pintype "passive"))
      (node (ref "RN50") (pin "7") (pinfunction "2_7") (pintype "passive"))
    )
    (net (code "263") (name "Net-(IC2-A2)") (class "Default")
      (node (ref "IC2") (pin "17") (pinfunction "A2_17") (pintype "input"))
      (node (ref "J12") (pin "6") (pinfunction "6_6") (pintype "passive"))
      (node (ref "RN50") (pin "8") (pinfunction "2_8") (pintype "passive"))
    )
    (net (code "264") (name "Net-(IC3-A0)") (class "Default")
      (node (ref "IC3") (pin "15") (pinfunction "A0_15") (pintype "input"))
      (node (ref "J11") (pin "2") (pinfunction "2_2") (pintype "passive"))
      (node (ref "RN51") (pin "6") (pinfunction "2_6") (pintype "passive"))
    )
    (net (code "265") (name "Net-(IC3-A1)") (class "Default")
      (node (ref "IC3") (pin "16") (pinfunction "A1_16") (pintype "input"))
      (node (ref "J11") (pin "4") (pinfunction "4_4") (pintype "passive"))
      (node (ref "RN51") (pin "7") (pinfunction "2_7") (pintype "passive"))
    )
    (net (code "266") (name "Net-(IC3-A2)") (class "Default")
      (node (ref "IC3") (pin "17") (pinfunction "A2_17") (pintype "input"))
      (node (ref "J11") (pin "6") (pinfunction "6_6") (pintype "passive"))
      (node (ref "RN51") (pin "8") (pinfunction "2_8") (pintype "passive"))
    )
    (net (code "267") (name "Net-(IC4-A0)") (class "Default")
      (node (ref "IC4") (pin "15") (pinfunction "A0_15") (pintype "input"))
      (node (ref "J10") (pin "2") (pinfunction "2_2") (pintype "passive"))
      (node (ref "RN52") (pin "6") (pinfunction "2_6") (pintype "passive"))
    )
    (net (code "268") (name "Net-(IC4-A1)") (class "Default")
      (node (ref "IC4") (pin "16") (pinfunction "A1_16") (pintype "input"))
      (node (ref "J10") (pin "4") (pinfunction "4_4") (pintype "passive"))
      (node (ref "RN52") (pin "7") (pinfunction "2_7") (pintype "passive"))
    )
    (net (code "269") (name "Net-(IC4-A2)") (class "Default")
      (node (ref "IC4") (pin "17") (pinfunction "A2_17") (pintype "input"))
      (node (ref "J10") (pin "6") (pinfunction "6_6") (pintype "passive"))
      (node (ref "RN52") (pin "8") (pinfunction "2_8") (pintype "passive"))
    )
    (net (code "270") (name "Net-(IC5-A0)") (class "Default")
      (node (ref "IC5") (pin "15") (pinfunction "A0_15") (pintype "input"))
      (node (ref "J9") (pin "2") (pinfunction "2_2") (pintype "passive"))
      (node (ref "RN53") (pin "6") (pinfunction "2_6") (pintype "passive"))
    )
    (net (code "271") (name "Net-(IC5-A1)") (class "Default")
      (node (ref "IC5") (pin "16") (pinfunction "A1_16") (pintype "input"))
      (node (ref "J9") (pin "4") (pinfunction "4_4") (pintype "passive"))
      (node (ref "RN53") (pin "7") (pinfunction "2_7") (pintype "passive"))
    )
    (net (code "272") (name "Net-(IC5-A2)") (class "Default")
      (node (ref "IC5") (pin "17") (pinfunction "A2_17") (pintype "input"))
      (node (ref "J9") (pin "6") (pinfunction "6_6") (pintype "passive"))
      (node (ref "RN53") (pin "8") (pinfunction "2_8") (pintype "passive"))
    )
    (net (code "273") (name "Net-(IC6-A0)") (class "Default")
      (node (ref "IC6") (pin "15") (pinfunction "A0_15") (pintype "input"))
      (node (ref "J8") (pin "2") (pinfunction "2_2") (pintype "passive"))
      (node (ref "RN54") (pin "6") (pinfunction "2_6") (pintype "passive"))
    )
    (net (code "274") (name "Net-(IC6-A1)") (class "Default")
      (node (ref "IC6") (pin "16") (pinfunction "A1_16") (pintype "input"))
      (node (ref "J8") (pin "4") (pinfunction "4_4") (pintype "passive"))
      (node (ref "RN54") (pin "7") (pinfunction "2_7") (pintype "passive"))
    )
    (net (code "275") (name "Net-(IC6-A2)") (class "Default")
      (node (ref "IC6") (pin "17") (pinfunction "A2_17") (pintype "input"))
      (node (ref "J8") (pin "6") (pinfunction "6_6") (pintype "passive"))
      (node (ref "RN54") (pin "8") (pinfunction "2_8") (pintype "passive"))
    )
    (net (code "276") (name "Net-(IC7-A0)") (class "Default")
      (node (ref "IC7") (pin "15") (pinfunction "A0_15") (pintype "input"))
      (node (ref "J13") (pin "2") (pinfunction "2_2") (pintype "passive"))
      (node (ref "RN63") (pin "6") (pinfunction "2_6") (pintype "passive"))
    )
    (net (code "277") (name "Net-(IC7-A1)") (class "Default")
      (node (ref "IC7") (pin "16") (pinfunction "A1_16") (pintype "input"))
      (node (ref "J13") (pin "4") (pinfunction "4_4") (pintype "passive"))
      (node (ref "RN63") (pin "7") (pinfunction "2_7") (pintype "passive"))
    )
    (net (code "278") (name "Net-(IC7-A2)") (class "Default")
      (node (ref "IC7") (pin "17") (pinfunction "A2_17") (pintype "input"))
      (node (ref "J13") (pin "6") (pinfunction "6_6") (pintype "passive"))
      (node (ref "RN63") (pin "8") (pinfunction "2_8") (pintype "passive"))
    )
    (net (code "279") (name "Net-(IC8-A0)") (class "Default")
      (node (ref "IC8") (pin "15") (pinfunction "A0_15") (pintype "input"))
      (node (ref "J14") (pin "2") (pinfunction "2_2") (pintype "passive"))
      (node (ref "RN72") (pin "6") (pinfunction "2_6") (pintype "passive"))
    )
    (net (code "280") (name "Net-(IC8-A1)") (class "Default")
      (node (ref "IC8") (pin "16") (pinfunction "A1_16") (pintype "input"))
      (node (ref "J14") (pin "4") (pinfunction "4_4") (pintype "passive"))
      (node (ref "RN72") (pin "7") (pinfunction "2_7") (pintype "passive"))
    )
    (net (code "281") (name "Net-(IC8-A2)") (class "Default")
      (node (ref "IC8") (pin "17") (pinfunction "A2_17") (pintype "input"))
      (node (ref "J14") (pin "6") (pinfunction "6_6") (pintype "passive"))
      (node (ref "RN72") (pin "8") (pinfunction "2_8") (pintype "passive"))
    )
    (net (code "282") (name "Net-(LED1-PadA)") (class "Default")
      (node (ref "LED1") (pin "A") (pinfunction "A_A") (pintype "passive"))
      (node (ref "R98") (pin "1") (pinfunction "1_1") (pintype "passive"))
    )
    (net (code "283") (name "Net-(LED2-PadA)") (class "Default")
      (node (ref "LED2") (pin "A") (pinfunction "A_A") (pintype "passive"))
      (node (ref "R97") (pin "1") (pinfunction "1_1") (pintype "passive"))
    )
    (net (code "284") (name "Net-(R99-Pad2)") (class "Default")
      (node (ref "R99") (pin "2") (pinfunction "2_2") (pintype "passive"))
      (node (ref "SJ2") (pin "1") (pinfunction "1_1") (pintype "passive"))
    )
    (net (code "285") (name "Net-(R100-Pad2)") (class "Default")
      (node (ref "R100") (pin "2") (pinfunction "2_2") (pintype "passive"))
      (node (ref "SJ1") (pin "1") (pinfunction "1_1") (pintype "passive"))
    )
    (net (code "286") (name "Net-(R101-Pad2)") (class "Default")
      (node (ref "R101") (pin "2") (pinfunction "2_2") (pintype "passive"))
      (node (ref "SJ3") (pin "1") (pinfunction "1_1") (pintype "passive"))
    )
    (net (code "287") (name "SCL") (class "Default")
      (node (ref "IC1") (pin "12") (pinfunction "SCL_12") (pintype "input"))
      (node (ref "IC2") (pin "12") (pinfunction "SCL_12") (pintype "input"))
      (node (ref "IC3") (pin "12") (pinfunction "SCL_12") (pintype "input"))
      (node (ref "IC4") (pin "12") (pinfunction "SCL_12") (pintype "input"))
      (node (ref "IC5") (pin "12") (pinfunction "SCL_12") (pintype "input"))
      (node (ref "IC6") (pin "12") (pinfunction "SCL_12") (pintype "input"))
      (node (ref "IC7") (pin "12") (pinfunction "SCL_12") (pintype "input"))
      (node (ref "IC8") (pin "12") (pinfunction "SCL_12") (pintype "input"))
      (node (ref "J1") (pin "1") (pinfunction "1_1") (pintype "passive"))
      (node (ref "J2") (pin "1") (pinfunction "1_1") (pintype "passive"))
      (node (ref "R99") (pin "1") (pinfunction "1_1") (pintype "passive"))
    )
    (net (code "288") (name "SDA") (class "Default")
      (node (ref "IC1") (pin "13") (pinfunction "SDA_13") (pintype "bidirectional"))
      (node (ref "IC2") (pin "13") (pinfunction "SDA_13") (pintype "bidirectional"))
      (node (ref "IC3") (pin "13") (pinfunction "SDA_13") (pintype "bidirectional"))
      (node (ref "IC4") (pin "13") (pinfunction "SDA_13") (pintype "bidirectional"))
      (node (ref "IC5") (pin "13") (pinfunction "SDA_13") (pintype "bidirectional"))
      (node (ref "IC6") (pin "13") (pinfunction "SDA_13") (pintype "bidirectional"))
      (node (ref "IC7") (pin "13") (pinfunction "SDA_13") (pintype "bidirectional"))
      (node (ref "IC8") (pin "13") (pinfunction "SDA_13") (pintype "bidirectional"))
      (node (ref "J1") (pin "2") (pinfunction "2_2") (pintype "passive"))
      (node (ref "J2") (pin "2") (pinfunction "2_2") (pintype "passive"))
      (node (ref "R100") (pin "1") (pinfunction "1_1") (pintype "passive"))
    )
    (net (code "289") (name "VCC") (class "Default")
      (node (ref "C1") (pin "1") (pinfunction "1_1") (pintype "passive"))
      (node (ref "C10") (pin "1") (pinfunction "1_1") (pintype "passive"))
      (node (ref "C11") (pin "1") (pinfunction "1_1") (pintype "passive"))
      (node (ref "C2") (pin "1") (pinfunction "1_1") (pintype "passive"))
      (node (ref "C3") (pin "1") (pinfunction "1_1") (pintype "passive"))
      (node (ref "C4") (pin "1") (pinfunction "1_1") (pintype "passive"))
      (node (ref "C5") (pin "1") (pinfunction "1_1") (pintype "passive"))
      (node (ref "C6") (pin "1") (pinfunction "1_1") (pintype "passive"))
      (node (ref "IC1") (pin "9") (pinfunction "VDD_9") (pintype "power_in"))
      (node (ref "IC2") (pin "9") (pinfunction "VDD_9") (pintype "power_in"))
      (node (ref "IC3") (pin "9") (pinfunction "VDD_9") (pintype "power_in"))
      (node (ref "IC4") (pin "9") (pinfunction "VDD_9") (pintype "power_in"))
      (node (ref "IC5") (pin "9") (pinfunction "VDD_9") (pintype "power_in"))
      (node (ref "IC6") (pin "9") (pinfunction "VDD_9") (pintype "power_in"))
      (node (ref "IC7") (pin "9") (pinfunction "VDD_9") (pintype "power_in"))
      (node (ref "IC8") (pin "9") (pinfunction "VDD_9") (pintype "power_in"))
      (node (ref "J1") (pin "5") (pinfunction "5_5") (pintype "passive"))
      (node (ref "J10") (pin "1") (pinfunction "1_1") (pintype "passive"))
      (node (ref "J10") (pin "3") (pinfunction "3_3") (pintype "passive"))
      (node (ref "J10") (pin "5") (pinfunction "5_5") (pintype "passive"))
      (node (ref "J11") (pin "1") (pinfunction "1_1") (pintype "passive"))
      (node (ref "J11") (pin "3") (pinfunction "3_3") (pintype "passive"))
      (node (ref "J11") (pin "5") (pinfunction "5_5") (pintype "passive"))
      (node (ref "J12") (pin "1") (pinfunction "1_1") (pintype "passive"))
      (node (ref "J12") (pin "3") (pinfunction "3_3") (pintype "passive"))
      (node (ref "J12") (pin "5") (pinfunction "5_5") (pintype "passive"))
      (node (ref "J13") (pin "1") (pinfunction "1_1") (pintype "passive"))
      (node (ref "J13") (pin "3") (pinfunction "3_3") (pintype "passive"))
      (node (ref "J13") (pin "5") (pinfunction "5_5") (pintype "passive"))
      (node (ref "J14") (pin "1") (pinfunction "1_1") (pintype "passive"))
      (node (ref "J14") (pin "3") (pinfunction "3_3") (pintype "passive"))
      (node (ref "J14") (pin "5") (pinfunction "5_5") (pintype "passive"))
      (node (ref "J2") (pin "5") (pinfunction "5_5") (pintype "passive"))
      (node (ref "J7") (pin "1") (pinfunction "1_1") (pintype "passive"))
      (node (ref "J7") (pin "3") (pinfunction "3_3") (pintype "passive"))
      (node (ref "J7") (pin "5") (pinfunction "5_5") (pintype "passive"))
      (node (ref "J8") (pin "1") (pinfunction "1_1") (pintype "passive"))
      (node (ref "J8") (pin "3") (pinfunction "3_3") (pintype "passive"))
      (node (ref "J8") (pin "5") (pinfunction "5_5") (pintype "passive"))
      (node (ref "J9") (pin "1") (pinfunction "1_1") (pintype "passive"))
      (node (ref "J9") (pin "3") (pinfunction "3_3") (pintype "passive"))
      (node (ref "J9") (pin "5") (pinfunction "5_5") (pintype "passive"))
      (node (ref "R97") (pin "2") (pinfunction "2_2") (pintype "passive"))
      (node (ref "RN13") (pin "5") (pinfunction "2_5") (pintype "passive"))
      (node (ref "RN13") (pin "6") (pinfunction "2_6") (pintype "passive"))
      (node (ref "RN13") (pin "7") (pinfunction "2_7") (pintype "passive"))
      (node (ref "RN13") (pin "8") (pinfunction "2_8") (pintype "passive"))
      (node (ref "RN14") (pin "5") (pinfunction "2_5") (pintype "passive"))
      (node (ref "RN14") (pin "6") (pinfunction "2_6") (pintype "passive"))
      (node (ref "RN14") (pin "7") (pinfunction "2_7") (pintype "passive"))
      (node (ref "RN14") (pin "8") (pinfunction "2_8") (pintype "passive"))
      (node (ref "RN15") (pin "5") (pinfunction "2_5") (pintype "passive"))
      (node (ref "RN15") (pin "6") (pinfunction "2_6") (pintype "passive"))
      (node (ref "RN15") (pin "7") (pinfunction "2_7") (pintype "passive"))
      (node (ref "RN15") (pin "8") (pinfunction "2_8") (pintype "passive"))
      (node (ref "RN16") (pin "5") (pinfunction "2_5") (pintype "passive"))
      (node (ref "RN16") (pin "6") (pinfunction "2_6") (pintype "passive"))
      (node (ref "RN16") (pin "7") (pinfunction "2_7") (pintype "passive"))
      (node (ref "RN16") (pin "8") (pinfunction "2_8") (pintype "passive"))
      (node (ref "RN21") (pin "5") (pinfunction "2_5") (pintype "passive"))
      (node (ref "RN21") (pin "6") (pinfunction "2_6") (pintype "passive"))
      (node (ref "RN21") (pin "7") (pinfunction "2_7") (pintype "passive"))
      (node (ref "RN21") (pin "8") (pinfunction "2_8") (pintype "passive"))
      (node (ref "RN22") (pin "5") (pinfunction "2_5") (pintype "passive"))
      (node (ref "RN22") (pin "6") (pinfunction "2_6") (pintype "passive"))
      (node (ref "RN22") (pin "7") (pinfunction "2_7") (pintype "passive"))
      (node (ref "RN22") (pin "8") (pinfunction "2_8") (pintype "passive"))
      (node (ref "RN23") (pin "5") (pinfunction "2_5") (pintype "passive"))
      (node (ref "RN23") (pin "6") (pinfunction "2_6") (pintype "passive"))
      (node (ref "RN23") (pin "7") (pinfunction "2_7") (pintype "passive"))
      (node (ref "RN23") (pin "8") (pinfunction "2_8") (pintype "passive"))
      (node (ref "RN24") (pin "5") (pinfunction "2_5") (pintype "passive"))
      (node (ref "RN24") (pin "6") (pinfunction "2_6") (pintype "passive"))
      (node (ref "RN24") (pin "7") (pinfunction "2_7") (pintype "passive"))
      (node (ref "RN24") (pin "8") (pinfunction "2_8") (pintype "passive"))
      (node (ref "RN29") (pin "5") (pinfunction "2_5") (pintype "passive"))
      (node (ref "RN29") (pin "6") (pinfunction "2_6") (pintype "passive"))
      (node (ref "RN29") (pin "7") (pinfunction "2_7") (pintype "passive"))
      (node (ref "RN29") (pin "8") (pinfunction "2_8") (pintype "passive"))
      (node (ref "RN30") (pin "5") (pinfunction "2_5") (pintype "passive"))
      (node (ref "RN30") (pin "6") (pinfunction "2_6") (pintype "passive"))
      (node (ref "RN30") (pin "7") (pinfunction "2_7") (pintype "passive"))
      (node (ref "RN30") (pin "8") (pinfunction "2_8") (pintype "passive"))
      (node (ref "RN31") (pin "5") (pinfunction "2_5") (pintype "passive"))
      (node (ref "RN31") (pin "6") (pinfunction "2_6") (pintype "passive"))
      (node (ref "RN31") (pin "7") (pinfunction "2_7") (pintype "passive"))
      (node (ref "RN31") (pin "8") (pinfunction "2_8") (pintype "passive"))
      (node (ref "RN32") (pin "5") (pinfunction "2_5") (pintype "passive"))
      (node (ref "RN32") (pin "6") (pinfunction "2_6") (pintype "passive"))
      (node (ref "RN32") (pin "7") (pinfunction "2_7") (pintype "passive"))
      (node (ref "RN32") (pin "8") (pinfunction "2_8") (pintype "passive"))
      (node (ref "RN41") (pin "5") (pinfunction "2_5") (pintype "passive"))
      (node (ref "RN41") (pin "6") (pinfunction "2_6") (pintype "passive"))
      (node (ref "RN41") (pin "7") (pinfunction "2_7") (pintype "passive"))
      (node (ref "RN41") (pin "8") (pinfunction "2_8") (pintype "passive"))
      (node (ref "RN42") (pin "5") (pinfunction "2_5") (pintype "passive"))
      (node (ref "RN42") (pin "6") (pinfunction "2_6") (pintype "passive"))
      (node (ref "RN42") (pin "7") (pinfunction "2_7") (pintype "passive"))
      (node (ref "RN42") (pin "8") (pinfunction "2_8") (pintype "passive"))
      (node (ref "RN43") (pin "5") (pinfunction "2_5") (pintype "passive"))
      (node (ref "RN43") (pin "6") (pinfunction "2_6") (pintype "passive"))
      (node (ref "RN43") (pin "7") (pinfunction "2_7") (pintype "passive"))
      (node (ref "RN43") (pin "8") (pinfunction "2_8") (pintype "passive"))
      (node (ref "RN44") (pin "5") (pinfunction "2_5") (pintype "passive"))
      (node (ref "RN44") (pin "6") (pinfunction "2_6") (pintype "passive"))
      (node (ref "RN44") (pin "7") (pinfunction "2_7") (pintype "passive"))
      (node (ref "RN44") (pin "8") (pinfunction "2_8") (pintype "passive"))
      (node (ref "RN45") (pin "5") (pinfunction "2_5") (pintype "passive"))
      (node (ref "RN45") (pin "6") (pinfunction "2_6") (pintype "passive"))
      (node (ref "RN45") (pin "7") (pinfunction "2_7") (pintype "passive"))
      (node (ref "RN45") (pin "8") (pinfunction "2_8") (pintype "passive"))
      (node (ref "RN46") (pin "5") (pinfunction "2_5") (pintype "passive"))
      (node (ref "RN46") (pin "6") (pinfunction "2_6") (pintype "passive"))
      (node (ref "RN46") (pin "7") (pinfunction "2_7") (pintype "passive"))
      (node (ref "RN46") (pin "8") (pinfunction "2_8") (pintype "passive"))
      (node (ref "RN47") (pin "5") (pinfunction "2_5") (pintype "passive"))
      (node (ref "RN47") (pin "6") (pinfunction "2_6") (pintype "passive"))
      (node (ref "RN47") (pin "7") (pinfunction "2_7") (pintype "passive"))
      (node (ref "RN47") (pin "8") (pinfunction "2_8") (pintype "passive"))
      (node (ref "RN48") (pin "5") (pinfunction "2_5") (pintype "passive"))
      (node (ref "RN48") (pin "6") (pinfunction "2_6") (pintype "passive"))
      (node (ref "RN48") (pin "7") (pinfunction "2_7") (pintype "passive"))
      (node (ref "RN48") (pin "8") (pinfunction "2_8") (pintype "passive"))
      (node (ref "RN5") (pin "5") (pinfunction "2_5") (pintype "passive"))
      (node (ref "RN5") (pin "6") (pinfunction "2_6") (pintype "passive"))
      (node (ref "RN5") (pin "7") (pinfunction "2_7") (pintype "passive"))
      (node (ref "RN5") (pin "8") (pinfunction "2_8") (pintype "passive"))
      (node (ref "RN59") (pin "5") (pinfunction "2_5") (pintype "passive"))
      (node (ref "RN59") (pin "6") (pinfunction "2_6") (pintype "passive"))
      (node (ref "RN59") (pin "7") (pinfunction "2_7") (pintype "passive"))
      (node (ref "RN59") (pin "8") (pinfunction "2_8") (pintype "passive"))
      (node (ref "RN6") (pin "5") (pinfunction "2_5") (pintype "passive"))
      (node (ref "RN6") (pin "6") (pinfunction "2_6") (pintype "passive"))
      (node (ref "RN6") (pin "7") (pinfunction "2_7") (pintype "passive"))
      (node (ref "RN6") (pin "8") (pinfunction "2_8") (pintype "passive"))
      (node (ref "RN60") (pin "5") (pinfunction "2_5") (pintype "passive"))
      (node (ref "RN60") (pin "6") (pinfunction "2_6") (pintype "passive"))
      (node (ref "RN60") (pin "7") (pinfunction "2_7") (pintype "passive"))
      (node (ref "RN60") (pin "8") (pinfunction "2_8") (pintype "passive"))
      (node (ref "RN61") (pin "5") (pinfunction "2_5") (pintype "passive"))
      (node (ref "RN61") (pin "6") (pinfunction "2_6") (pintype "passive"))
      (node (ref "RN61") (pin "7") (pinfunction "2_7") (pintype "passive"))
      (node (ref "RN61") (pin "8") (pinfunction "2_8") (pintype "passive"))
      (node (ref "RN62") (pin "5") (pinfunction "2_5") (pintype "passive"))
      (node (ref "RN62") (pin "6") (pinfunction "2_6") (pintype "passive"))
      (node (ref "RN62") (pin "7") (pinfunction "2_7") (pintype "passive"))
      (node (ref "RN62") (pin "8") (pinfunction "2_8") (pintype "passive"))
      (node (ref "RN68") (pin "5") (pinfunction "2_5") (pintype "passive"))
      (node (ref "RN68") (pin "6") (pinfunction "2_6") (pintype "passive"))
      (node (ref "RN68") (pin "7") (pinfunction "2_7") (pintype "passive"))
      (node (ref "RN68") (pin "8") (pinfunction "2_8") (pintype "passive"))
      (node (ref "RN69") (pin "5") (pinfunction "2_5") (pintype "passive"))
      (node (ref "RN69") (pin "6") (pinfunction "2_6") (pintype "passive"))
      (node (ref "RN69") (pin "7") (pinfunction "2_7") (pintype "passive"))
      (node (ref "RN69") (pin "8") (pinfunction "2_8") (pintype "passive"))
      (node (ref "RN7") (pin "5") (pinfunction "2_5") (pintype "passive"))
      (node (ref "RN7") (pin "6") (pinfunction "2_6") (pintype "passive"))
      (node (ref "RN7") (pin "7") (pinfunction "2_7") (pintype "passive"))
      (node (ref "RN7") (pin "8") (pinfunction "2_8") (pintype "passive"))
      (node (ref "RN70") (pin "5") (pinfunction "2_5") (pintype "passive"))
      (node (ref "RN70") (pin "6") (pinfunction "2_6") (pintype "passive"))
      (node (ref "RN70") (pin "7") (pinfunction "2_7") (pintype "passive"))
      (node (ref "RN70") (pin "8") (pinfunction "2_8") (pintype "passive"))
      (node (ref "RN71") (pin "5") (pinfunction "2_5") (pintype "passive"))
      (node (ref "RN71") (pin "6") (pinfunction "2_6") (pintype "passive"))
      (node (ref "RN71") (pin "7") (pinfunction "2_7") (pintype "passive"))
      (node (ref "RN71") (pin "8") (pinfunction "2_8") (pintype "passive"))
      (node (ref "RN8") (pin "5") (pinfunction "2_5") (pintype "passive"))
      (node (ref "RN8") (pin "6") (pinfunction "2_6") (pintype "passive"))
      (node (ref "RN8") (pin "7") (pinfunction "2_7") (pintype "passive"))
      (node (ref "RN8") (pin "8") (pinfunction "2_8") (pintype "passive"))
      (node (ref "SJ1") (pin "2") (pinfunction "2_2") (pintype "passive"))
      (node (ref "SJ2") (pin "2") (pinfunction "2_2") (pintype "passive"))
      (node (ref "SJ3") (pin "2") (pinfunction "2_2") (pintype "passive"))
    )
    (net (code "290") (name "VIN") (class "Default")
      (node (ref "C12") (pin "+") (pinfunction "+_+") (pintype "passive"))
      (node (ref "C7") (pin "+") (pinfunction "+_+") (pintype "passive"))
      (node (ref "C8") (pin "+") (pinfunction "+_+") (pintype "passive"))
      (node (ref "C9") (pin "+") (pinfunction "+_+") (pintype "passive"))
      (node (ref "J1") (pin "3") (pinfunction "3_3") (pintype "passive"))
      (node (ref "J15") (pin "A4") (pinfunction "A4_A4") (pintype "bidirectional"))
      (node (ref "J15") (pin "A5") (pinfunction "A5_A5") (pintype "bidirectional"))
      (node (ref "J15") (pin "B4") (pinfunction "B4_B4") (pintype "bidirectional"))
      (node (ref "J15") (pin "B5") (pinfunction "B5_B5") (pintype "bidirectional"))
      (node (ref "J15") (pin "C4") (pinfunction "C4_C4") (pintype "bidirectional"))
      (node (ref "J15") (pin "C5") (pinfunction "C5_C5") (pintype "bidirectional"))
      (node (ref "J15") (pin "D4") (pinfunction "D4_D4") (pintype "bidirectional"))
      (node (ref "J15") (pin "D5") (pinfunction "D5_D5") (pintype "bidirectional"))
      (node (ref "J15") (pin "E4") (pinfunction "E4_E4") (pintype "bidirectional"))
      (node (ref "J15") (pin "E5") (pinfunction "E5_E5") (pintype "bidirectional"))
      (node (ref "J15") (pin "F4") (pinfunction "F4_F4") (pintype "bidirectional"))
      (node (ref "J15") (pin "F5") (pinfunction "F5_F5") (pintype "bidirectional"))
      (node (ref "J15") (pin "G4") (pinfunction "G4_G4") (pintype "bidirectional"))
      (node (ref "J15") (pin "G5") (pinfunction "G5_G5") (pintype "bidirectional"))
      (node (ref "J15") (pin "H4") (pinfunction "H4_H4") (pintype "bidirectional"))
      (node (ref "J15") (pin "H5") (pinfunction "H5_H5") (pintype "bidirectional"))
      (node (ref "J2") (pin "3") (pinfunction "3_3") (pintype "passive"))
      (node (ref "J4") (pin "A4") (pinfunction "A4_A4") (pintype "bidirectional"))
      (node (ref "J4") (pin "A5") (pinfunction "A5_A5") (pintype "bidirectional"))
      (node (ref "J4") (pin "B4") (pinfunction "B4_B4") (pintype "bidirectional"))
      (node (ref "J4") (pin "B5") (pinfunction "B5_B5") (pintype "bidirectional"))
      (node (ref "J4") (pin "C4") (pinfunction "C4_C4") (pintype "bidirectional"))
      (node (ref "J4") (pin "C5") (pinfunction "C5_C5") (pintype "bidirectional"))
      (node (ref "J4") (pin "D4") (pinfunction "D4_D4") (pintype "bidirectional"))
      (node (ref "J4") (pin "D5") (pinfunction "D5_D5") (pintype "bidirectional"))
      (node (ref "J4") (pin "E4") (pinfunction "E4_E4") (pintype "bidirectional"))
      (node (ref "J4") (pin "E5") (pinfunction "E5_E5") (pintype "bidirectional"))
      (node (ref "J4") (pin "F4") (pinfunction "F4_F4") (pintype "bidirectional"))
      (node (ref "J4") (pin "F5") (pinfunction "F5_F5") (pintype "bidirectional"))
      (node (ref "J4") (pin "G4") (pinfunction "G4_G4") (pintype "bidirectional"))
      (node (ref "J4") (pin "G5") (pinfunction "G5_G5") (pintype "bidirectional"))
      (node (ref "J4") (pin "H4") (pinfunction "H4_H4") (pintype "bidirectional"))
      (node (ref "J4") (pin "H5") (pinfunction "H5_H5") (pintype "bidirectional"))
      (node (ref "J5") (pin "A4") (pinfunction "A4_A4") (pintype "bidirectional"))
      (node (ref "J5") (pin "A5") (pinfunction "A5_A5") (pintype "bidirectional"))
      (node (ref "J5") (pin "B4") (pinfunction "B4_B4") (pintype "bidirectional"))
      (node (ref "J5") (pin "B5") (pinfunction "B5_B5") (pintype "bidirectional"))
      (node (ref "J5") (pin "C4") (pinfunction "C4_C4") (pintype "bidirectional"))
      (node (ref "J5") (pin "C5") (pinfunction "C5_C5") (pintype "bidirectional"))
      (node (ref "J5") (pin "D4") (pinfunction "D4_D4") (pintype "bidirectional"))
      (node (ref "J5") (pin "D5") (pinfunction "D5_D5") (pintype "bidirectional"))
      (node (ref "J5") (pin "E4") (pinfunction "E4_E4") (pintype "bidirectional"))
      (node (ref "J5") (pin "E5") (pinfunction "E5_E5") (pintype "bidirectional"))
      (node (ref "J5") (pin "F4") (pinfunction "F4_F4") (pintype "bidirectional"))
      (node (ref "J5") (pin "F5") (pinfunction "F5_F5") (pintype "bidirectional"))
      (node (ref "J5") (pin "G4") (pinfunction "G4_G4") (pintype "bidirectional"))
      (node (ref "J5") (pin "G5") (pinfunction "G5_G5") (pintype "bidirectional"))
      (node (ref "J5") (pin "H4") (pinfunction "H4_H4") (pintype "bidirectional"))
      (node (ref "J5") (pin "H5") (pinfunction "H5_H5") (pintype "bidirectional"))
      (node (ref "J6") (pin "A4") (pinfunction "A4_A4") (pintype "bidirectional"))
      (node (ref "J6") (pin "A5") (pinfunction "A5_A5") (pintype "bidirectional"))
      (node (ref "J6") (pin "B4") (pinfunction "B4_B4") (pintype "bidirectional"))
      (node (ref "J6") (pin "B5") (pinfunction "B5_B5") (pintype "bidirectional"))
      (node (ref "J6") (pin "C4") (pinfunction "C4_C4") (pintype "bidirectional"))
      (node (ref "J6") (pin "C5") (pinfunction "C5_C5") (pintype "bidirectional"))
      (node (ref "J6") (pin "D4") (pinfunction "D4_D4") (pintype "bidirectional"))
      (node (ref "J6") (pin "D5") (pinfunction "D5_D5") (pintype "bidirectional"))
      (node (ref "J6") (pin "E4") (pinfunction "E4_E4") (pintype "bidirectional"))
      (node (ref "J6") (pin "E5") (pinfunction "E5_E5") (pintype "bidirectional"))
      (node (ref "J6") (pin "F4") (pinfunction "F4_F4") (pintype "bidirectional"))
      (node (ref "J6") (pin "F5") (pinfunction "F5_F5") (pintype "bidirectional"))
      (node (ref "J6") (pin "G4") (pinfunction "G4_G4") (pintype "bidirectional"))
      (node (ref "J6") (pin "G5") (pinfunction "G5_G5") (pintype "bidirectional"))
      (node (ref "J6") (pin "H4") (pinfunction "H4_H4") (pintype "bidirectional"))
      (node (ref "J6") (pin "H5") (pinfunction "H5_H5") (pintype "bidirectional"))
      (node (ref "R98") (pin "2") (pinfunction "2_2") (pintype "passive"))
    )
    (net (code "291") (name "unconnected-(IC1-INTB-Pad19)") (class "Default")
      (node (ref "IC1") (pin "19") (pinfunction "INTB_19") (pintype "output"))
    )
    (net (code "292") (name "unconnected-(IC2-INTB-Pad19)") (class "Default")
      (node (ref "IC2") (pin "19") (pinfunction "INTB_19") (pintype "output"))
    )
    (net (code "293") (name "unconnected-(IC3-INTB-Pad19)") (class "Default")
      (node (ref "IC3") (pin "19") (pinfunction "INTB_19") (pintype "output"))
    )
    (net (code "294") (name "unconnected-(IC4-INTB-Pad19)") (class "Default")
      (node (ref "IC4") (pin "19") (pinfunction "INTB_19") (pintype "output"))
    )
    (net (code "295") (name "unconnected-(IC5-INTB-Pad19)") (class "Default")
      (node (ref "IC5") (pin "19") (pinfunction "INTB_19") (pintype "output"))
    )
    (net (code "296") (name "unconnected-(IC6-INTB-Pad19)") (class "Default")
      (node (ref "IC6") (pin "19") (pinfunction "INTB_19") (pintype "output"))
    )
    (net (code "297") (name "unconnected-(IC7-INTB-Pad19)") (class "Default")
      (node (ref "IC7") (pin "19") (pinfunction "INTB_19") (pintype "output"))
    )
    (net (code "298") (name "unconnected-(IC8-INTB-Pad19)") (class "Default")
      (node (ref "IC8") (pin "19") (pinfunction "INTB_19") (pintype "output"))
    )
    (net (code "299") (name "unconnected-(RN49D-2-Pad5)") (class "Default")
      (node (ref "RN49") (pin "5") (pinfunction "2_5") (pintype "passive"))
    )
    (net (code "300") (name "unconnected-(RN50D-2-Pad5)") (class "Default")
      (node (ref "RN50") (pin "5") (pinfunction "2_5") (pintype "passive"))
    )
    (net (code "301") (name "unconnected-(RN51D-2-Pad5)") (class "Default")
      (node (ref "RN51") (pin "5") (pinfunction "2_5") (pintype "passive"))
    )
    (net (code "302") (name "unconnected-(RN52D-2-Pad5)") (class "Default")
      (node (ref "RN52") (pin "5") (pinfunction "2_5") (pintype "passive"))
    )
    (net (code "303") (name "unconnected-(RN53D-2-Pad5)") (class "Default")
      (node (ref "RN53") (pin "5") (pinfunction "2_5") (pintype "passive"))
    )
    (net (code "304") (name "unconnected-(RN54D-2-Pad5)") (class "Default")
      (node (ref "RN54") (pin "5") (pinfunction "2_5") (pintype "passive"))
    )
    (net (code "305") (name "unconnected-(RN63D-2-Pad5)") (class "Default")
      (node (ref "RN63") (pin "5") (pinfunction "2_5") (pintype "passive"))
    )
    (net (code "306") (name "unconnected-(RN72D-2-Pad5)") (class "Default")
      (node (ref "RN72") (pin "5") (pinfunction "2_5") (pintype "passive"))
    )
    (net (code "307") (name "~{INT}") (class "Default")
      (node (ref "IC1") (pin "20") (pinfunction "INTA_20") (pintype "output"))
      (node (ref "IC2") (pin "20") (pinfunction "INTA_20") (pintype "output"))
      (node (ref "IC3") (pin "20") (pinfunction "INTA_20") (pintype "output"))
      (node (ref "IC4") (pin "20") (pinfunction "INTA_20") (pintype "output"))
      (node (ref "IC5") (pin "20") (pinfunction "INTA_20") (pintype "output"))
      (node (ref "IC6") (pin "20") (pinfunction "INTA_20") (pintype "output"))
      (node (ref "IC7") (pin "20") (pinfunction "INTA_20") (pintype "output"))
      (node (ref "IC8") (pin "20") (pinfunction "INTA_20") (pintype "output"))
      (node (ref "J3") (pin "1") (pinfunction "1_1") (pintype "passive"))
    )
    (net (code "308") (name "~{RESET}") (class "Default")
      (node (ref "IC1") (pin "18") (pinfunction "~{RESET}_18") (pintype "input"))
      (node (ref "IC2") (pin "18") (pinfunction "~{RESET}_18") (pintype "input"))
      (node (ref "IC3") (pin "18") (pinfunction "~{RESET}_18") (pintype "input"))
      (node (ref "IC4") (pin "18") (pinfunction "~{RESET}_18") (pintype "input"))
      (node (ref "IC5") (pin "18") (pinfunction "~{RESET}_18") (pintype "input"))
      (node (ref "IC6") (pin "18") (pinfunction "~{RESET}_18") (pintype "input"))
      (node (ref "IC7") (pin "18") (pinfunction "~{RESET}_18") (pintype "input"))
      (node (ref "IC8") (pin "18") (pinfunction "~{RESET}_18") (pintype "input"))
      (node (ref "J1") (pin "6") (pinfunction "6_6") (pintype "passive"))
      (node (ref "J2") (pin "6") (pinfunction "6_6") (pintype "passive"))
      (node (ref "R101") (pin "1") (pinfunction "1_1") (pintype "passive"))
    )
  )
)
